# DataloggerE7.net
KiCad netlist of a schematic drawn in EAGLE
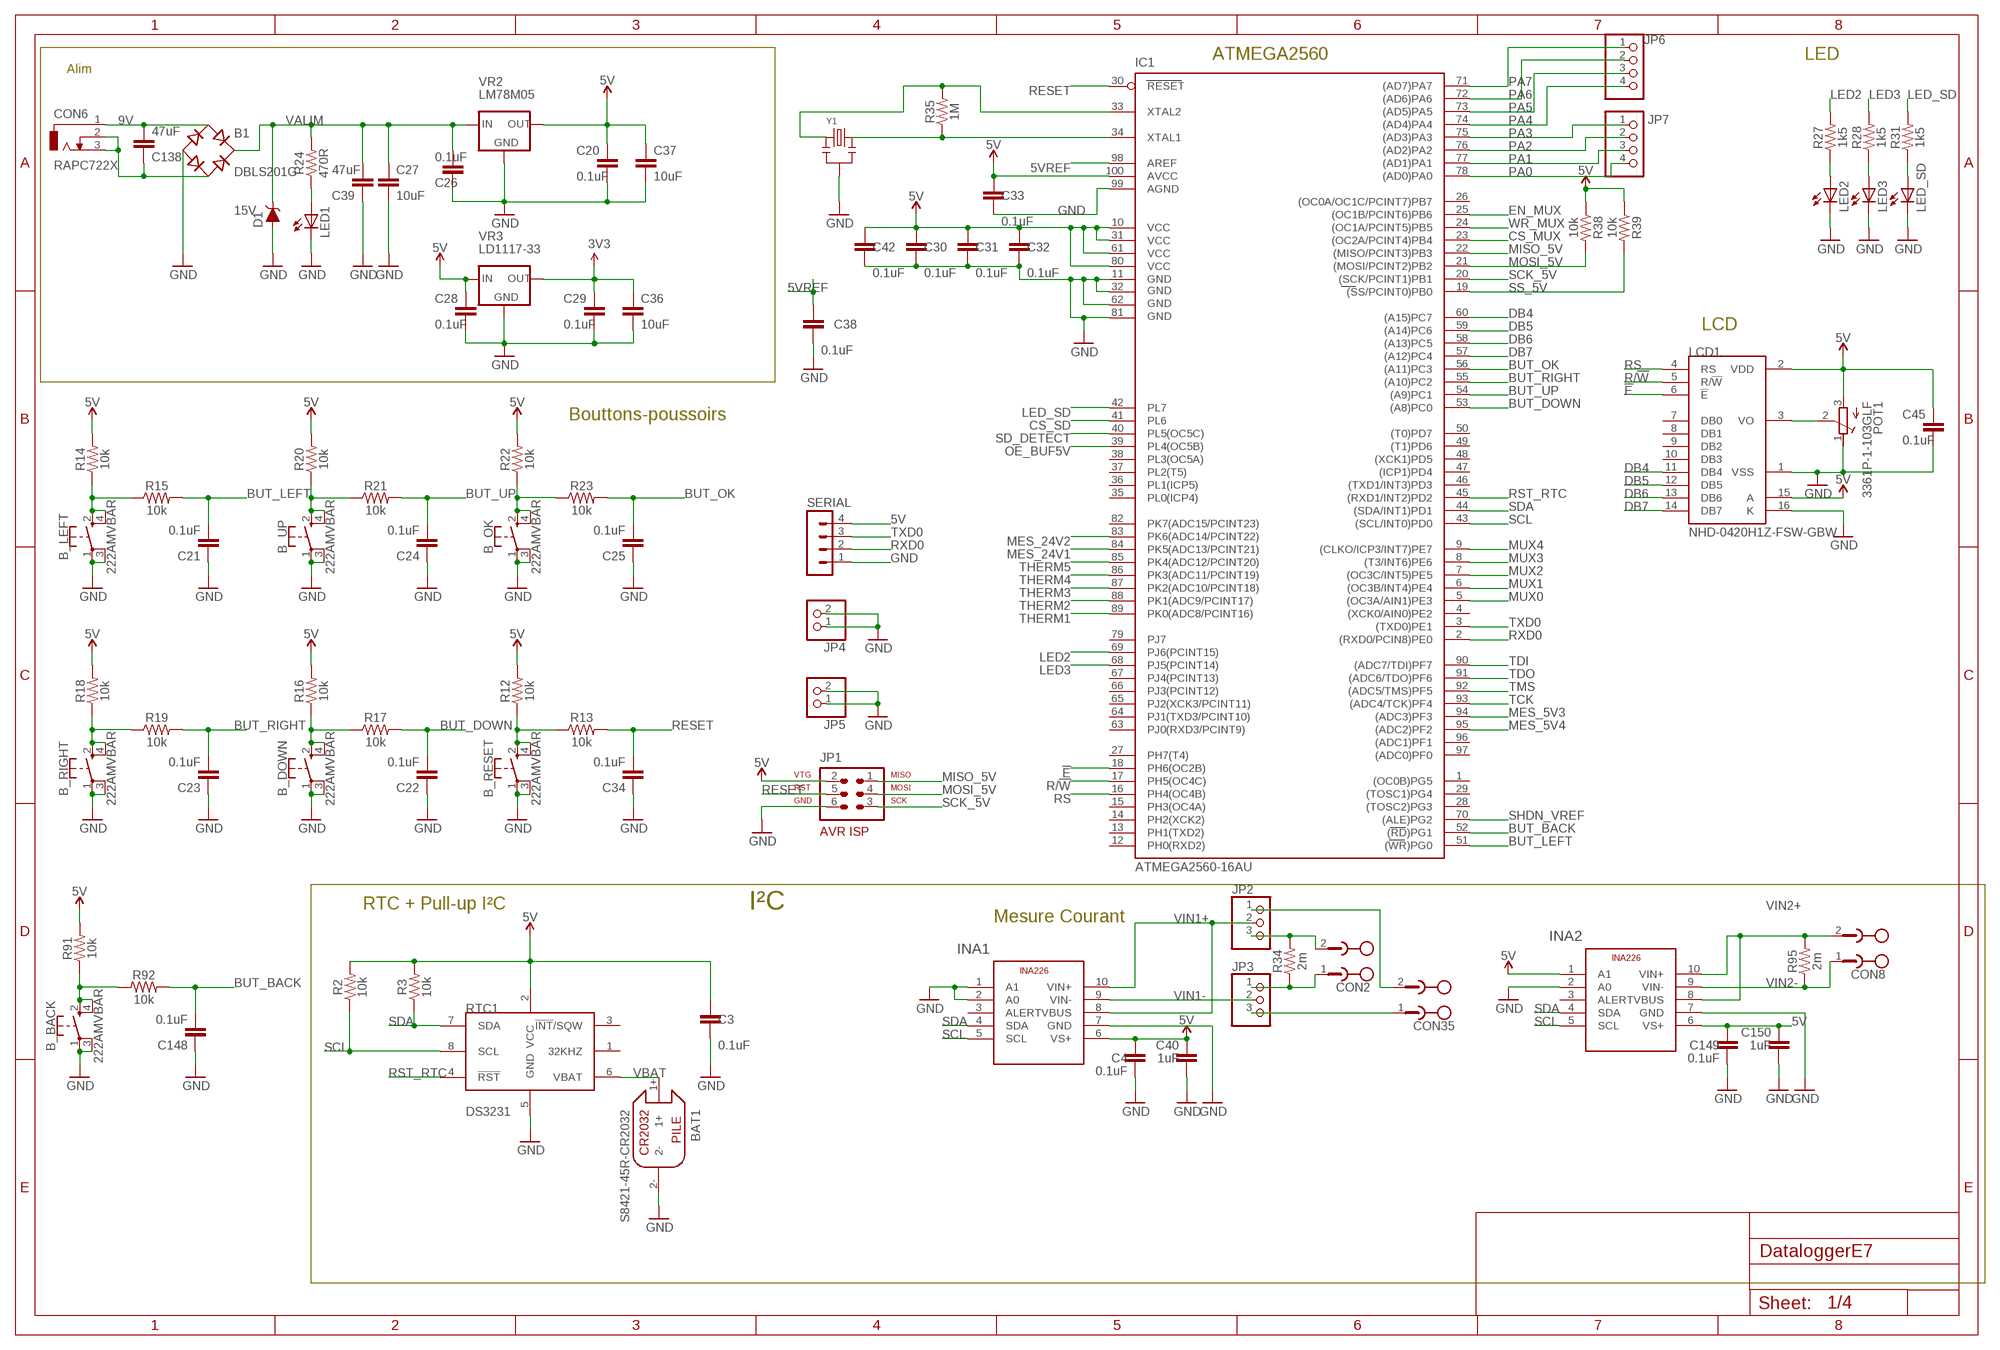
[diagram p0: schematic, sheet 1]
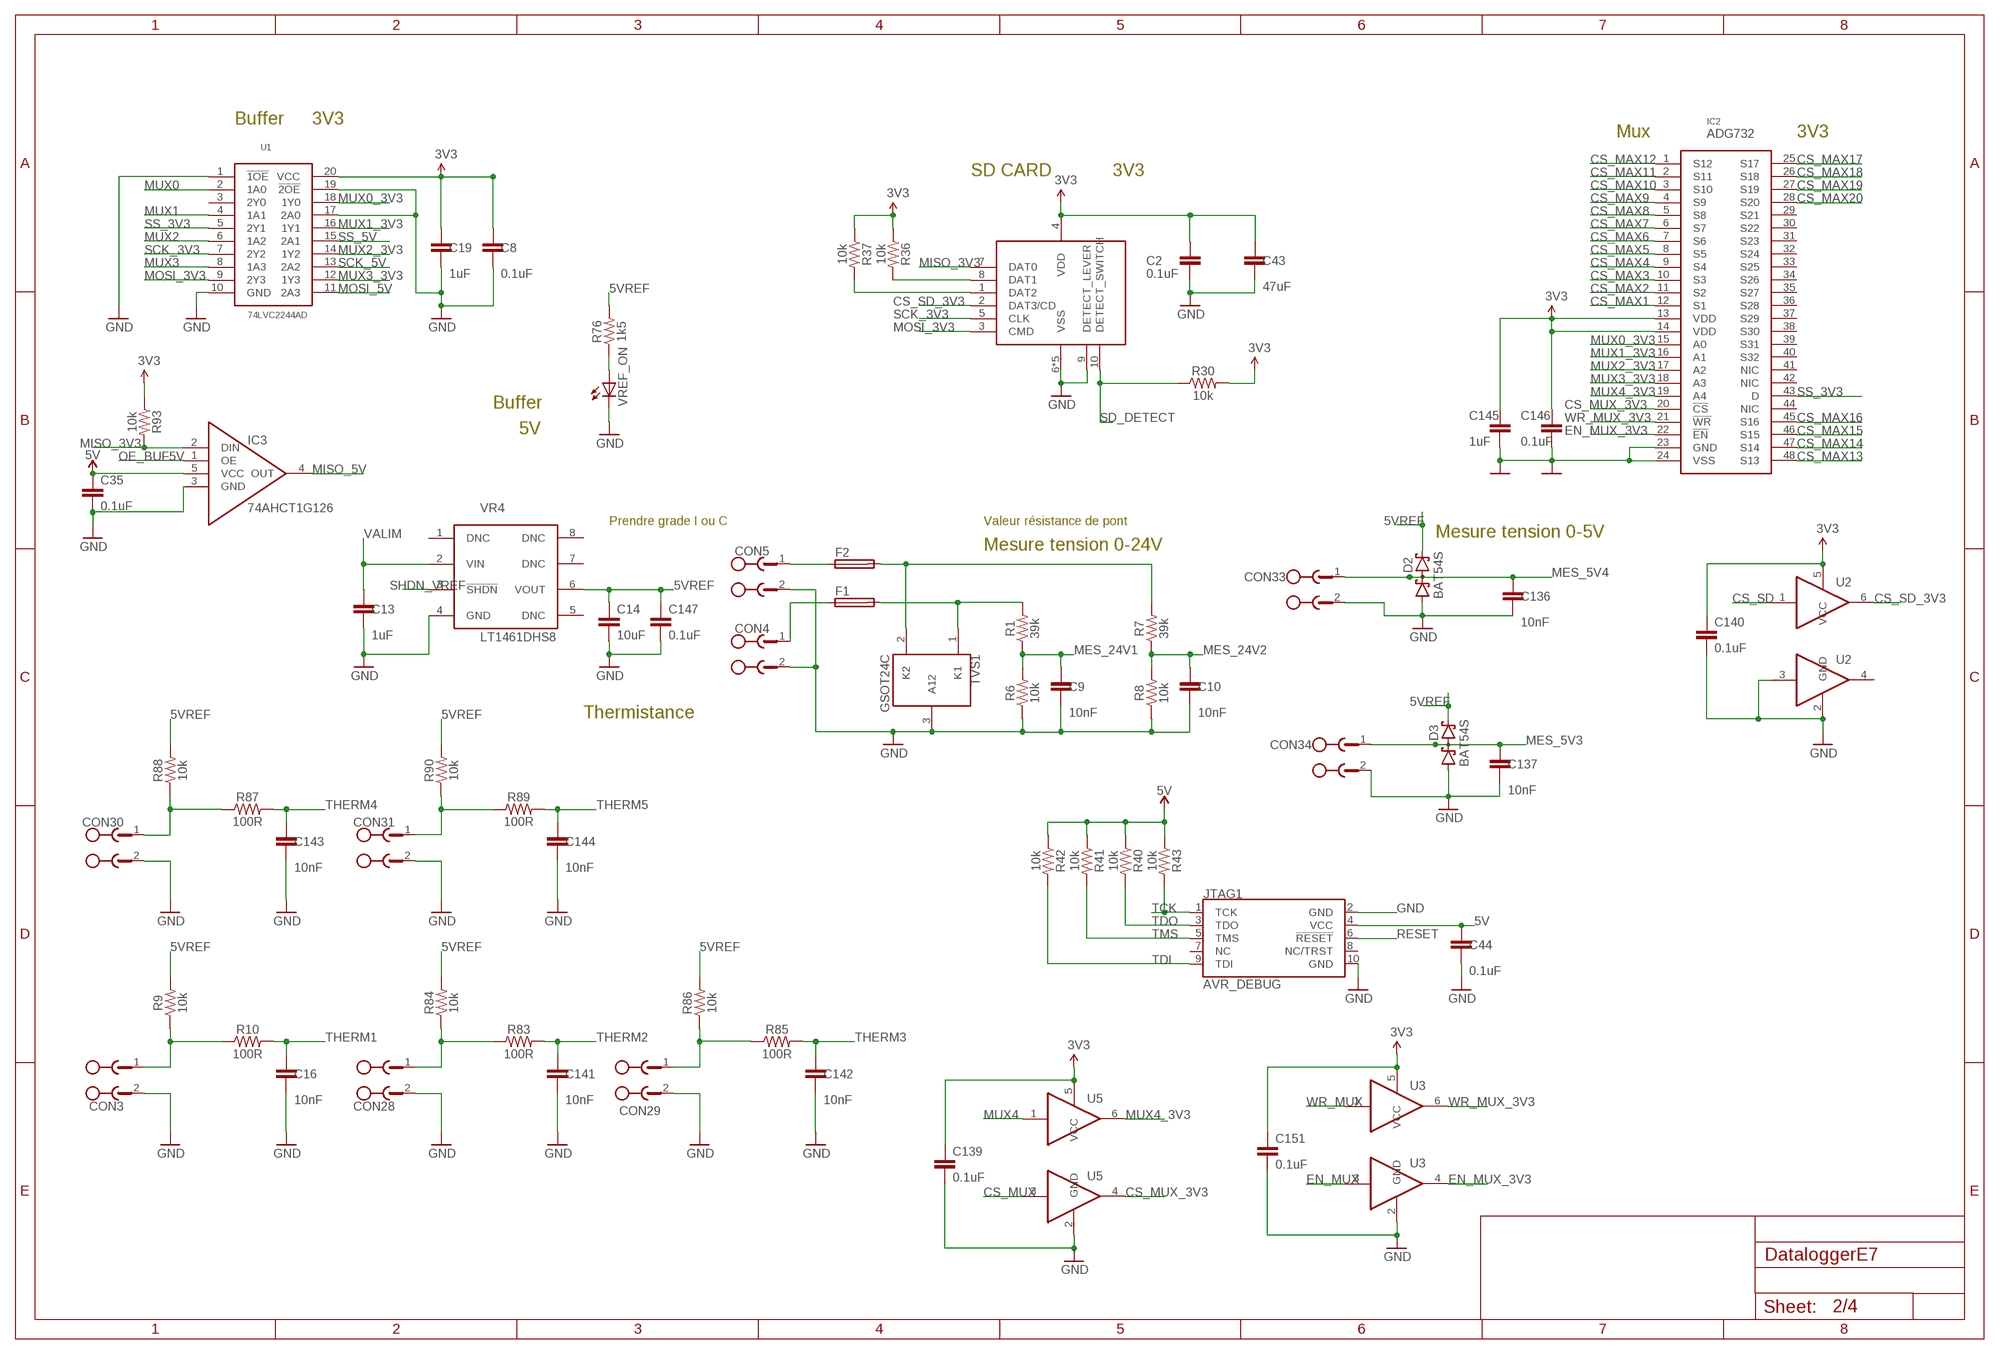
[diagram p1: schematic, sheet 2]
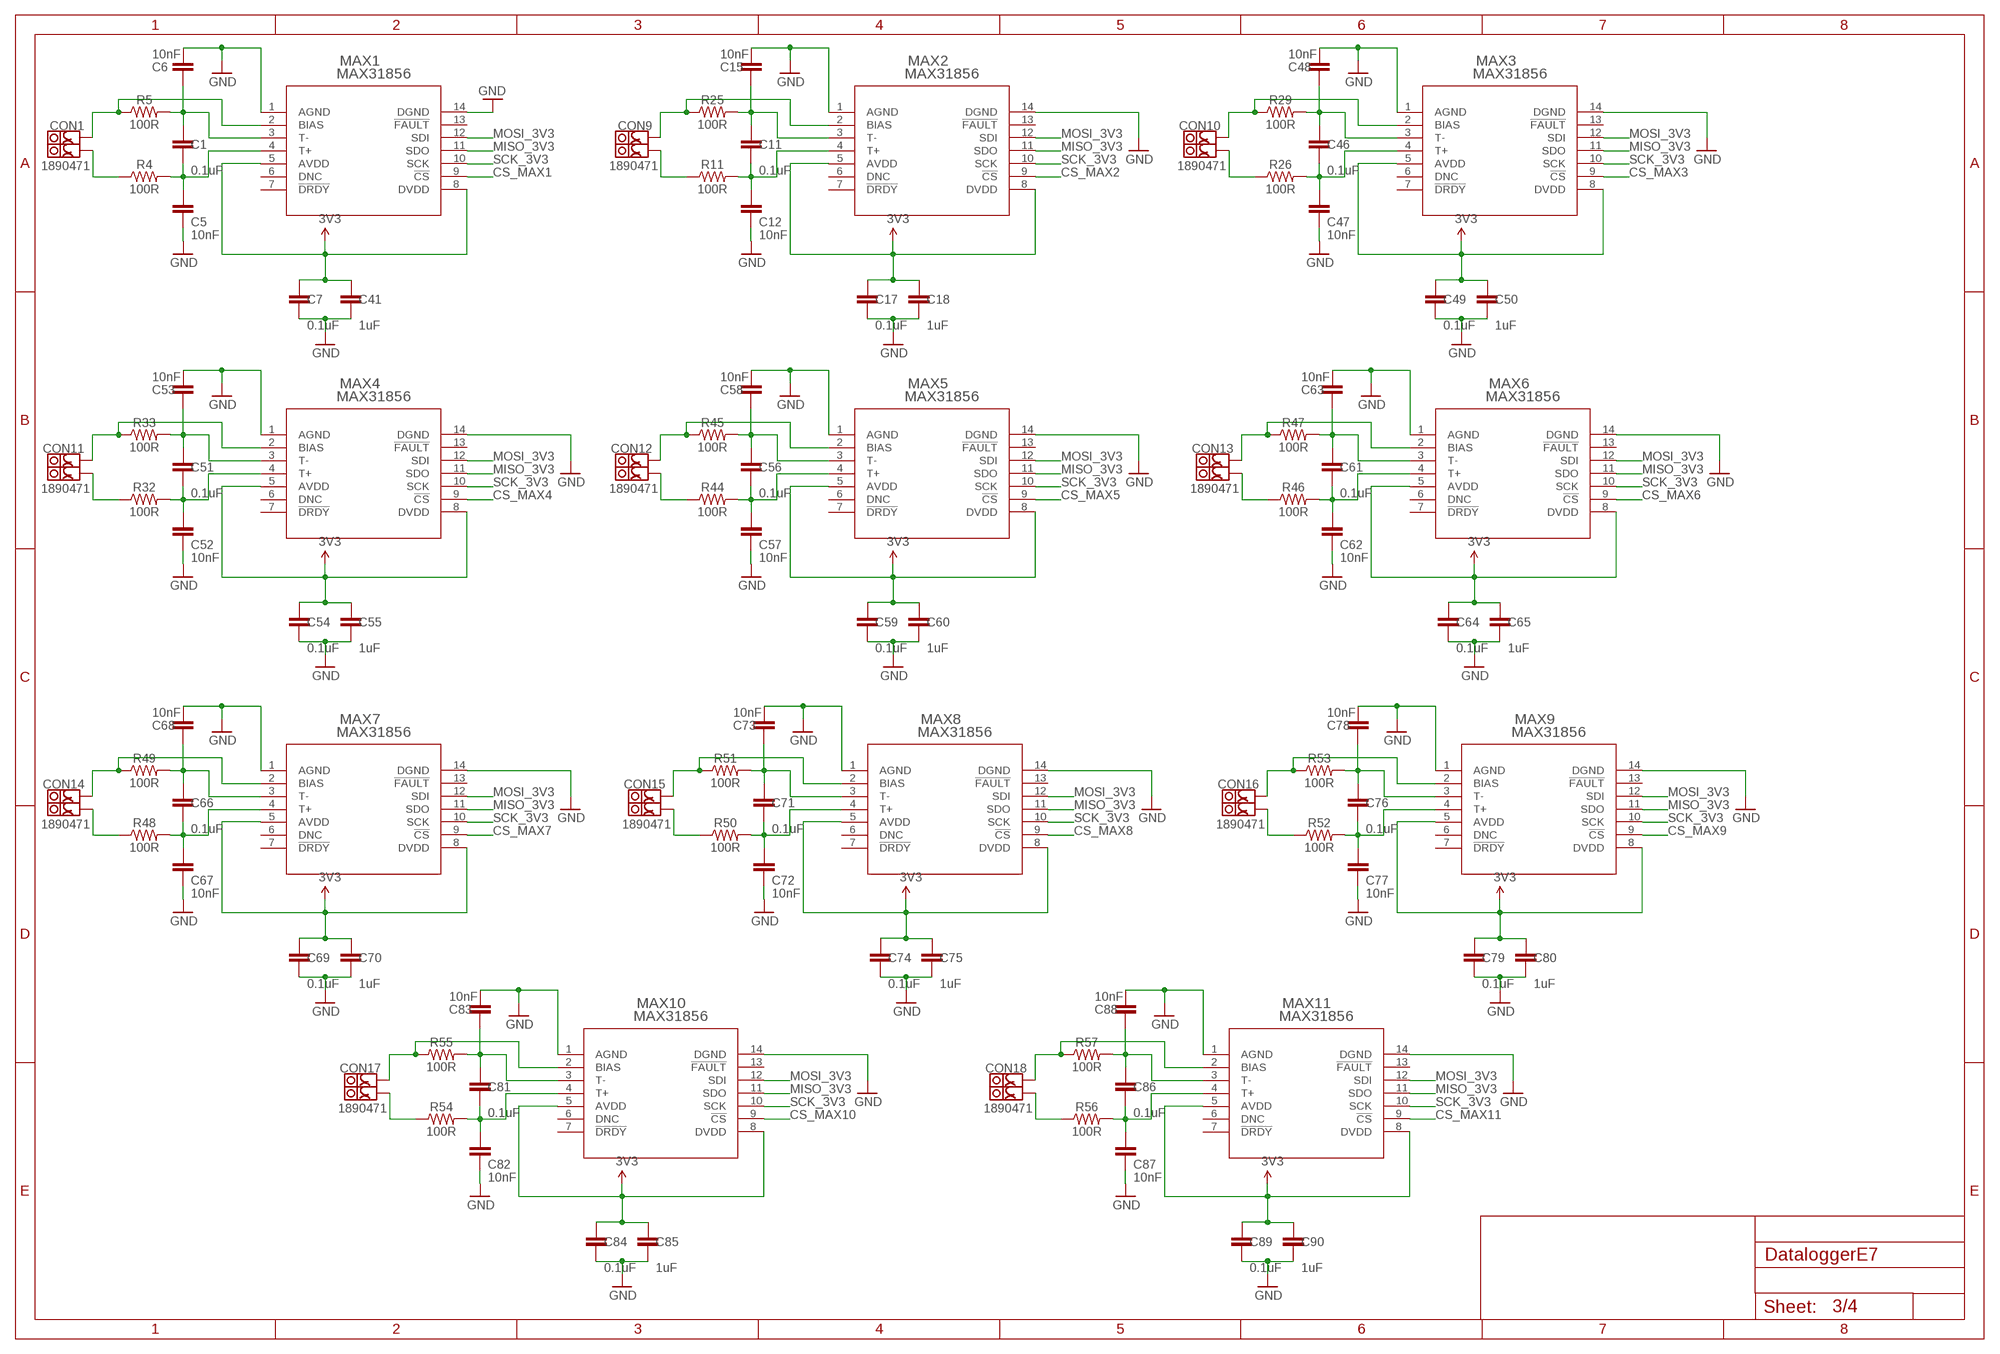
[diagram p2: schematic, sheet 3]
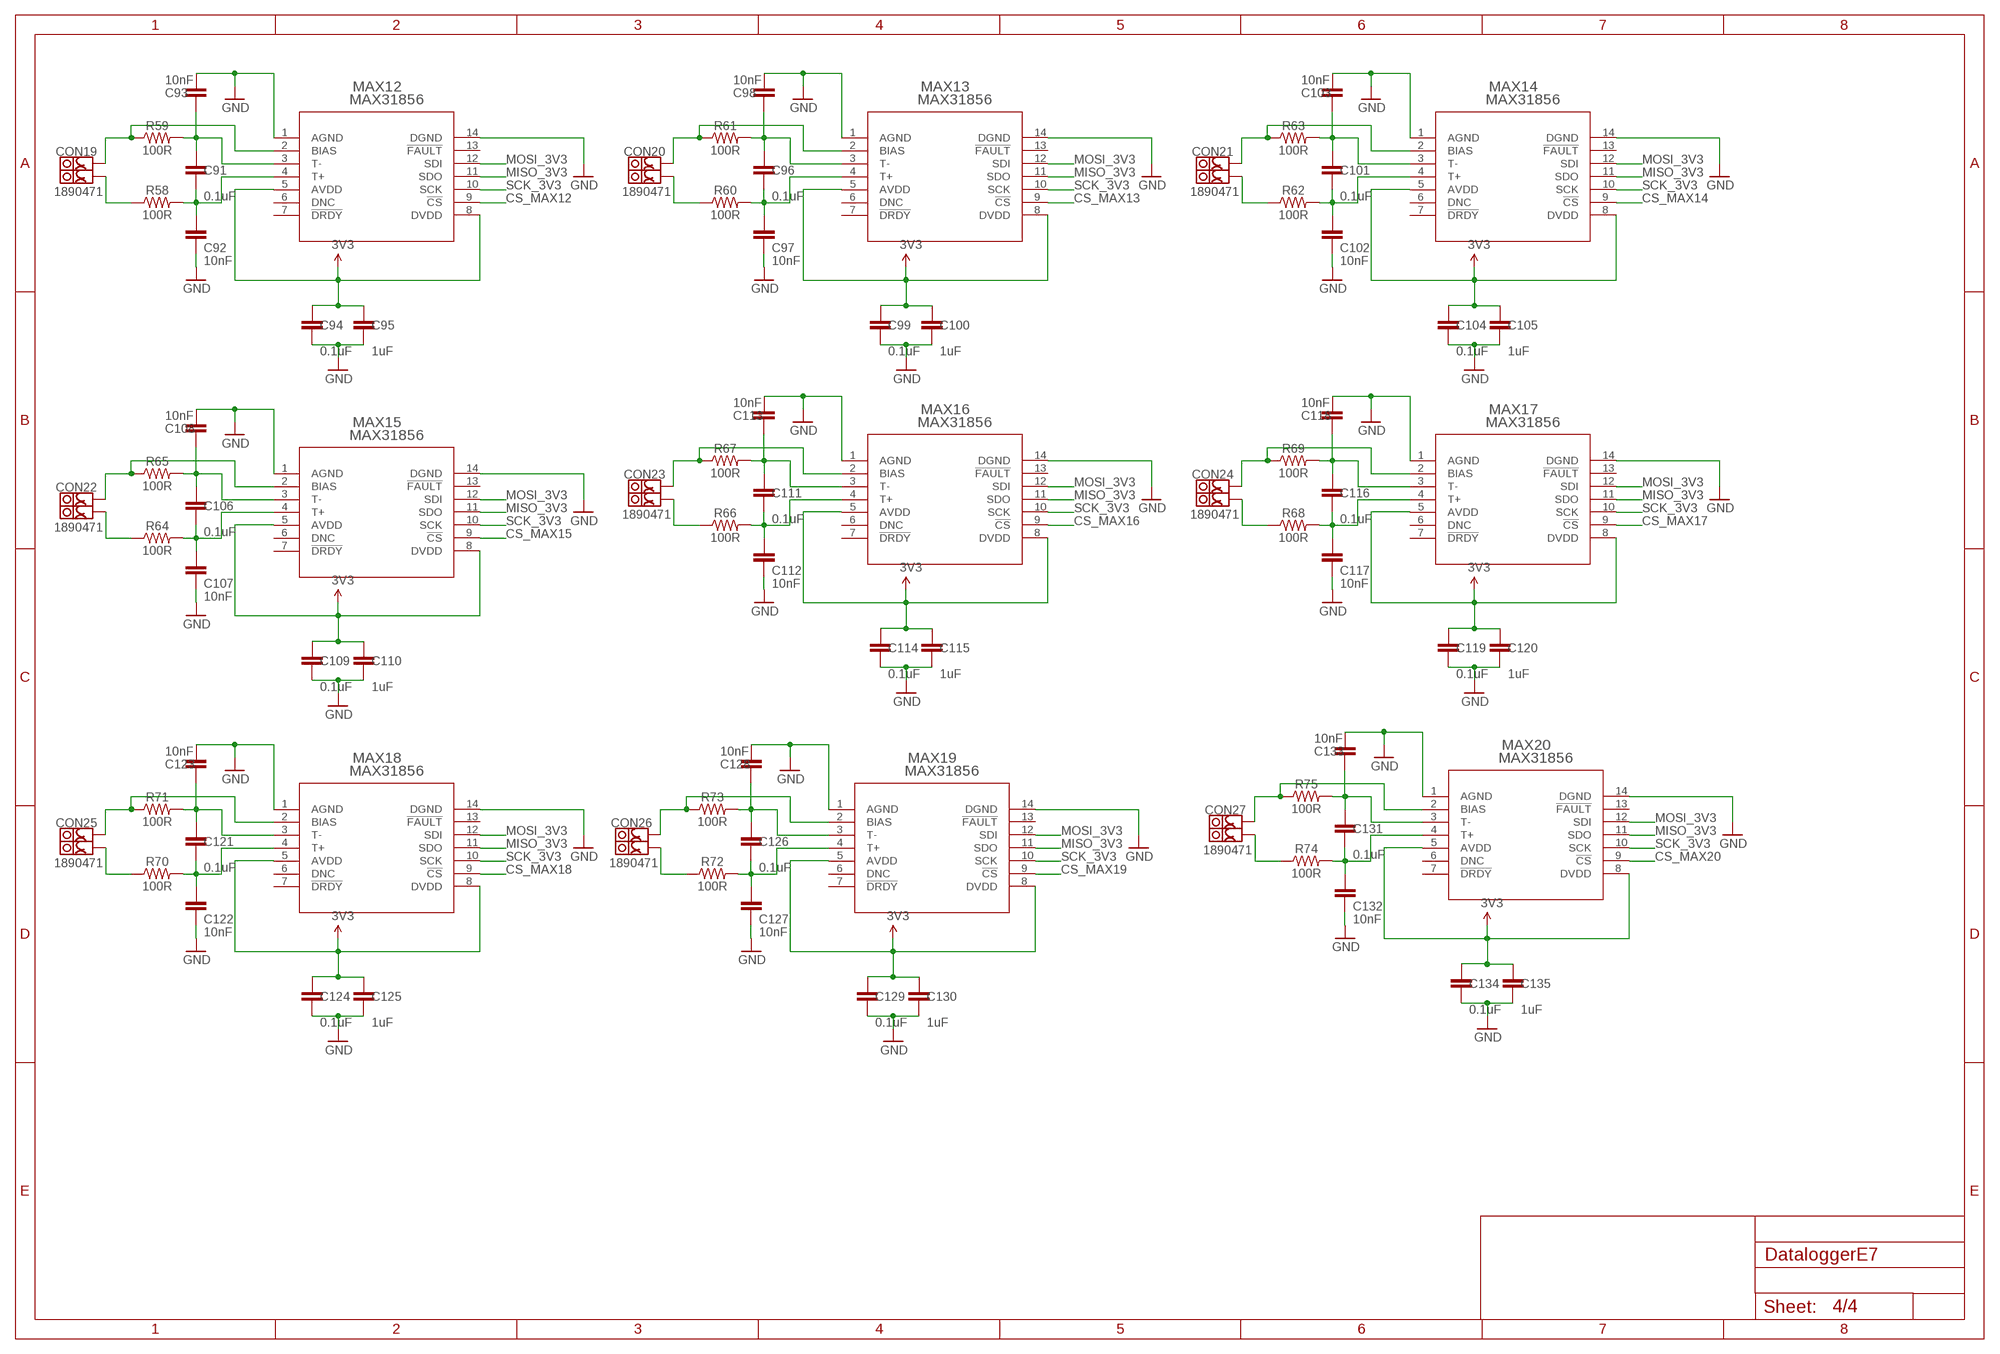
[diagram p3: schematic, sheet 4]

(export (version "E")
  (design (tool "Eeschema 10.0.6"))
  (components
    (comp (ref "C1")
      (value "0.1uF")
      (footprint "eagle-import:0603")
      (libsource (lib "eagle-import") (part "C0603_0.1UF"))
    )
    (comp (ref "C5")
      (value "10nF")
      (footprint "eagle-import:0603")
      (libsource (lib "eagle-import") (part "C0603_10NF"))
    )
    (comp (ref "C6")
      (value "10nF")
      (footprint "eagle-import:0603")
      (libsource (lib "eagle-import") (part "C0603_10NF"))
    )
    (comp (ref "C7")
      (value "0.1uF")
      (footprint "eagle-import:0603")
      (libsource (lib "eagle-import") (part "C0603_0.1UF"))
    )
    (comp (ref "C11")
      (value "0.1uF")
      (footprint "eagle-import:0603")
      (libsource (lib "eagle-import") (part "C0603_0.1UF"))
    )
    (comp (ref "C12")
      (value "10nF")
      (footprint "eagle-import:0603")
      (libsource (lib "eagle-import") (part "C0603_10NF"))
    )
    (comp (ref "C15")
      (value "10nF")
      (footprint "eagle-import:0603")
      (libsource (lib "eagle-import") (part "C0603_10NF"))
    )
    (comp (ref "C17")
      (value "0.1uF")
      (footprint "eagle-import:0603")
      (libsource (lib "eagle-import") (part "C0603_0.1UF"))
    )
    (comp (ref "C18")
      (value "1uF")
      (footprint "eagle-import:0603")
      (libsource (lib "eagle-import") (part "C0603_1UF"))
    )
    (comp (ref "C41")
      (value "1uF")
      (footprint "eagle-import:0603")
      (libsource (lib "eagle-import") (part "C0603_1UF"))
    )
    (comp (ref "C46")
      (value "0.1uF")
      (footprint "eagle-import:0603")
      (libsource (lib "eagle-import") (part "C0603_0.1UF"))
    )
    (comp (ref "C47")
      (value "10nF")
      (footprint "eagle-import:0603")
      (libsource (lib "eagle-import") (part "C0603_10NF"))
    )
    (comp (ref "C48")
      (value "10nF")
      (footprint "eagle-import:0603")
      (libsource (lib "eagle-import") (part "C0603_10NF"))
    )
    (comp (ref "C49")
      (value "0.1uF")
      (footprint "eagle-import:0603")
      (libsource (lib "eagle-import") (part "C0603_0.1UF"))
    )
    (comp (ref "C50")
      (value "1uF")
      (footprint "eagle-import:0603")
      (libsource (lib "eagle-import") (part "C0603_1UF"))
    )
    (comp (ref "C51")
      (value "0.1uF")
      (footprint "eagle-import:0603")
      (libsource (lib "eagle-import") (part "C0603_0.1UF"))
    )
    (comp (ref "C52")
      (value "10nF")
      (footprint "eagle-import:0603")
      (libsource (lib "eagle-import") (part "C0603_10NF"))
    )
    (comp (ref "C53")
      (value "10nF")
      (footprint "eagle-import:0603")
      (libsource (lib "eagle-import") (part "C0603_10NF"))
    )
    (comp (ref "C54")
      (value "0.1uF")
      (footprint "eagle-import:0603")
      (libsource (lib "eagle-import") (part "C0603_0.1UF"))
    )
    (comp (ref "C55")
      (value "1uF")
      (footprint "eagle-import:0603")
      (libsource (lib "eagle-import") (part "C0603_1UF"))
    )
    (comp (ref "C56")
      (value "0.1uF")
      (footprint "eagle-import:0603")
      (libsource (lib "eagle-import") (part "C0603_0.1UF"))
    )
    (comp (ref "C57")
      (value "10nF")
      (footprint "eagle-import:0603")
      (libsource (lib "eagle-import") (part "C0603_10NF"))
    )
    (comp (ref "C58")
      (value "10nF")
      (footprint "eagle-import:0603")
      (libsource (lib "eagle-import") (part "C0603_10NF"))
    )
    (comp (ref "C59")
      (value "0.1uF")
      (footprint "eagle-import:0603")
      (libsource (lib "eagle-import") (part "C0603_0.1UF"))
    )
    (comp (ref "C60")
      (value "1uF")
      (footprint "eagle-import:0603")
      (libsource (lib "eagle-import") (part "C0603_1UF"))
    )
    (comp (ref "C61")
      (value "0.1uF")
      (footprint "eagle-import:0603")
      (libsource (lib "eagle-import") (part "C0603_0.1UF"))
    )
    (comp (ref "C62")
      (value "10nF")
      (footprint "eagle-import:0603")
      (libsource (lib "eagle-import") (part "C0603_10NF"))
    )
    (comp (ref "C63")
      (value "10nF")
      (footprint "eagle-import:0603")
      (libsource (lib "eagle-import") (part "C0603_10NF"))
    )
    (comp (ref "C64")
      (value "0.1uF")
      (footprint "eagle-import:0603")
      (libsource (lib "eagle-import") (part "C0603_0.1UF"))
    )
    (comp (ref "C65")
      (value "1uF")
      (footprint "eagle-import:0603")
      (libsource (lib "eagle-import") (part "C0603_1UF"))
    )
    (comp (ref "C66")
      (value "0.1uF")
      (footprint "eagle-import:0603")
      (libsource (lib "eagle-import") (part "C0603_0.1UF"))
    )
    (comp (ref "C67")
      (value "10nF")
      (footprint "eagle-import:0603")
      (libsource (lib "eagle-import") (part "C0603_10NF"))
    )
    (comp (ref "C68")
      (value "10nF")
      (footprint "eagle-import:0603")
      (libsource (lib "eagle-import") (part "C0603_10NF"))
    )
    (comp (ref "C69")
      (value "0.1uF")
      (footprint "eagle-import:0603")
      (libsource (lib "eagle-import") (part "C0603_0.1UF"))
    )
    (comp (ref "C70")
      (value "1uF")
      (footprint "eagle-import:0603")
      (libsource (lib "eagle-import") (part "C0603_1UF"))
    )
    (comp (ref "C71")
      (value "0.1uF")
      (footprint "eagle-import:0603")
      (libsource (lib "eagle-import") (part "C0603_0.1UF"))
    )
    (comp (ref "C72")
      (value "10nF")
      (footprint "eagle-import:0603")
      (libsource (lib "eagle-import") (part "C0603_10NF"))
    )
    (comp (ref "C73")
      (value "10nF")
      (footprint "eagle-import:0603")
      (libsource (lib "eagle-import") (part "C0603_10NF"))
    )
    (comp (ref "C74")
      (value "0.1uF")
      (footprint "eagle-import:0603")
      (libsource (lib "eagle-import") (part "C0603_0.1UF"))
    )
    (comp (ref "C75")
      (value "1uF")
      (footprint "eagle-import:0603")
      (libsource (lib "eagle-import") (part "C0603_1UF"))
    )
    (comp (ref "C76")
      (value "0.1uF")
      (footprint "eagle-import:0603")
      (libsource (lib "eagle-import") (part "C0603_0.1UF"))
    )
    (comp (ref "C77")
      (value "10nF")
      (footprint "eagle-import:0603")
      (libsource (lib "eagle-import") (part "C0603_10NF"))
    )
    (comp (ref "C78")
      (value "10nF")
      (footprint "eagle-import:0603")
      (libsource (lib "eagle-import") (part "C0603_10NF"))
    )
    (comp (ref "C79")
      (value "0.1uF")
      (footprint "eagle-import:0603")
      (libsource (lib "eagle-import") (part "C0603_0.1UF"))
    )
    (comp (ref "C80")
      (value "1uF")
      (footprint "eagle-import:0603")
      (libsource (lib "eagle-import") (part "C0603_1UF"))
    )
    (comp (ref "C81")
      (value "0.1uF")
      (footprint "eagle-import:0603")
      (libsource (lib "eagle-import") (part "C0603_0.1UF"))
    )
    (comp (ref "C82")
      (value "10nF")
      (footprint "eagle-import:0603")
      (libsource (lib "eagle-import") (part "C0603_10NF"))
    )
    (comp (ref "C83")
      (value "10nF")
      (footprint "eagle-import:0603")
      (libsource (lib "eagle-import") (part "C0603_10NF"))
    )
    (comp (ref "C84")
      (value "0.1uF")
      (footprint "eagle-import:0603")
      (libsource (lib "eagle-import") (part "C0603_0.1UF"))
    )
    (comp (ref "C85")
      (value "1uF")
      (footprint "eagle-import:0603")
      (libsource (lib "eagle-import") (part "C0603_1UF"))
    )
    (comp (ref "C86")
      (value "0.1uF")
      (footprint "eagle-import:0603")
      (libsource (lib "eagle-import") (part "C0603_0.1UF"))
    )
    (comp (ref "C87")
      (value "10nF")
      (footprint "eagle-import:0603")
      (libsource (lib "eagle-import") (part "C0603_10NF"))
    )
    (comp (ref "C88")
      (value "10nF")
      (footprint "eagle-import:0603")
      (libsource (lib "eagle-import") (part "C0603_10NF"))
    )
    (comp (ref "C89")
      (value "0.1uF")
      (footprint "eagle-import:0603")
      (libsource (lib "eagle-import") (part "C0603_0.1UF"))
    )
    (comp (ref "C90")
      (value "1uF")
      (footprint "eagle-import:0603")
      (libsource (lib "eagle-import") (part "C0603_1UF"))
    )
    (comp (ref "CON1")
      (value "1890471")
      (footprint "eagle-import:1890471")
      (libsource (lib "eagle-import") (part "1890471"))
    )
    (comp (ref "CON9")
      (value "1890471")
      (footprint "eagle-import:1890471")
      (libsource (lib "eagle-import") (part "1890471"))
    )
    (comp (ref "CON10")
      (value "1890471")
      (footprint "eagle-import:1890471")
      (libsource (lib "eagle-import") (part "1890471"))
    )
    (comp (ref "CON11")
      (value "1890471")
      (footprint "eagle-import:1890471")
      (libsource (lib "eagle-import") (part "1890471"))
    )
    (comp (ref "CON12")
      (value "1890471")
      (footprint "eagle-import:1890471")
      (libsource (lib "eagle-import") (part "1890471"))
    )
    (comp (ref "CON13")
      (value "1890471")
      (footprint "eagle-import:1890471")
      (libsource (lib "eagle-import") (part "1890471"))
    )
    (comp (ref "CON14")
      (value "1890471")
      (footprint "eagle-import:1890471")
      (libsource (lib "eagle-import") (part "1890471"))
    )
    (comp (ref "CON15")
      (value "1890471")
      (footprint "eagle-import:1890471")
      (libsource (lib "eagle-import") (part "1890471"))
    )
    (comp (ref "CON16")
      (value "1890471")
      (footprint "eagle-import:1890471")
      (libsource (lib "eagle-import") (part "1890471"))
    )
    (comp (ref "CON17")
      (value "1890471")
      (footprint "eagle-import:1890471")
      (libsource (lib "eagle-import") (part "1890471"))
    )
    (comp (ref "CON18")
      (value "1890471")
      (footprint "eagle-import:1890471")
      (libsource (lib "eagle-import") (part "1890471"))
    )
    (comp (ref "MAX1")
      (value "MAX31856")
      (footprint "eagle-import:21-066J-14-M")
      (fields (field (name "MPN") "MAX31856MUD+ "))
      (libsource (lib "eagle-import") (part "MAX31856"))
    )
    (comp (ref "MAX2")
      (value "MAX31856")
      (footprint "eagle-import:21-066J-14-M")
      (fields (field (name "MPN") "MAX31856MUD+ "))
      (libsource (lib "eagle-import") (part "MAX31856"))
    )
    (comp (ref "MAX3")
      (value "MAX31856")
      (footprint "eagle-import:21-066J-14-M")
      (fields (field (name "MPN") "MAX31856MUD+ "))
      (libsource (lib "eagle-import") (part "MAX31856"))
    )
    (comp (ref "MAX4")
      (value "MAX31856")
      (footprint "eagle-import:21-066J-14-M")
      (fields (field (name "MPN") "MAX31856MUD+ "))
      (libsource (lib "eagle-import") (part "MAX31856"))
    )
    (comp (ref "MAX5")
      (value "MAX31856")
      (footprint "eagle-import:21-066J-14-M")
      (fields (field (name "MPN") "MAX31856MUD+ "))
      (libsource (lib "eagle-import") (part "MAX31856"))
    )
    (comp (ref "MAX6")
      (value "MAX31856")
      (footprint "eagle-import:21-066J-14-M")
      (fields (field (name "MPN") "MAX31856MUD+ "))
      (libsource (lib "eagle-import") (part "MAX31856"))
    )
    (comp (ref "MAX7")
      (value "MAX31856")
      (footprint "eagle-import:21-066J-14-M")
      (fields (field (name "MPN") "MAX31856MUD+ "))
      (libsource (lib "eagle-import") (part "MAX31856"))
    )
    (comp (ref "MAX8")
      (value "MAX31856")
      (footprint "eagle-import:21-066J-14-M")
      (fields (field (name "MPN") "MAX31856MUD+ "))
      (libsource (lib "eagle-import") (part "MAX31856"))
    )
    (comp (ref "MAX9")
      (value "MAX31856")
      (footprint "eagle-import:21-066J-14-M")
      (fields (field (name "MPN") "MAX31856MUD+ "))
      (libsource (lib "eagle-import") (part "MAX31856"))
    )
    (comp (ref "MAX10")
      (value "MAX31856")
      (footprint "eagle-import:21-066J-14-M")
      (fields (field (name "MPN") "MAX31856MUD+ "))
      (libsource (lib "eagle-import") (part "MAX31856"))
    )
    (comp (ref "MAX11")
      (value "MAX31856")
      (footprint "eagle-import:21-066J-14-M")
      (fields (field (name "MPN") "MAX31856MUD+ "))
      (libsource (lib "eagle-import") (part "MAX31856"))
    )
    (comp (ref "R4")
      (value "100R")
      (footprint "eagle-import:0603")
      (libsource (lib "eagle-import") (part "R0603_100R"))
    )
    (comp (ref "R5")
      (value "100R")
      (footprint "eagle-import:0603")
      (libsource (lib "eagle-import") (part "R0603_100R"))
    )
    (comp (ref "R11")
      (value "100R")
      (footprint "eagle-import:0603")
      (libsource (lib "eagle-import") (part "R0603_100R"))
    )
    (comp (ref "R25")
      (value "100R")
      (footprint "eagle-import:0603")
      (libsource (lib "eagle-import") (part "R0603_100R"))
    )
    (comp (ref "R26")
      (value "100R")
      (footprint "eagle-import:0603")
      (libsource (lib "eagle-import") (part "R0603_100R"))
    )
    (comp (ref "R29")
      (value "100R")
      (footprint "eagle-import:0603")
      (libsource (lib "eagle-import") (part "R0603_100R"))
    )
    (comp (ref "R32")
      (value "100R")
      (footprint "eagle-import:0603")
      (libsource (lib "eagle-import") (part "R0603_100R"))
    )
    (comp (ref "R33")
      (value "100R")
      (footprint "eagle-import:0603")
      (libsource (lib "eagle-import") (part "R0603_100R"))
    )
    (comp (ref "R44")
      (value "100R")
      (footprint "eagle-import:0603")
      (libsource (lib "eagle-import") (part "R0603_100R"))
    )
    (comp (ref "R45")
      (value "100R")
      (footprint "eagle-import:0603")
      (libsource (lib "eagle-import") (part "R0603_100R"))
    )
    (comp (ref "R46")
      (value "100R")
      (footprint "eagle-import:0603")
      (libsource (lib "eagle-import") (part "R0603_100R"))
    )
    (comp (ref "R47")
      (value "100R")
      (footprint "eagle-import:0603")
      (libsource (lib "eagle-import") (part "R0603_100R"))
    )
    (comp (ref "R48")
      (value "100R")
      (footprint "eagle-import:0603")
      (libsource (lib "eagle-import") (part "R0603_100R"))
    )
    (comp (ref "R49")
      (value "100R")
      (footprint "eagle-import:0603")
      (libsource (lib "eagle-import") (part "R0603_100R"))
    )
    (comp (ref "R50")
      (value "100R")
      (footprint "eagle-import:0603")
      (libsource (lib "eagle-import") (part "R0603_100R"))
    )
    (comp (ref "R51")
      (value "100R")
      (footprint "eagle-import:0603")
      (libsource (lib "eagle-import") (part "R0603_100R"))
    )
    (comp (ref "R52")
      (value "100R")
      (footprint "eagle-import:0603")
      (libsource (lib "eagle-import") (part "R0603_100R"))
    )
    (comp (ref "R53")
      (value "100R")
      (footprint "eagle-import:0603")
      (libsource (lib "eagle-import") (part "R0603_100R"))
    )
    (comp (ref "R54")
      (value "100R")
      (footprint "eagle-import:0603")
      (libsource (lib "eagle-import") (part "R0603_100R"))
    )
    (comp (ref "R55")
      (value "100R")
      (footprint "eagle-import:0603")
      (libsource (lib "eagle-import") (part "R0603_100R"))
    )
    (comp (ref "R56")
      (value "100R")
      (footprint "eagle-import:0603")
      (libsource (lib "eagle-import") (part "R0603_100R"))
    )
    (comp (ref "R57")
      (value "100R")
      (footprint "eagle-import:0603")
      (libsource (lib "eagle-import") (part "R0603_100R"))
    )
    (comp (ref "C91")
      (value "0.1uF")
      (footprint "eagle-import:0603")
      (libsource (lib "eagle-import") (part "C0603_0.1UF"))
    )
    (comp (ref "C92")
      (value "10nF")
      (footprint "eagle-import:0603")
      (libsource (lib "eagle-import") (part "C0603_10NF"))
    )
    (comp (ref "C93")
      (value "10nF")
      (footprint "eagle-import:0603")
      (libsource (lib "eagle-import") (part "C0603_10NF"))
    )
    (comp (ref "C94")
      (value "0.1uF")
      (footprint "eagle-import:0603")
      (libsource (lib "eagle-import") (part "C0603_0.1UF"))
    )
    (comp (ref "C95")
      (value "1uF")
      (footprint "eagle-import:0603")
      (libsource (lib "eagle-import") (part "C0603_1UF"))
    )
    (comp (ref "C96")
      (value "0.1uF")
      (footprint "eagle-import:0603")
      (libsource (lib "eagle-import") (part "C0603_0.1UF"))
    )
    (comp (ref "C97")
      (value "10nF")
      (footprint "eagle-import:0603")
      (libsource (lib "eagle-import") (part "C0603_10NF"))
    )
    (comp (ref "C98")
      (value "10nF")
      (footprint "eagle-import:0603")
      (libsource (lib "eagle-import") (part "C0603_10NF"))
    )
    (comp (ref "C99")
      (value "0.1uF")
      (footprint "eagle-import:0603")
      (libsource (lib "eagle-import") (part "C0603_0.1UF"))
    )
    (comp (ref "C100")
      (value "1uF")
      (footprint "eagle-import:0603")
      (libsource (lib "eagle-import") (part "C0603_1UF"))
    )
    (comp (ref "C101")
      (value "0.1uF")
      (footprint "eagle-import:0603")
      (libsource (lib "eagle-import") (part "C0603_0.1UF"))
    )
    (comp (ref "C102")
      (value "10nF")
      (footprint "eagle-import:0603")
      (libsource (lib "eagle-import") (part "C0603_10NF"))
    )
    (comp (ref "C103")
      (value "10nF")
      (footprint "eagle-import:0603")
      (libsource (lib "eagle-import") (part "C0603_10NF"))
    )
    (comp (ref "C104")
      (value "0.1uF")
      (footprint "eagle-import:0603")
      (libsource (lib "eagle-import") (part "C0603_0.1UF"))
    )
    (comp (ref "C105")
      (value "1uF")
      (footprint "eagle-import:0603")
      (libsource (lib "eagle-import") (part "C0603_1UF"))
    )
    (comp (ref "C106")
      (value "0.1uF")
      (footprint "eagle-import:0603")
      (libsource (lib "eagle-import") (part "C0603_0.1UF"))
    )
    (comp (ref "C107")
      (value "10nF")
      (footprint "eagle-import:0603")
      (libsource (lib "eagle-import") (part "C0603_10NF"))
    )
    (comp (ref "C108")
      (value "10nF")
      (footprint "eagle-import:0603")
      (libsource (lib "eagle-import") (part "C0603_10NF"))
    )
    (comp (ref "C109")
      (value "0.1uF")
      (footprint "eagle-import:0603")
      (libsource (lib "eagle-import") (part "C0603_0.1UF"))
    )
    (comp (ref "C110")
      (value "1uF")
      (footprint "eagle-import:0603")
      (libsource (lib "eagle-import") (part "C0603_1UF"))
    )
    (comp (ref "C111")
      (value "0.1uF")
      (footprint "eagle-import:0603")
      (libsource (lib "eagle-import") (part "C0603_0.1UF"))
    )
    (comp (ref "C112")
      (value "10nF")
      (footprint "eagle-import:0603")
      (libsource (lib "eagle-import") (part "C0603_10NF"))
    )
    (comp (ref "C113")
      (value "10nF")
      (footprint "eagle-import:0603")
      (libsource (lib "eagle-import") (part "C0603_10NF"))
    )
    (comp (ref "C114")
      (value "0.1uF")
      (footprint "eagle-import:0603")
      (libsource (lib "eagle-import") (part "C0603_0.1UF"))
    )
    (comp (ref "C115")
      (value "1uF")
      (footprint "eagle-import:0603")
      (libsource (lib "eagle-import") (part "C0603_1UF"))
    )
    (comp (ref "C116")
      (value "0.1uF")
      (footprint "eagle-import:0603")
      (libsource (lib "eagle-import") (part "C0603_0.1UF"))
    )
    (comp (ref "C117")
      (value "10nF")
      (footprint "eagle-import:0603")
      (libsource (lib "eagle-import") (part "C0603_10NF"))
    )
    (comp (ref "C118")
      (value "10nF")
      (footprint "eagle-import:0603")
      (libsource (lib "eagle-import") (part "C0603_10NF"))
    )
    (comp (ref "C119")
      (value "0.1uF")
      (footprint "eagle-import:0603")
      (libsource (lib "eagle-import") (part "C0603_0.1UF"))
    )
    (comp (ref "C120")
      (value "1uF")
      (footprint "eagle-import:0603")
      (libsource (lib "eagle-import") (part "C0603_1UF"))
    )
    (comp (ref "C121")
      (value "0.1uF")
      (footprint "eagle-import:0603")
      (libsource (lib "eagle-import") (part "C0603_0.1UF"))
    )
    (comp (ref "C122")
      (value "10nF")
      (footprint "eagle-import:0603")
      (libsource (lib "eagle-import") (part "C0603_10NF"))
    )
    (comp (ref "C123")
      (value "10nF")
      (footprint "eagle-import:0603")
      (libsource (lib "eagle-import") (part "C0603_10NF"))
    )
    (comp (ref "C124")
      (value "0.1uF")
      (footprint "eagle-import:0603")
      (libsource (lib "eagle-import") (part "C0603_0.1UF"))
    )
    (comp (ref "C125")
      (value "1uF")
      (footprint "eagle-import:0603")
      (libsource (lib "eagle-import") (part "C0603_1UF"))
    )
    (comp (ref "C126")
      (value "0.1uF")
      (footprint "eagle-import:0603")
      (libsource (lib "eagle-import") (part "C0603_0.1UF"))
    )
    (comp (ref "C127")
      (value "10nF")
      (footprint "eagle-import:0603")
      (libsource (lib "eagle-import") (part "C0603_10NF"))
    )
    (comp (ref "C128")
      (value "10nF")
      (footprint "eagle-import:0603")
      (libsource (lib "eagle-import") (part "C0603_10NF"))
    )
    (comp (ref "C129")
      (value "0.1uF")
      (footprint "eagle-import:0603")
      (libsource (lib "eagle-import") (part "C0603_0.1UF"))
    )
    (comp (ref "C130")
      (value "1uF")
      (footprint "eagle-import:0603")
      (libsource (lib "eagle-import") (part "C0603_1UF"))
    )
    (comp (ref "C131")
      (value "0.1uF")
      (footprint "eagle-import:0603")
      (libsource (lib "eagle-import") (part "C0603_0.1UF"))
    )
    (comp (ref "C132")
      (value "10nF")
      (footprint "eagle-import:0603")
      (libsource (lib "eagle-import") (part "C0603_10NF"))
    )
    (comp (ref "C133")
      (value "10nF")
      (footprint "eagle-import:0603")
      (libsource (lib "eagle-import") (part "C0603_10NF"))
    )
    (comp (ref "C134")
      (value "0.1uF")
      (footprint "eagle-import:0603")
      (libsource (lib "eagle-import") (part "C0603_0.1UF"))
    )
    (comp (ref "C135")
      (value "1uF")
      (footprint "eagle-import:0603")
      (libsource (lib "eagle-import") (part "C0603_1UF"))
    )
    (comp (ref "CON19")
      (value "1890471")
      (footprint "eagle-import:1890471")
      (libsource (lib "eagle-import") (part "1890471"))
    )
    (comp (ref "CON20")
      (value "1890471")
      (footprint "eagle-import:1890471")
      (libsource (lib "eagle-import") (part "1890471"))
    )
    (comp (ref "CON21")
      (value "1890471")
      (footprint "eagle-import:1890471")
      (libsource (lib "eagle-import") (part "1890471"))
    )
    (comp (ref "CON22")
      (value "1890471")
      (footprint "eagle-import:1890471")
      (libsource (lib "eagle-import") (part "1890471"))
    )
    (comp (ref "CON23")
      (value "1890471")
      (footprint "eagle-import:1890471")
      (libsource (lib "eagle-import") (part "1890471"))
    )
    (comp (ref "CON24")
      (value "1890471")
      (footprint "eagle-import:1890471")
      (libsource (lib "eagle-import") (part "1890471"))
    )
    (comp (ref "CON25")
      (value "1890471")
      (footprint "eagle-import:1890471")
      (libsource (lib "eagle-import") (part "1890471"))
    )
    (comp (ref "CON26")
      (value "1890471")
      (footprint "eagle-import:1890471")
      (libsource (lib "eagle-import") (part "1890471"))
    )
    (comp (ref "CON27")
      (value "1890471")
      (footprint "eagle-import:1890471")
      (libsource (lib "eagle-import") (part "1890471"))
    )
    (comp (ref "MAX12")
      (value "MAX31856")
      (footprint "eagle-import:21-066J-14-M")
      (fields (field (name "MPN") "MAX31856MUD+ "))
      (libsource (lib "eagle-import") (part "MAX31856"))
    )
    (comp (ref "MAX13")
      (value "MAX31856")
      (footprint "eagle-import:21-066J-14-M")
      (fields (field (name "MPN") "MAX31856MUD+ "))
      (libsource (lib "eagle-import") (part "MAX31856"))
    )
    (comp (ref "MAX14")
      (value "MAX31856")
      (footprint "eagle-import:21-066J-14-M")
      (fields (field (name "MPN") "MAX31856MUD+ "))
      (libsource (lib "eagle-import") (part "MAX31856"))
    )
    (comp (ref "MAX15")
      (value "MAX31856")
      (footprint "eagle-import:21-066J-14-M")
      (fields (field (name "MPN") "MAX31856MUD+ "))
      (libsource (lib "eagle-import") (part "MAX31856"))
    )
    (comp (ref "MAX16")
      (value "MAX31856")
      (footprint "eagle-import:21-066J-14-M")
      (fields (field (name "MPN") "MAX31856MUD+ "))
      (libsource (lib "eagle-import") (part "MAX31856"))
    )
    (comp (ref "MAX17")
      (value "MAX31856")
      (footprint "eagle-import:21-066J-14-M")
      (fields (field (name "MPN") "MAX31856MUD+ "))
      (libsource (lib "eagle-import") (part "MAX31856"))
    )
    (comp (ref "MAX18")
      (value "MAX31856")
      (footprint "eagle-import:21-066J-14-M")
      (fields (field (name "MPN") "MAX31856MUD+ "))
      (libsource (lib "eagle-import") (part "MAX31856"))
    )
    (comp (ref "MAX19")
      (value "MAX31856")
      (footprint "eagle-import:21-066J-14-M")
      (fields (field (name "MPN") "MAX31856MUD+ "))
      (libsource (lib "eagle-import") (part "MAX31856"))
    )
    (comp (ref "MAX20")
      (value "MAX31856")
      (footprint "eagle-import:21-066J-14-M")
      (fields (field (name "MPN") "MAX31856MUD+ "))
      (libsource (lib "eagle-import") (part "MAX31856"))
    )
    (comp (ref "R58")
      (value "100R")
      (footprint "eagle-import:0603")
      (libsource (lib "eagle-import") (part "R0603_100R"))
    )
    (comp (ref "R59")
      (value "100R")
      (footprint "eagle-import:0603")
      (libsource (lib "eagle-import") (part "R0603_100R"))
    )
    (comp (ref "R60")
      (value "100R")
      (footprint "eagle-import:0603")
      (libsource (lib "eagle-import") (part "R0603_100R"))
    )
    (comp (ref "R61")
      (value "100R")
      (footprint "eagle-import:0603")
      (libsource (lib "eagle-import") (part "R0603_100R"))
    )
    (comp (ref "R62")
      (value "100R")
      (footprint "eagle-import:0603")
      (libsource (lib "eagle-import") (part "R0603_100R"))
    )
    (comp (ref "R63")
      (value "100R")
      (footprint "eagle-import:0603")
      (libsource (lib "eagle-import") (part "R0603_100R"))
    )
    (comp (ref "R64")
      (value "100R")
      (footprint "eagle-import:0603")
      (libsource (lib "eagle-import") (part "R0603_100R"))
    )
    (comp (ref "R65")
      (value "100R")
      (footprint "eagle-import:0603")
      (libsource (lib "eagle-import") (part "R0603_100R"))
    )
    (comp (ref "R66")
      (value "100R")
      (footprint "eagle-import:0603")
      (libsource (lib "eagle-import") (part "R0603_100R"))
    )
    (comp (ref "R67")
      (value "100R")
      (footprint "eagle-import:0603")
      (libsource (lib "eagle-import") (part "R0603_100R"))
    )
    (comp (ref "R68")
      (value "100R")
      (footprint "eagle-import:0603")
      (libsource (lib "eagle-import") (part "R0603_100R"))
    )
    (comp (ref "R69")
      (value "100R")
      (footprint "eagle-import:0603")
      (libsource (lib "eagle-import") (part "R0603_100R"))
    )
    (comp (ref "R70")
      (value "100R")
      (footprint "eagle-import:0603")
      (libsource (lib "eagle-import") (part "R0603_100R"))
    )
    (comp (ref "R71")
      (value "100R")
      (footprint "eagle-import:0603")
      (libsource (lib "eagle-import") (part "R0603_100R"))
    )
    (comp (ref "R72")
      (value "100R")
      (footprint "eagle-import:0603")
      (libsource (lib "eagle-import") (part "R0603_100R"))
    )
    (comp (ref "R73")
      (value "100R")
      (footprint "eagle-import:0603")
      (libsource (lib "eagle-import") (part "R0603_100R"))
    )
    (comp (ref "R74")
      (value "100R")
      (footprint "eagle-import:0603")
      (libsource (lib "eagle-import") (part "R0603_100R"))
    )
    (comp (ref "R75")
      (value "100R")
      (footprint "eagle-import:0603")
      (libsource (lib "eagle-import") (part "R0603_100R"))
    )
    (comp (ref "B1")
      (value "DBLS201G")
      (footprint "eagle-import:DBS")
      (libsource (lib "eagle-import") (part "DB?GLS201"))
    )
    (comp (ref "BAT1")
      (value "S8421-45R-CR2032")
      (footprint "eagle-import:S8421-45R-CR2032")
      (libsource (lib "eagle-import") (part "S8421-45R-CR2032"))
    )
    (comp (ref "B_BACK")
      (value "222AMVBAR")
      (footprint "eagle-import:222AMVBARSWITCH")
      (fields (field (name "MPN") "222AMVBAR "))
      (libsource (lib "eagle-import") (part "222AMVBAR"))
    )
    (comp (ref "B_DOWN")
      (value "222AMVBAR")
      (footprint "eagle-import:222AMVBARSWITCH")
      (fields (field (name "MPN") "222AMVBAR "))
      (libsource (lib "eagle-import") (part "222AMVBAR"))
    )
    (comp (ref "B_LEFT")
      (value "222AMVBAR")
      (footprint "eagle-import:222AMVBARSWITCH")
      (fields (field (name "MPN") "222AMVBAR "))
      (libsource (lib "eagle-import") (part "222AMVBAR"))
    )
    (comp (ref "B_OK")
      (value "222AMVBAR")
      (footprint "eagle-import:222AMVBARSWITCH")
      (fields (field (name "MPN") "222AMVBAR "))
      (libsource (lib "eagle-import") (part "222AMVBAR"))
    )
    (comp (ref "B_RESET")
      (value "222AMVBAR")
      (footprint "eagle-import:222AMVBARSWITCH")
      (fields (field (name "MPN") "222AMVBAR "))
      (libsource (lib "eagle-import") (part "222AMVBAR"))
    )
    (comp (ref "B_RIGHT")
      (value "222AMVBAR")
      (footprint "eagle-import:222AMVBARSWITCH")
      (fields (field (name "MPN") "222AMVBAR "))
      (libsource (lib "eagle-import") (part "222AMVBAR"))
    )
    (comp (ref "B_UP")
      (value "222AMVBAR")
      (footprint "eagle-import:222AMVBARSWITCH")
      (fields (field (name "MPN") "222AMVBAR "))
      (libsource (lib "eagle-import") (part "222AMVBAR"))
    )
    (comp (ref "C3")
      (value "0.1uF")
      (footprint "eagle-import:0603")
      (libsource (lib "eagle-import") (part "C0603_0.1UF"))
    )
    (comp (ref "C4")
      (value "0.1uF")
      (footprint "eagle-import:0603")
      (libsource (lib "eagle-import") (part "C0603_0.1UF"))
    )
    (comp (ref "C20")
      (value "0.1uF")
      (footprint "eagle-import:0603")
      (libsource (lib "eagle-import") (part "C0603_0.1UF"))
    )
    (comp (ref "C21")
      (value "0.1uF")
      (footprint "eagle-import:0603")
      (libsource (lib "eagle-import") (part "C0603_0.1UF"))
    )
    (comp (ref "C22")
      (value "0.1uF")
      (footprint "eagle-import:0603")
      (libsource (lib "eagle-import") (part "C0603_0.1UF"))
    )
    (comp (ref "C23")
      (value "0.1uF")
      (footprint "eagle-import:0603")
      (libsource (lib "eagle-import") (part "C0603_0.1UF"))
    )
    (comp (ref "C24")
      (value "0.1uF")
      (footprint "eagle-import:0603")
      (libsource (lib "eagle-import") (part "C0603_0.1UF"))
    )
    (comp (ref "C25")
      (value "0.1uF")
      (footprint "eagle-import:0603")
      (libsource (lib "eagle-import") (part "C0603_0.1UF"))
    )
    (comp (ref "C26")
      (value "0.1uF")
      (footprint "eagle-import:0603")
      (libsource (lib "eagle-import") (part "C0603_0.1UF"))
    )
    (comp (ref "C27")
      (value "10uF")
      (footprint "eagle-import:1206")
      (libsource (lib "eagle-import") (part "C1206_10UF"))
    )
    (comp (ref "C28")
      (value "0.1uF")
      (footprint "eagle-import:0603")
      (libsource (lib "eagle-import") (part "C0603_0.1UF"))
    )
    (comp (ref "C29")
      (value "0.1uF")
      (footprint "eagle-import:0603")
      (libsource (lib "eagle-import") (part "C0603_0.1UF"))
    )
    (comp (ref "C30")
      (value "0.1uF")
      (footprint "eagle-import:0603")
      (libsource (lib "eagle-import") (part "C0603_0.1UF"))
    )
    (comp (ref "C31")
      (value "0.1uF")
      (footprint "eagle-import:0603")
      (libsource (lib "eagle-import") (part "C0603_0.1UF"))
    )
    (comp (ref "C32")
      (value "0.1uF")
      (footprint "eagle-import:0603")
      (libsource (lib "eagle-import") (part "C0603_0.1UF"))
    )
    (comp (ref "C33")
      (value "0.1uF")
      (footprint "eagle-import:0603")
      (libsource (lib "eagle-import") (part "C0603_0.1UF"))
    )
    (comp (ref "C34")
      (value "0.1uF")
      (footprint "eagle-import:0603")
      (libsource (lib "eagle-import") (part "C0603_0.1UF"))
    )
    (comp (ref "C36")
      (value "10uF")
      (footprint "eagle-import:1206")
      (libsource (lib "eagle-import") (part "C1206_10UF"))
    )
    (comp (ref "C37")
      (value "10uF")
      (footprint "eagle-import:1206")
      (libsource (lib "eagle-import") (part "C1206_10UF"))
    )
    (comp (ref "C38")
      (value "0.1uF")
      (footprint "eagle-import:0603")
      (libsource (lib "eagle-import") (part "C0603_0.1UF"))
    )
    (comp (ref "C39")
      (value "47uF")
      (footprint "eagle-import:1206")
      (libsource (lib "eagle-import") (part "C1206_47UF"))
    )
    (comp (ref "C40")
      (value "1uF")
      (footprint "eagle-import:0603")
      (libsource (lib "eagle-import") (part "C0603_1UF"))
    )
    (comp (ref "C42")
      (value "0.1uF")
      (footprint "eagle-import:0603")
      (libsource (lib "eagle-import") (part "C0603_0.1UF"))
    )
    (comp (ref "C45")
      (value "0.1uF")
      (footprint "eagle-import:0603")
      (libsource (lib "eagle-import") (part "C0603_0.1UF"))
    )
    (comp (ref "C138")
      (value "47uF")
      (footprint "eagle-import:1206")
      (libsource (lib "eagle-import") (part "C1206_47UF"))
    )
    (comp (ref "C148")
      (value "0.1uF")
      (footprint "eagle-import:0603")
      (libsource (lib "eagle-import") (part "C0603_0.1UF"))
    )
    (comp (ref "C149")
      (value "0.1uF")
      (footprint "eagle-import:0603")
      (libsource (lib "eagle-import") (part "C0603_0.1UF"))
    )
    (comp (ref "C150")
      (value "1uF")
      (footprint "eagle-import:0603")
      (libsource (lib "eagle-import") (part "C0603_1UF"))
    )
    (comp (ref "CON2")
      (value "CON_PHOENIX_508_2")
      (footprint "eagle-import:MSTBV2")
      (libsource (lib "eagle-import") (part "CON_PHOENIX_508_2"))
    )
    (comp (ref "CON6")
      (value "RAPC722X")
      (footprint "eagle-import:JACK_RAPC722X")
      (libsource (lib "eagle-import") (part "RAPC722X"))
    )
    (comp (ref "CON8")
      (value "CON_PHOENIX_508_2")
      (footprint "eagle-import:MSTBV2")
      (libsource (lib "eagle-import") (part "CON_PHOENIX_508_2"))
    )
    (comp (ref "CON35")
      (value "CON_PHOENIX_508_2")
      (footprint "eagle-import:MSTBV2")
      (libsource (lib "eagle-import") (part "CON_PHOENIX_508_2"))
    )
    (comp (ref "D1")
      (value "DIODE-ZENER-MMSZ5232BS")
      (footprint "eagle-import:SOD-323")
      (fields (field (name "MPN") "CMDZ15L TR "))
      (libsource (lib "eagle-import") (part "DIODE-ZENER-MMSZ5232BS"))
    )
    (comp (ref "IC1")
      (value "ATMEGA2560-16AU")
      (footprint "eagle-import:TQFP100")
      (libsource (lib "eagle-import") (part "ATMEGAAU2560-16"))
    )
    (comp (ref "INA1")
      (value "TI-INA226")
      (footprint "eagle-import:TI-INA226")
      (libsource (lib "eagle-import") (part "TI-INA226"))
    )
    (comp (ref "INA2")
      (value "TI-INA226")
      (footprint "eagle-import:TI-INA226")
      (libsource (lib "eagle-import") (part "TI-INA226"))
    )
    (comp (ref "JP1")
      (value "AVR-ISP-6")
      (footprint "eagle-import:AVR-ISP-6")
      (libsource (lib "eagle-import") (part "AVR-ISP-6"))
    )
    (comp (ref "JP2")
      (value "PINHD-1X3")
      (footprint "eagle-import:1X03")
      (libsource (lib "eagle-import") (part "PINHD-1X3"))
    )
    (comp (ref "JP3")
      (value "PINHD-1X3")
      (footprint "eagle-import:1X03")
      (libsource (lib "eagle-import") (part "PINHD-1X3"))
    )
    (comp (ref "JP4")
      (value "PINHD-1X2")
      (footprint "eagle-import:1X02")
      (libsource (lib "eagle-import") (part "PINHD-1X2"))
    )
    (comp (ref "JP5")
      (value "PINHD-1X2")
      (footprint "eagle-import:1X02")
      (libsource (lib "eagle-import") (part "PINHD-1X2"))
    )
    (comp (ref "JP6")
      (value "PINHD-1X4")
      (footprint "eagle-import:1X04")
      (libsource (lib "eagle-import") (part "PINHD-1X4"))
    )
    (comp (ref "JP7")
      (value "PINHD-1X4")
      (footprint "eagle-import:1X04")
      (libsource (lib "eagle-import") (part "PINHD-1X4"))
    )
    (comp (ref "LCD1")
      (value "NHD-0420H1Z-FSW-GBW")
      (footprint "eagle-import:LCD_2X8PINS")
      (libsource (lib "eagle-import") (part "NHD-0420H1Z-FSW-GBW"))
    )
    (comp (ref "LED1")
      (value "LEDSMT1206")
      (footprint "eagle-import:1206")
      (libsource (lib "eagle-import") (part "LEDSMT1206"))
    )
    (comp (ref "LED2")
      (value "LEDSMT1206")
      (footprint "eagle-import:1206")
      (libsource (lib "eagle-import") (part "LEDSMT1206"))
    )
    (comp (ref "LED3")
      (value "LEDSMT1206")
      (footprint "eagle-import:1206")
      (libsource (lib "eagle-import") (part "LEDSMT1206"))
    )
    (comp (ref "LED_SD")
      (value "LEDSMT1206")
      (footprint "eagle-import:1206")
      (libsource (lib "eagle-import") (part "LEDSMT1206"))
    )
    (comp (ref "POT1")
      (value "3361P-1-103GLF")
      (footprint "eagle-import:TRIMMER_BOURNS_SMD")
      (libsource (lib "eagle-import") (part "3361P-1-103GLF"))
    )
    (comp (ref "R2")
      (value "10k")
      (footprint "eagle-import:0603")
      (libsource (lib "eagle-import") (part "R0603_10K"))
    )
    (comp (ref "R3")
      (value "10k")
      (footprint "eagle-import:0603")
      (libsource (lib "eagle-import") (part "R0603_10K"))
    )
    (comp (ref "R12")
      (value "10k")
      (footprint "eagle-import:0603")
      (libsource (lib "eagle-import") (part "R0603_10K"))
    )
    (comp (ref "R13")
      (value "10k")
      (footprint "eagle-import:0603")
      (libsource (lib "eagle-import") (part "R0603_10K"))
    )
    (comp (ref "R14")
      (value "10k")
      (footprint "eagle-import:0603")
      (libsource (lib "eagle-import") (part "R0603_10K"))
    )
    (comp (ref "R15")
      (value "10k")
      (footprint "eagle-import:0603")
      (libsource (lib "eagle-import") (part "R0603_10K"))
    )
    (comp (ref "R16")
      (value "10k")
      (footprint "eagle-import:0603")
      (libsource (lib "eagle-import") (part "R0603_10K"))
    )
    (comp (ref "R17")
      (value "10k")
      (footprint "eagle-import:0603")
      (libsource (lib "eagle-import") (part "R0603_10K"))
    )
    (comp (ref "R18")
      (value "10k")
      (footprint "eagle-import:0603")
      (libsource (lib "eagle-import") (part "R0603_10K"))
    )
    (comp (ref "R19")
      (value "10k")
      (footprint "eagle-import:0603")
      (libsource (lib "eagle-import") (part "R0603_10K"))
    )
    (comp (ref "R20")
      (value "10k")
      (footprint "eagle-import:0603")
      (libsource (lib "eagle-import") (part "R0603_10K"))
    )
    (comp (ref "R21")
      (value "10k")
      (footprint "eagle-import:0603")
      (libsource (lib "eagle-import") (part "R0603_10K"))
    )
    (comp (ref "R22")
      (value "10k")
      (footprint "eagle-import:0603")
      (libsource (lib "eagle-import") (part "R0603_10K"))
    )
    (comp (ref "R23")
      (value "10k")
      (footprint "eagle-import:0603")
      (libsource (lib "eagle-import") (part "R0603_10K"))
    )
    (comp (ref "R24")
      (value "470R")
      (footprint "eagle-import:1206")
      (libsource (lib "eagle-import") (part "R1206_470R"))
    )
    (comp (ref "R27")
      (value "1k5")
      (footprint "eagle-import:0603")
      (libsource (lib "eagle-import") (part "R0603_1K5"))
    )
    (comp (ref "R28")
      (value "1k5")
      (footprint "eagle-import:0603")
      (libsource (lib "eagle-import") (part "R0603_1K5"))
    )
    (comp (ref "R31")
      (value "1k5")
      (footprint "eagle-import:0603")
      (libsource (lib "eagle-import") (part "R0603_1K5"))
    )
    (comp (ref "R34")
      (value "2m")
      (footprint "eagle-import:R2010")
      (libsource (lib "eagle-import") (part "R2010_PRE"))
    )
    (comp (ref "R35")
      (value "1M")
      (footprint "eagle-import:0603")
      (libsource (lib "eagle-import") (part "R0603_1M"))
    )
    (comp (ref "R38")
      (value "10k")
      (footprint "eagle-import:0603")
      (libsource (lib "eagle-import") (part "R0603_10K"))
    )
    (comp (ref "R39")
      (value "10k")
      (footprint "eagle-import:0603")
      (libsource (lib "eagle-import") (part "R0603_10K"))
    )
    (comp (ref "R91")
      (value "10k")
      (footprint "eagle-import:0603")
      (libsource (lib "eagle-import") (part "R0603_10K"))
    )
    (comp (ref "R92")
      (value "10k")
      (footprint "eagle-import:0603")
      (libsource (lib "eagle-import") (part "R0603_10K"))
    )
    (comp (ref "R95")
      (value "2m")
      (footprint "eagle-import:R2010")
      (libsource (lib "eagle-import") (part "R2010_PRE"))
    )
    (comp (ref "RTC1")
      (value "DS3231M")
      (footprint "eagle-import:SOIC8")
      (libsource (lib "eagle-import") (part "DS3231M"))
    )
    (comp (ref "SERIAL")
      (value "MA04-1")
      (footprint "eagle-import:MA04-1")
      (libsource (lib "eagle-import") (part "MA04-1"))
    )
    (comp (ref "VR2")
      (value "LM78M05")
      (footprint "eagle-import:TO-252")
      (fields (field (name "MPN") "LM78M05CDTX/NOPB "))
      (libsource (lib "eagle-import") (part "LM78M05"))
    )
    (comp (ref "VR3")
      (value "LD1117-33")
      (footprint "eagle-import:SOT223-THERMAL")
      (fields (field (name "MPN") "LD1117S33CTR "))
      (libsource (lib "eagle-import") (part "LD1117-33"))
    )
    (comp (ref "Y1")
      (value "CSTCE16M0V53-R0")
      (footprint "eagle-import:CSTCE_V")
      (libsource (lib "eagle-import") (part "CSTCE16M0V53-R0"))
    )
    (comp (ref "C2")
      (value "0.1uF")
      (footprint "eagle-import:0603")
      (libsource (lib "eagle-import") (part "C0603_0.1UF"))
    )
    (comp (ref "C8")
      (value "0.1uF")
      (footprint "eagle-import:0603")
      (libsource (lib "eagle-import") (part "C0603_0.1UF"))
    )
    (comp (ref "C9")
      (value "10nF")
      (footprint "eagle-import:0603")
      (libsource (lib "eagle-import") (part "C0603_10NF"))
    )
    (comp (ref "C10")
      (value "10nF")
      (footprint "eagle-import:0603")
      (libsource (lib "eagle-import") (part "C0603_10NF"))
    )
    (comp (ref "C13")
      (value "1uF")
      (footprint "eagle-import:0603")
      (libsource (lib "eagle-import") (part "C0603_1UF"))
    )
    (comp (ref "C14")
      (value "10uF")
      (footprint "eagle-import:1206")
      (libsource (lib "eagle-import") (part "C1206_10UF"))
    )
    (comp (ref "C16")
      (value "10nF")
      (footprint "eagle-import:0603")
      (libsource (lib "eagle-import") (part "C0603_10NF"))
    )
    (comp (ref "C19")
      (value "1uF")
      (footprint "eagle-import:0603")
      (libsource (lib "eagle-import") (part "C0603_1UF"))
    )
    (comp (ref "C35")
      (value "0.1uF")
      (footprint "eagle-import:0603")
      (libsource (lib "eagle-import") (part "C0603_0.1UF"))
    )
    (comp (ref "C43")
      (value "47uF")
      (footprint "eagle-import:1206")
      (libsource (lib "eagle-import") (part "C1206_47UF"))
    )
    (comp (ref "C44")
      (value "0.1uF")
      (footprint "eagle-import:0603")
      (libsource (lib "eagle-import") (part "C0603_0.1UF"))
    )
    (comp (ref "C136")
      (value "10nF")
      (footprint "eagle-import:0603")
      (libsource (lib "eagle-import") (part "C0603_10NF"))
    )
    (comp (ref "C137")
      (value "10nF")
      (footprint "eagle-import:0603")
      (libsource (lib "eagle-import") (part "C0603_10NF"))
    )
    (comp (ref "C139")
      (value "0.1uF")
      (footprint "eagle-import:0603")
      (libsource (lib "eagle-import") (part "C0603_0.1UF"))
    )
    (comp (ref "C140")
      (value "0.1uF")
      (footprint "eagle-import:0603")
      (libsource (lib "eagle-import") (part "C0603_0.1UF"))
    )
    (comp (ref "C141")
      (value "10nF")
      (footprint "eagle-import:0603")
      (libsource (lib "eagle-import") (part "C0603_10NF"))
    )
    (comp (ref "C142")
      (value "10nF")
      (footprint "eagle-import:0603")
      (libsource (lib "eagle-import") (part "C0603_10NF"))
    )
    (comp (ref "C143")
      (value "10nF")
      (footprint "eagle-import:0603")
      (libsource (lib "eagle-import") (part "C0603_10NF"))
    )
    (comp (ref "C144")
      (value "10nF")
      (footprint "eagle-import:0603")
      (libsource (lib "eagle-import") (part "C0603_10NF"))
    )
    (comp (ref "C145")
      (value "1uF")
      (footprint "eagle-import:0603")
      (libsource (lib "eagle-import") (part "C0603_1UF"))
    )
    (comp (ref "C146")
      (value "0.1uF")
      (footprint "eagle-import:0603")
      (libsource (lib "eagle-import") (part "C0603_0.1UF"))
    )
    (comp (ref "C147")
      (value "0.1uF")
      (footprint "eagle-import:0603")
      (libsource (lib "eagle-import") (part "C0603_0.1UF"))
    )
    (comp (ref "C151")
      (value "0.1uF")
      (footprint "eagle-import:0603")
      (libsource (lib "eagle-import") (part "C0603_0.1UF"))
    )
    (comp (ref "CON3")
      (value "CON_PHOENIX_508_2")
      (footprint "eagle-import:MSTBV2")
      (libsource (lib "eagle-import") (part "CON_PHOENIX_508_2"))
    )
    (comp (ref "CON4")
      (value "CON_PHOENIX_508_2")
      (footprint "eagle-import:MSTBV2")
      (libsource (lib "eagle-import") (part "CON_PHOENIX_508_2"))
    )
    (comp (ref "CON5")
      (value "CON_PHOENIX_508_2")
      (footprint "eagle-import:MSTBV2")
      (libsource (lib "eagle-import") (part "CON_PHOENIX_508_2"))
    )
    (comp (ref "CON7")
      (value "MOLEX_5033981892")
      (footprint "eagle-import:CONNECTOR_SDCARD_5033981892")
      (libsource (lib "eagle-import") (part "MOLEX_5033981892"))
    )
    (comp (ref "CON28")
      (value "CON_PHOENIX_508_2")
      (footprint "eagle-import:MSTBV2")
      (libsource (lib "eagle-import") (part "CON_PHOENIX_508_2"))
    )
    (comp (ref "CON29")
      (value "CON_PHOENIX_508_2")
      (footprint "eagle-import:MSTBV2")
      (libsource (lib "eagle-import") (part "CON_PHOENIX_508_2"))
    )
    (comp (ref "CON30")
      (value "CON_PHOENIX_508_2")
      (footprint "eagle-import:MSTBV2")
      (libsource (lib "eagle-import") (part "CON_PHOENIX_508_2"))
    )
    (comp (ref "CON31")
      (value "CON_PHOENIX_508_2")
      (footprint "eagle-import:MSTBV2")
      (libsource (lib "eagle-import") (part "CON_PHOENIX_508_2"))
    )
    (comp (ref "CON33")
      (value "CON_PHOENIX_508_2")
      (footprint "eagle-import:MSTBV2")
      (libsource (lib "eagle-import") (part "CON_PHOENIX_508_2"))
    )
    (comp (ref "CON34")
      (value "CON_PHOENIX_508_2")
      (footprint "eagle-import:MSTBV2")
      (libsource (lib "eagle-import") (part "CON_PHOENIX_508_2"))
    )
    (comp (ref "D2")
      (value "BAT54S")
      (footprint "eagle-import:SOT23")
      (libsource (lib "eagle-import") (part "BAT54S"))
    )
    (comp (ref "D3")
      (value "BAT54S")
      (footprint "eagle-import:SOT23")
      (libsource (lib "eagle-import") (part "BAT54S"))
    )
    (comp (ref "F1")
      (value "0ZCJ0005FF2E")
      (footprint "eagle-import:0ZCJ_SERIES")
      (libsource (lib "eagle-import") (part "0ZCJ0005FF2E"))
    )
    (comp (ref "F2")
      (value "0ZCJ0005FF2E")
      (footprint "eagle-import:0ZCJ_SERIES")
      (libsource (lib "eagle-import") (part "0ZCJ0005FF2E"))
    )
    (comp (ref "IC2")
      (value "ADG732")
      (footprint "eagle-import:QFP50P900X900X105-48")
      (libsource (lib "eagle-import") (part "ADG732TQFP48"))
    )
    (comp (ref "IC3")
      (value "74AHCT1G126")
      (footprint "eagle-import:SOT353")
      (libsource (lib "eagle-import") (part "74AHCT1G126"))
    )
    (comp (ref "JTAG1")
      (value "AVR_DEBUG")
      (footprint "eagle-import:2X5-PTH-1.27MM")
      (libsource (lib "eagle-import") (part "AVR_DEBUG"))
    )
    (comp (ref "R1")
      (value "39k")
      (footprint "eagle-import:0603")
      (libsource (lib "eagle-import") (part "R0603_39K"))
    )
    (comp (ref "R6")
      (value "10k")
      (footprint "eagle-import:0603")
      (libsource (lib "eagle-import") (part "R0603_10K"))
    )
    (comp (ref "R7")
      (value "39k")
      (footprint "eagle-import:0603")
      (libsource (lib "eagle-import") (part "R0603_39K"))
    )
    (comp (ref "R8")
      (value "10k")
      (footprint "eagle-import:0603")
      (libsource (lib "eagle-import") (part "R0603_10K"))
    )
    (comp (ref "R9")
      (value "10k")
      (footprint "eagle-import:0603")
      (libsource (lib "eagle-import") (part "R0603_10K"))
    )
    (comp (ref "R10")
      (value "100R")
      (footprint "eagle-import:0603")
      (libsource (lib "eagle-import") (part "R0603_100R"))
    )
    (comp (ref "R30")
      (value "10k")
      (footprint "eagle-import:0603")
      (libsource (lib "eagle-import") (part "R0603_10K"))
    )
    (comp (ref "R36")
      (value "10k")
      (footprint "eagle-import:0603")
      (libsource (lib "eagle-import") (part "R0603_10K"))
    )
    (comp (ref "R37")
      (value "10k")
      (footprint "eagle-import:0603")
      (libsource (lib "eagle-import") (part "R0603_10K"))
    )
    (comp (ref "R40")
      (value "10k")
      (footprint "eagle-import:0603")
      (libsource (lib "eagle-import") (part "R0603_10K"))
    )
    (comp (ref "R41")
      (value "10k")
      (footprint "eagle-import:0603")
      (libsource (lib "eagle-import") (part "R0603_10K"))
    )
    (comp (ref "R42")
      (value "10k")
      (footprint "eagle-import:0603")
      (libsource (lib "eagle-import") (part "R0603_10K"))
    )
    (comp (ref "R43")
      (value "10k")
      (footprint "eagle-import:0603")
      (libsource (lib "eagle-import") (part "R0603_10K"))
    )
    (comp (ref "R76")
      (value "1k5")
      (footprint "eagle-import:0603")
      (libsource (lib "eagle-import") (part "R0603_1K5"))
    )
    (comp (ref "R83")
      (value "100R")
      (footprint "eagle-import:0603")
      (libsource (lib "eagle-import") (part "R0603_100R"))
    )
    (comp (ref "R84")
      (value "10k")
      (footprint "eagle-import:0603")
      (libsource (lib "eagle-import") (part "R0603_10K"))
    )
    (comp (ref "R85")
      (value "100R")
      (footprint "eagle-import:0603")
      (libsource (lib "eagle-import") (part "R0603_100R"))
    )
    (comp (ref "R86")
      (value "10k")
      (footprint "eagle-import:0603")
      (libsource (lib "eagle-import") (part "R0603_10K"))
    )
    (comp (ref "R87")
      (value "100R")
      (footprint "eagle-import:0603")
      (libsource (lib "eagle-import") (part "R0603_100R"))
    )
    (comp (ref "R88")
      (value "10k")
      (footprint "eagle-import:0603")
      (libsource (lib "eagle-import") (part "R0603_10K"))
    )
    (comp (ref "R89")
      (value "100R")
      (footprint "eagle-import:0603")
      (libsource (lib "eagle-import") (part "R0603_100R"))
    )
    (comp (ref "R90")
      (value "10k")
      (footprint "eagle-import:0603")
      (libsource (lib "eagle-import") (part "R0603_10K"))
    )
    (comp (ref "R93")
      (value "10k")
      (footprint "eagle-import:0603")
      (libsource (lib "eagle-import") (part "R0603_10K"))
    )
    (comp (ref "TVS1")
      (value "GSOT24C")
      (footprint "eagle-import:SOT23_3PAD")
      (libsource (lib "eagle-import") (part "GSOT24C"))
    )
    (comp (ref "U1")
      (value "74LVC2244AD")
      (footprint "eagle-import:SOIC20")
      (fields (field (name "MPN") "SN74LVC2244ADWR "))
      (libsource (lib "eagle-import") (part "74LVC2244AD"))
    )
    (comp (ref "U2")
      (value "74LVC2G17SOT363")
      (footprint "eagle-import:SOT363")
      (libsource (lib "eagle-import") (part "74LVC2G17SOT363"))
    )
    (comp (ref "U3")
      (value "74LVC2G17SOT363")
      (footprint "eagle-import:SOT363")
      (libsource (lib "eagle-import") (part "74LVC2G17SOT363"))
    )
    (comp (ref "U5")
      (value "74LVC2G17SOT363")
      (footprint "eagle-import:SOT363")
      (libsource (lib "eagle-import") (part "74LVC2G17SOT363"))
    )
    (comp (ref "VR4")
      (value "LT1461DHS8")
      (footprint "eagle-import:SOIC8-LT1461")
      (libsource (lib "eagle-import") (part "LT1461DHS8"))
    )
    (comp (ref "VREF_ON")
      (value "LEDSMT1206")
      (footprint "eagle-import:1206")
      (libsource (lib "eagle-import") (part "LEDSMT1206"))
    )
  )
  (nets
    (net (code "1") (name "3V3") (class "Default")
      (node (ref "C100") (pin "1") (pinfunction "1_1") (pintype "passive"))
      (node (ref "C104") (pin "1") (pinfunction "1_1") (pintype "passive"))
      (node (ref "C105") (pin "1") (pinfunction "1_1") (pintype "passive"))
      (node (ref "C109") (pin "1") (pinfunction "1_1") (pintype "passive"))
      (node (ref "C110") (pin "1") (pinfunction "1_1") (pintype "passive"))
      (node (ref "C114") (pin "1") (pinfunction "1_1") (pintype "passive"))
      (node (ref "C115") (pin "1") (pinfunction "1_1") (pintype "passive"))
      (node (ref "C119") (pin "1") (pinfunction "1_1") (pintype "passive"))
      (node (ref "C120") (pin "1") (pinfunction "1_1") (pintype "passive"))
      (node (ref "C124") (pin "1") (pinfunction "1_1") (pintype "passive"))
      (node (ref "C125") (pin "1") (pinfunction "1_1") (pintype "passive"))
      (node (ref "C129") (pin "1") (pinfunction "1_1") (pintype "passive"))
      (node (ref "C130") (pin "1") (pinfunction "1_1") (pintype "passive"))
      (node (ref "C134") (pin "1") (pinfunction "1_1") (pintype "passive"))
      (node (ref "C135") (pin "1") (pinfunction "1_1") (pintype "passive"))
      (node (ref "C139") (pin "1") (pinfunction "1_1") (pintype "passive"))
      (node (ref "C140") (pin "1") (pinfunction "1_1") (pintype "passive"))
      (node (ref "C145") (pin "1") (pinfunction "1_1") (pintype "passive"))
      (node (ref "C146") (pin "1") (pinfunction "1_1") (pintype "passive"))
      (node (ref "C151") (pin "1") (pinfunction "1_1") (pintype "passive"))
      (node (ref "C17") (pin "1") (pinfunction "1_1") (pintype "passive"))
      (node (ref "C18") (pin "1") (pinfunction "1_1") (pintype "passive"))
      (node (ref "C19") (pin "1") (pinfunction "1_1") (pintype "passive"))
      (node (ref "C2") (pin "1") (pinfunction "1_1") (pintype "passive"))
      (node (ref "C29") (pin "1") (pinfunction "1_1") (pintype "passive"))
      (node (ref "C36") (pin "1") (pinfunction "1_1") (pintype "passive"))
      (node (ref "C41") (pin "1") (pinfunction "1_1") (pintype "passive"))
      (node (ref "C43") (pin "1") (pinfunction "1_1") (pintype "passive"))
      (node (ref "C49") (pin "1") (pinfunction "1_1") (pintype "passive"))
      (node (ref "C50") (pin "1") (pinfunction "1_1") (pintype "passive"))
      (node (ref "C54") (pin "1") (pinfunction "1_1") (pintype "passive"))
      (node (ref "C55") (pin "1") (pinfunction "1_1") (pintype "passive"))
      (node (ref "C59") (pin "1") (pinfunction "1_1") (pintype "passive"))
      (node (ref "C60") (pin "1") (pinfunction "1_1") (pintype "passive"))
      (node (ref "C64") (pin "1") (pinfunction "1_1") (pintype "passive"))
      (node (ref "C65") (pin "1") (pinfunction "1_1") (pintype "passive"))
      (node (ref "C69") (pin "1") (pinfunction "1_1") (pintype "passive"))
      (node (ref "C7") (pin "1") (pinfunction "1_1") (pintype "passive"))
      (node (ref "C70") (pin "1") (pinfunction "1_1") (pintype "passive"))
      (node (ref "C74") (pin "1") (pinfunction "1_1") (pintype "passive"))
      (node (ref "C75") (pin "1") (pinfunction "1_1") (pintype "passive"))
      (node (ref "C79") (pin "1") (pinfunction "1_1") (pintype "passive"))
      (node (ref "C8") (pin "1") (pinfunction "1_1") (pintype "passive"))
      (node (ref "C80") (pin "1") (pinfunction "1_1") (pintype "passive"))
      (node (ref "C84") (pin "1") (pinfunction "1_1") (pintype "passive"))
      (node (ref "C85") (pin "1") (pinfunction "1_1") (pintype "passive"))
      (node (ref "C89") (pin "1") (pinfunction "1_1") (pintype "passive"))
      (node (ref "C90") (pin "1") (pinfunction "1_1") (pintype "passive"))
      (node (ref "C94") (pin "1") (pinfunction "1_1") (pintype "passive"))
      (node (ref "C95") (pin "1") (pinfunction "1_1") (pintype "passive"))
      (node (ref "C99") (pin "1") (pinfunction "1_1") (pintype "passive"))
      (node (ref "CON7") (pin "4") (pinfunction "VDD_4") (pintype "bidirectional"))
      (node (ref "IC2") (pin "13") (pinfunction "VDD_13") (pintype "bidirectional"))
      (node (ref "IC2") (pin "14") (pinfunction "VDD_14") (pintype "bidirectional"))
      (node (ref "MAX1") (pin "5") (pinfunction "AVDD_5") (pintype "power_in"))
      (node (ref "MAX1") (pin "8") (pinfunction "DVDD_8") (pintype "power_in"))
      (node (ref "MAX10") (pin "5") (pinfunction "AVDD_5") (pintype "power_in"))
      (node (ref "MAX10") (pin "8") (pinfunction "DVDD_8") (pintype "power_in"))
      (node (ref "MAX11") (pin "5") (pinfunction "AVDD_5") (pintype "power_in"))
      (node (ref "MAX11") (pin "8") (pinfunction "DVDD_8") (pintype "power_in"))
      (node (ref "MAX12") (pin "5") (pinfunction "AVDD_5") (pintype "power_in"))
      (node (ref "MAX12") (pin "8") (pinfunction "DVDD_8") (pintype "power_in"))
      (node (ref "MAX13") (pin "5") (pinfunction "AVDD_5") (pintype "power_in"))
      (node (ref "MAX13") (pin "8") (pinfunction "DVDD_8") (pintype "power_in"))
      (node (ref "MAX14") (pin "5") (pinfunction "AVDD_5") (pintype "power_in"))
      (node (ref "MAX14") (pin "8") (pinfunction "DVDD_8") (pintype "power_in"))
      (node (ref "MAX15") (pin "5") (pinfunction "AVDD_5") (pintype "power_in"))
      (node (ref "MAX15") (pin "8") (pinfunction "DVDD_8") (pintype "power_in"))
      (node (ref "MAX16") (pin "5") (pinfunction "AVDD_5") (pintype "power_in"))
      (node (ref "MAX16") (pin "8") (pinfunction "DVDD_8") (pintype "power_in"))
      (node (ref "MAX17") (pin "5") (pinfunction "AVDD_5") (pintype "power_in"))
      (node (ref "MAX17") (pin "8") (pinfunction "DVDD_8") (pintype "power_in"))
      (node (ref "MAX18") (pin "5") (pinfunction "AVDD_5") (pintype "power_in"))
      (node (ref "MAX18") (pin "8") (pinfunction "DVDD_8") (pintype "power_in"))
      (node (ref "MAX19") (pin "5") (pinfunction "AVDD_5") (pintype "power_in"))
      (node (ref "MAX19") (pin "8") (pinfunction "DVDD_8") (pintype "power_in"))
      (node (ref "MAX2") (pin "5") (pinfunction "AVDD_5") (pintype "power_in"))
      (node (ref "MAX2") (pin "8") (pinfunction "DVDD_8") (pintype "power_in"))
      (node (ref "MAX20") (pin "5") (pinfunction "AVDD_5") (pintype "power_in"))
      (node (ref "MAX20") (pin "8") (pinfunction "DVDD_8") (pintype "power_in"))
      (node (ref "MAX3") (pin "5") (pinfunction "AVDD_5") (pintype "power_in"))
      (node (ref "MAX3") (pin "8") (pinfunction "DVDD_8") (pintype "power_in"))
      (node (ref "MAX4") (pin "5") (pinfunction "AVDD_5") (pintype "power_in"))
      (node (ref "MAX4") (pin "8") (pinfunction "DVDD_8") (pintype "power_in"))
      (node (ref "MAX5") (pin "5") (pinfunction "AVDD_5") (pintype "power_in"))
      (node (ref "MAX5") (pin "8") (pinfunction "DVDD_8") (pintype "power_in"))
      (node (ref "MAX6") (pin "5") (pinfunction "AVDD_5") (pintype "power_in"))
      (node (ref "MAX6") (pin "8") (pinfunction "DVDD_8") (pintype "power_in"))
      (node (ref "MAX7") (pin "5") (pinfunction "AVDD_5") (pintype "power_in"))
      (node (ref "MAX7") (pin "8") (pinfunction "DVDD_8") (pintype "power_in"))
      (node (ref "MAX8") (pin "5") (pinfunction "AVDD_5") (pintype "power_in"))
      (node (ref "MAX8") (pin "8") (pinfunction "DVDD_8") (pintype "power_in"))
      (node (ref "MAX9") (pin "5") (pinfunction "AVDD_5") (pintype "power_in"))
      (node (ref "MAX9") (pin "8") (pinfunction "DVDD_8") (pintype "power_in"))
      (node (ref "R30") (pin "2") (pinfunction "2_2") (pintype "passive"))
      (node (ref "R36") (pin "1") (pinfunction "1_1") (pintype "passive"))
      (node (ref "R37") (pin "1") (pinfunction "1_1") (pintype "passive"))
      (node (ref "R93") (pin "1") (pinfunction "1_1") (pintype "passive"))
      (node (ref "U1") (pin "20") (pinfunction "VCC_20") (pintype "power_in"))
      (node (ref "U2") (pin "5") (pinfunction "VCC_5") (pintype "bidirectional"))
      (node (ref "U3") (pin "5") (pinfunction "VCC_5") (pintype "bidirectional"))
      (node (ref "U5") (pin "5") (pinfunction "VCC_5") (pintype "bidirectional"))
      (node (ref "VR3") (pin "2") (pinfunction "OUT_2") (pintype "passive"))
      (node (ref "VR3") (pin "4") (pinfunction "OUT_4") (pintype "passive"))
    )
    (net (code "2") (name "5V") (class "Default")
      (node (ref "C149") (pin "2") (pinfunction "2_2") (pintype "passive"))
      (node (ref "C150") (pin "2") (pinfunction "2_2") (pintype "passive"))
      (node (ref "C20") (pin "1") (pinfunction "1_1") (pintype "passive"))
      (node (ref "C28") (pin "1") (pinfunction "1_1") (pintype "passive"))
      (node (ref "C3") (pin "1") (pinfunction "1_1") (pintype "passive"))
      (node (ref "C30") (pin "1") (pinfunction "1_1") (pintype "passive"))
      (node (ref "C31") (pin "1") (pinfunction "1_1") (pintype "passive"))
      (node (ref "C32") (pin "1") (pinfunction "1_1") (pintype "passive"))
      (node (ref "C33") (pin "1") (pinfunction "1_1") (pintype "passive"))
      (node (ref "C35") (pin "1") (pinfunction "1_1") (pintype "passive"))
      (node (ref "C37") (pin "1") (pinfunction "1_1") (pintype "passive"))
      (node (ref "C4") (pin "2") (pinfunction "2_2") (pintype "passive"))
      (node (ref "C40") (pin "2") (pinfunction "2_2") (pintype "passive"))
      (node (ref "C42") (pin "1") (pinfunction "1_1") (pintype "passive"))
      (node (ref "C44") (pin "1") (pinfunction "1_1") (pintype "passive"))
      (node (ref "C45") (pin "1") (pinfunction "1_1") (pintype "passive"))
      (node (ref "IC1") (pin "10") (pinfunction "VCC_10") (pintype "power_in"))
      (node (ref "IC1") (pin "100") (pinfunction "AVCC_100") (pintype "power_in"))
      (node (ref "IC1") (pin "31") (pinfunction "VCC1_31") (pintype "power_in"))
      (node (ref "IC1") (pin "61") (pinfunction "VCC2_61") (pintype "power_in"))
      (node (ref "IC1") (pin "80") (pinfunction "VCC3_80") (pintype "power_in"))
      (node (ref "IC3") (pin "5") (pinfunction "VCC_5") (pintype "bidirectional"))
      (node (ref "INA1") (pin "6") (pinfunction "VS+_6") (pintype "bidirectional"))
      (node (ref "INA2") (pin "1") (pinfunction "A1_1") (pintype "bidirectional"))
      (node (ref "INA2") (pin "6") (pinfunction "VS+_6") (pintype "bidirectional"))
      (node (ref "JP1") (pin "2") (pinfunction "2_2") (pintype "passive"))
      (node (ref "JTAG1") (pin "4") (pinfunction "VCC_4") (pintype "bidirectional"))
      (node (ref "LCD1") (pin "15") (pinfunction "A_15") (pintype "power_in"))
      (node (ref "LCD1") (pin "2") (pinfunction "VDD_2") (pintype "power_in"))
      (node (ref "POT1") (pin "3") (pinfunction "A_3") (pintype "passive"))
      (node (ref "R12") (pin "2") (pinfunction "2_2") (pintype "passive"))
      (node (ref "R14") (pin "2") (pinfunction "2_2") (pintype "passive"))
      (node (ref "R16") (pin "2") (pinfunction "2_2") (pintype "passive"))
      (node (ref "R18") (pin "2") (pinfunction "2_2") (pintype "passive"))
      (node (ref "R2") (pin "2") (pinfunction "2_2") (pintype "passive"))
      (node (ref "R20") (pin "2") (pinfunction "2_2") (pintype "passive"))
      (node (ref "R22") (pin "2") (pinfunction "2_2") (pintype "passive"))
      (node (ref "R3") (pin "2") (pinfunction "2_2") (pintype "passive"))
      (node (ref "R38") (pin "1") (pinfunction "1_1") (pintype "passive"))
      (node (ref "R39") (pin "1") (pinfunction "1_1") (pintype "passive"))
      (node (ref "R40") (pin "1") (pinfunction "1_1") (pintype "passive"))
      (node (ref "R41") (pin "1") (pinfunction "1_1") (pintype "passive"))
      (node (ref "R42") (pin "1") (pinfunction "1_1") (pintype "passive"))
      (node (ref "R43") (pin "1") (pinfunction "1_1") (pintype "passive"))
      (node (ref "R91") (pin "2") (pinfunction "2_2") (pintype "passive"))
      (node (ref "RTC1") (pin "2") (pinfunction "VCC_2") (pintype "bidirectional"))
      (node (ref "SERIAL") (pin "4") (pinfunction "4_4") (pintype "passive"))
      (node (ref "VR2") (pin "2") (pinfunction "OUT_2") (pintype "passive"))
      (node (ref "VR3") (pin "3") (pinfunction "IN_3") (pintype "input"))
    )
    (net (code "3") (name "5VREF") (class "Default")
      (node (ref "C14") (pin "1") (pinfunction "1_1") (pintype "passive"))
      (node (ref "C147") (pin "1") (pinfunction "1_1") (pintype "passive"))
      (node (ref "C38") (pin "1") (pinfunction "1_1") (pintype "passive"))
      (node (ref "D2") (pin "2") (pinfunction "C2_2") (pintype "passive"))
      (node (ref "D3") (pin "2") (pinfunction "C2_2") (pintype "passive"))
      (node (ref "IC1") (pin "98") (pinfunction "AREF_98") (pintype "bidirectional"))
      (node (ref "R76") (pin "2") (pinfunction "2_2") (pintype "passive"))
      (node (ref "R84") (pin "2") (pinfunction "2_2") (pintype "passive"))
      (node (ref "R86") (pin "2") (pinfunction "2_2") (pintype "passive"))
      (node (ref "R88") (pin "2") (pinfunction "2_2") (pintype "passive"))
      (node (ref "R9") (pin "2") (pinfunction "2_2") (pintype "passive"))
      (node (ref "R90") (pin "2") (pinfunction "2_2") (pintype "passive"))
      (node (ref "VR4") (pin "6") (pinfunction "VOUT_6") (pintype "power_in"))
    )
    (net (code "4") (name "9V") (class "Default")
      (node (ref "B1") (pin "AC1") (pinfunction "AC1_AC1") (pintype "passive"))
      (node (ref "C138") (pin "1") (pinfunction "1_1") (pintype "passive"))
      (node (ref "CON6") (pin "1") (pinfunction "1_1") (pintype "passive"))
    )
    (net (code "5") (name "BUT_BACK") (class "Default")
      (node (ref "C148") (pin "2") (pinfunction "2_2") (pintype "passive"))
      (node (ref "IC1") (pin "52") (pinfunction "(RD)PG1_52") (pintype "bidirectional"))
      (node (ref "R92") (pin "2") (pinfunction "2_2") (pintype "passive"))
    )
    (net (code "6") (name "BUT_DOWN") (class "Default")
      (node (ref "C22") (pin "2") (pinfunction "2_2") (pintype "passive"))
      (node (ref "IC1") (pin "53") (pinfunction "(A8)PC0_53") (pintype "bidirectional"))
      (node (ref "R17") (pin "2") (pinfunction "2_2") (pintype "passive"))
    )
    (net (code "7") (name "BUT_LEFT") (class "Default")
      (node (ref "C21") (pin "2") (pinfunction "2_2") (pintype "passive"))
      (node (ref "IC1") (pin "51") (pinfunction "(WR)PG0_51") (pintype "bidirectional"))
      (node (ref "R15") (pin "2") (pinfunction "2_2") (pintype "passive"))
    )
    (net (code "8") (name "BUT_OK") (class "Default")
      (node (ref "C25") (pin "2") (pinfunction "2_2") (pintype "passive"))
      (node (ref "IC1") (pin "56") (pinfunction "(A11)PC3_56") (pintype "bidirectional"))
      (node (ref "R23") (pin "2") (pinfunction "2_2") (pintype "passive"))
    )
    (net (code "9") (name "BUT_RIGHT") (class "Default")
      (node (ref "C23") (pin "2") (pinfunction "2_2") (pintype "passive"))
      (node (ref "IC1") (pin "55") (pinfunction "(A10)PC2_55") (pintype "bidirectional"))
      (node (ref "R19") (pin "2") (pinfunction "2_2") (pintype "passive"))
    )
    (net (code "10") (name "BUT_UP") (class "Default")
      (node (ref "C24") (pin "2") (pinfunction "2_2") (pintype "passive"))
      (node (ref "IC1") (pin "54") (pinfunction "(A9)PC1_54") (pintype "bidirectional"))
      (node (ref "R21") (pin "2") (pinfunction "2_2") (pintype "passive"))
    )
    (net (code "11") (name "CS_MAX1") (class "Default")
      (node (ref "IC2") (pin "12") (pinfunction "S1_12") (pintype "bidirectional"))
      (node (ref "MAX1") (pin "9") (pinfunction "~{CS}_9") (pintype "passive"))
    )
    (net (code "12") (name "CS_MAX2") (class "Default")
      (node (ref "IC2") (pin "11") (pinfunction "S2_11") (pintype "bidirectional"))
      (node (ref "MAX2") (pin "9") (pinfunction "~{CS}_9") (pintype "passive"))
    )
    (net (code "13") (name "CS_MAX3") (class "Default")
      (node (ref "IC2") (pin "10") (pinfunction "S3_10") (pintype "bidirectional"))
      (node (ref "MAX3") (pin "9") (pinfunction "~{CS}_9") (pintype "passive"))
    )
    (net (code "14") (name "CS_MAX4") (class "Default")
      (node (ref "IC2") (pin "9") (pinfunction "S4_9") (pintype "bidirectional"))
      (node (ref "MAX4") (pin "9") (pinfunction "~{CS}_9") (pintype "passive"))
    )
    (net (code "15") (name "CS_MAX5") (class "Default")
      (node (ref "IC2") (pin "8") (pinfunction "S5_8") (pintype "bidirectional"))
      (node (ref "MAX5") (pin "9") (pinfunction "~{CS}_9") (pintype "passive"))
    )
    (net (code "16") (name "CS_MAX6") (class "Default")
      (node (ref "IC2") (pin "7") (pinfunction "S6_7") (pintype "bidirectional"))
      (node (ref "MAX6") (pin "9") (pinfunction "~{CS}_9") (pintype "passive"))
    )
    (net (code "17") (name "CS_MAX7") (class "Default")
      (node (ref "IC2") (pin "6") (pinfunction "S7_6") (pintype "bidirectional"))
      (node (ref "MAX7") (pin "9") (pinfunction "~{CS}_9") (pintype "passive"))
    )
    (net (code "18") (name "CS_MAX8") (class "Default")
      (node (ref "IC2") (pin "5") (pinfunction "S8_5") (pintype "bidirectional"))
      (node (ref "MAX8") (pin "9") (pinfunction "~{CS}_9") (pintype "passive"))
    )
    (net (code "19") (name "CS_MAX9") (class "Default")
      (node (ref "IC2") (pin "4") (pinfunction "S9_4") (pintype "bidirectional"))
      (node (ref "MAX9") (pin "9") (pinfunction "~{CS}_9") (pintype "passive"))
    )
    (net (code "20") (name "CS_MAX10") (class "Default")
      (node (ref "IC2") (pin "3") (pinfunction "S10_3") (pintype "bidirectional"))
      (node (ref "MAX10") (pin "9") (pinfunction "~{CS}_9") (pintype "passive"))
    )
    (net (code "21") (name "CS_MAX11") (class "Default")
      (node (ref "IC2") (pin "2") (pinfunction "S11_2") (pintype "bidirectional"))
      (node (ref "MAX11") (pin "9") (pinfunction "~{CS}_9") (pintype "passive"))
    )
    (net (code "22") (name "CS_MAX12") (class "Default")
      (node (ref "IC2") (pin "1") (pinfunction "S12_1") (pintype "bidirectional"))
      (node (ref "MAX12") (pin "9") (pinfunction "~{CS}_9") (pintype "passive"))
    )
    (net (code "23") (name "CS_MAX13") (class "Default")
      (node (ref "IC2") (pin "48") (pinfunction "S13_48") (pintype "bidirectional"))
      (node (ref "MAX13") (pin "9") (pinfunction "~{CS}_9") (pintype "passive"))
    )
    (net (code "24") (name "CS_MAX14") (class "Default")
      (node (ref "IC2") (pin "47") (pinfunction "S14_47") (pintype "bidirectional"))
      (node (ref "MAX14") (pin "9") (pinfunction "~{CS}_9") (pintype "passive"))
    )
    (net (code "25") (name "CS_MAX15") (class "Default")
      (node (ref "IC2") (pin "46") (pinfunction "S15_46") (pintype "bidirectional"))
      (node (ref "MAX15") (pin "9") (pinfunction "~{CS}_9") (pintype "passive"))
    )
    (net (code "26") (name "CS_MAX16") (class "Default")
      (node (ref "IC2") (pin "45") (pinfunction "S16_45") (pintype "bidirectional"))
      (node (ref "MAX16") (pin "9") (pinfunction "~{CS}_9") (pintype "passive"))
    )
    (net (code "27") (name "CS_MAX17") (class "Default")
      (node (ref "IC2") (pin "25") (pinfunction "S17_25") (pintype "bidirectional"))
      (node (ref "MAX17") (pin "9") (pinfunction "~{CS}_9") (pintype "passive"))
    )
    (net (code "28") (name "CS_MAX18") (class "Default")
      (node (ref "IC2") (pin "26") (pinfunction "S18_26") (pintype "bidirectional"))
      (node (ref "MAX18") (pin "9") (pinfunction "~{CS}_9") (pintype "passive"))
    )
    (net (code "29") (name "CS_MAX19") (class "Default")
      (node (ref "IC2") (pin "27") (pinfunction "S19_27") (pintype "bidirectional"))
      (node (ref "MAX19") (pin "9") (pinfunction "~{CS}_9") (pintype "passive"))
    )
    (net (code "30") (name "CS_MAX20") (class "Default")
      (node (ref "IC2") (pin "28") (pinfunction "S20_28") (pintype "bidirectional"))
      (node (ref "MAX20") (pin "9") (pinfunction "~{CS}_9") (pintype "passive"))
    )
    (net (code "31") (name "CS_MUX") (class "Default")
      (node (ref "IC1") (pin "23") (pinfunction "(OC2A/PCINT4)PB4_23") (pintype "bidirectional"))
      (node (ref "U5") (pin "3") (pinfunction "I1_3") (pintype "input"))
    )
    (net (code "32") (name "CS_MUX_3V3") (class "Default")
      (node (ref "IC2") (pin "20") (pinfunction "~{CS}_20") (pintype "bidirectional"))
      (node (ref "U5") (pin "4") (pinfunction "O1_4") (pintype "output"))
    )
    (net (code "33") (name "CS_SD") (class "Default")
      (node (ref "IC1") (pin "41") (pinfunction "PL6_41") (pintype "bidirectional"))
      (node (ref "U2") (pin "1") (pinfunction "I_1") (pintype "input"))
    )
    (net (code "34") (name "CS_SD_3V3") (class "Default")
      (node (ref "CON7") (pin "2") (pinfunction "DAT3/CD_2") (pintype "bidirectional"))
      (node (ref "U2") (pin "6") (pinfunction "O_6") (pintype "output"))
    )
    (net (code "35") (name "DB4") (class "Default")
      (node (ref "IC1") (pin "60") (pinfunction "(A15)PC7_60") (pintype "bidirectional"))
      (node (ref "LCD1") (pin "11") (pinfunction "DB4_11") (pintype "bidirectional"))
    )
    (net (code "36") (name "DB5") (class "Default")
      (node (ref "IC1") (pin "59") (pinfunction "(A14)PC6_59") (pintype "bidirectional"))
      (node (ref "LCD1") (pin "12") (pinfunction "DB5_12") (pintype "bidirectional"))
    )
    (net (code "37") (name "DB6") (class "Default")
      (node (ref "IC1") (pin "58") (pinfunction "(A13)PC5_58") (pintype "bidirectional"))
      (node (ref "LCD1") (pin "13") (pinfunction "DB6_13") (pintype "bidirectional"))
    )
    (net (code "38") (name "DB7") (class "Default")
      (node (ref "IC1") (pin "57") (pinfunction "(A12)PC4_57") (pintype "bidirectional"))
      (node (ref "LCD1") (pin "14") (pinfunction "DB7_14") (pintype "bidirectional"))
    )
    (net (code "39") (name "EN_MUX") (class "Default")
      (node (ref "IC1") (pin "25") (pinfunction "(OC1B/PCINT6)PB6_25") (pintype "bidirectional"))
      (node (ref "U3") (pin "3") (pinfunction "I1_3") (pintype "input"))
    )
    (net (code "40") (name "EN_MUX_3V3") (class "Default")
      (node (ref "IC2") (pin "22") (pinfunction "~{EN}_22") (pintype "bidirectional"))
      (node (ref "U3") (pin "4") (pinfunction "O1_4") (pintype "output"))
    )
    (net (code "41") (name "GND") (class "Default")
      (node (ref "B1") (pin "-") (pinfunction "-_-") (pintype "passive"))
      (node (ref "BAT1") (pin "2-") (pinfunction "2-_2-") (pintype "bidirectional"))
      (node (ref "B_BACK") (pin "1") (pinfunction "1_1") (pintype "passive"))
      (node (ref "B_BACK") (pin "3") (pinfunction "2_3") (pintype "passive"))
      (node (ref "B_DOWN") (pin "1") (pinfunction "1_1") (pintype "passive"))
      (node (ref "B_DOWN") (pin "3") (pinfunction "2_3") (pintype "passive"))
      (node (ref "B_LEFT") (pin "1") (pinfunction "1_1") (pintype "passive"))
      (node (ref "B_LEFT") (pin "3") (pinfunction "2_3") (pintype "passive"))
      (node (ref "B_OK") (pin "1") (pinfunction "1_1") (pintype "passive"))
      (node (ref "B_OK") (pin "3") (pinfunction "2_3") (pintype "passive"))
      (node (ref "B_RESET") (pin "1") (pinfunction "1_1") (pintype "passive"))
      (node (ref "B_RESET") (pin "3") (pinfunction "2_3") (pintype "passive"))
      (node (ref "B_RIGHT") (pin "1") (pinfunction "1_1") (pintype "passive"))
      (node (ref "B_RIGHT") (pin "3") (pinfunction "2_3") (pintype "passive"))
      (node (ref "B_UP") (pin "1") (pinfunction "1_1") (pintype "passive"))
      (node (ref "B_UP") (pin "3") (pinfunction "2_3") (pintype "passive"))
      (node (ref "C10") (pin "2") (pinfunction "2_2") (pintype "passive"))
      (node (ref "C100") (pin "2") (pinfunction "2_2") (pintype "passive"))
      (node (ref "C102") (pin "2") (pinfunction "2_2") (pintype "passive"))
      (node (ref "C103") (pin "1") (pinfunction "1_1") (pintype "passive"))
      (node (ref "C104") (pin "2") (pinfunction "2_2") (pintype "passive"))
      (node (ref "C105") (pin "2") (pinfunction "2_2") (pintype "passive"))
      (node (ref "C107") (pin "2") (pinfunction "2_2") (pintype "passive"))
      (node (ref "C108") (pin "1") (pinfunction "1_1") (pintype "passive"))
      (node (ref "C109") (pin "2") (pinfunction "2_2") (pintype "passive"))
      (node (ref "C110") (pin "2") (pinfunction "2_2") (pintype "passive"))
      (node (ref "C112") (pin "2") (pinfunction "2_2") (pintype "passive"))
      (node (ref "C113") (pin "1") (pinfunction "1_1") (pintype "passive"))
      (node (ref "C114") (pin "2") (pinfunction "2_2") (pintype "passive"))
      (node (ref "C115") (pin "2") (pinfunction "2_2") (pintype "passive"))
      (node (ref "C117") (pin "2") (pinfunction "2_2") (pintype "passive"))
      (node (ref "C118") (pin "1") (pinfunction "1_1") (pintype "passive"))
      (node (ref "C119") (pin "2") (pinfunction "2_2") (pintype "passive"))
      (node (ref "C12") (pin "2") (pinfunction "2_2") (pintype "passive"))
      (node (ref "C120") (pin "2") (pinfunction "2_2") (pintype "passive"))
      (node (ref "C122") (pin "2") (pinfunction "2_2") (pintype "passive"))
      (node (ref "C123") (pin "1") (pinfunction "1_1") (pintype "passive"))
      (node (ref "C124") (pin "2") (pinfunction "2_2") (pintype "passive"))
      (node (ref "C125") (pin "2") (pinfunction "2_2") (pintype "passive"))
      (node (ref "C127") (pin "2") (pinfunction "2_2") (pintype "passive"))
      (node (ref "C128") (pin "1") (pinfunction "1_1") (pintype "passive"))
      (node (ref "C129") (pin "2") (pinfunction "2_2") (pintype "passive"))
      (node (ref "C13") (pin "2") (pinfunction "2_2") (pintype "passive"))
      (node (ref "C130") (pin "2") (pinfunction "2_2") (pintype "passive"))
      (node (ref "C132") (pin "2") (pinfunction "2_2") (pintype "passive"))
      (node (ref "C133") (pin "1") (pinfunction "1_1") (pintype "passive"))
      (node (ref "C134") (pin "2") (pinfunction "2_2") (pintype "passive"))
      (node (ref "C135") (pin "2") (pinfunction "2_2") (pintype "passive"))
      (node (ref "C136") (pin "2") (pinfunction "2_2") (pintype "passive"))
      (node (ref "C137") (pin "2") (pinfunction "2_2") (pintype "passive"))
      (node (ref "C139") (pin "2") (pinfunction "2_2") (pintype "passive"))
      (node (ref "C14") (pin "2") (pinfunction "2_2") (pintype "passive"))
      (node (ref "C140") (pin "2") (pinfunction "2_2") (pintype "passive"))
      (node (ref "C141") (pin "2") (pinfunction "2_2") (pintype "passive"))
      (node (ref "C142") (pin "2") (pinfunction "2_2") (pintype "passive"))
      (node (ref "C143") (pin "2") (pinfunction "2_2") (pintype "passive"))
      (node (ref "C144") (pin "2") (pinfunction "2_2") (pintype "passive"))
      (node (ref "C145") (pin "2") (pinfunction "2_2") (pintype "passive"))
      (node (ref "C146") (pin "2") (pinfunction "2_2") (pintype "passive"))
      (node (ref "C147") (pin "2") (pinfunction "2_2") (pintype "passive"))
      (node (ref "C148") (pin "1") (pinfunction "1_1") (pintype "passive"))
      (node (ref "C149") (pin "1") (pinfunction "1_1") (pintype "passive"))
      (node (ref "C15") (pin "1") (pinfunction "1_1") (pintype "passive"))
      (node (ref "C150") (pin "1") (pinfunction "1_1") (pintype "passive"))
      (node (ref "C151") (pin "2") (pinfunction "2_2") (pintype "passive"))
      (node (ref "C16") (pin "2") (pinfunction "2_2") (pintype "passive"))
      (node (ref "C17") (pin "2") (pinfunction "2_2") (pintype "passive"))
      (node (ref "C18") (pin "2") (pinfunction "2_2") (pintype "passive"))
      (node (ref "C19") (pin "2") (pinfunction "2_2") (pintype "passive"))
      (node (ref "C2") (pin "2") (pinfunction "2_2") (pintype "passive"))
      (node (ref "C20") (pin "2") (pinfunction "2_2") (pintype "passive"))
      (node (ref "C21") (pin "1") (pinfunction "1_1") (pintype "passive"))
      (node (ref "C22") (pin "1") (pinfunction "1_1") (pintype "passive"))
      (node (ref "C23") (pin "1") (pinfunction "1_1") (pintype "passive"))
      (node (ref "C24") (pin "1") (pinfunction "1_1") (pintype "passive"))
      (node (ref "C25") (pin "1") (pinfunction "1_1") (pintype "passive"))
      (node (ref "C26") (pin "2") (pinfunction "2_2") (pintype "passive"))
      (node (ref "C27") (pin "2") (pinfunction "2_2") (pintype "passive"))
      (node (ref "C28") (pin "2") (pinfunction "2_2") (pintype "passive"))
      (node (ref "C29") (pin "2") (pinfunction "2_2") (pintype "passive"))
      (node (ref "C3") (pin "2") (pinfunction "2_2") (pintype "passive"))
      (node (ref "C30") (pin "2") (pinfunction "2_2") (pintype "passive"))
      (node (ref "C31") (pin "2") (pinfunction "2_2") (pintype "passive"))
      (node (ref "C32") (pin "2") (pinfunction "2_2") (pintype "passive"))
      (node (ref "C33") (pin "2") (pinfunction "2_2") (pintype "passive"))
      (node (ref "C34") (pin "1") (pinfunction "1_1") (pintype "passive"))
      (node (ref "C35") (pin "2") (pinfunction "2_2") (pintype "passive"))
      (node (ref "C36") (pin "2") (pinfunction "2_2") (pintype "passive"))
      (node (ref "C37") (pin "2") (pinfunction "2_2") (pintype "passive"))
      (node (ref "C38") (pin "2") (pinfunction "2_2") (pintype "passive"))
      (node (ref "C39") (pin "2") (pinfunction "2_2") (pintype "passive"))
      (node (ref "C4") (pin "1") (pinfunction "1_1") (pintype "passive"))
      (node (ref "C40") (pin "1") (pinfunction "1_1") (pintype "passive"))
      (node (ref "C41") (pin "2") (pinfunction "2_2") (pintype "passive"))
      (node (ref "C42") (pin "2") (pinfunction "2_2") (pintype "passive"))
      (node (ref "C43") (pin "2") (pinfunction "2_2") (pintype "passive"))
      (node (ref "C44") (pin "2") (pinfunction "2_2") (pintype "passive"))
      (node (ref "C45") (pin "2") (pinfunction "2_2") (pintype "passive"))
      (node (ref "C47") (pin "2") (pinfunction "2_2") (pintype "passive"))
      (node (ref "C48") (pin "1") (pinfunction "1_1") (pintype "passive"))
      (node (ref "C49") (pin "2") (pinfunction "2_2") (pintype "passive"))
      (node (ref "C5") (pin "2") (pinfunction "2_2") (pintype "passive"))
      (node (ref "C50") (pin "2") (pinfunction "2_2") (pintype "passive"))
      (node (ref "C52") (pin "2") (pinfunction "2_2") (pintype "passive"))
      (node (ref "C53") (pin "1") (pinfunction "1_1") (pintype "passive"))
      (node (ref "C54") (pin "2") (pinfunction "2_2") (pintype "passive"))
      (node (ref "C55") (pin "2") (pinfunction "2_2") (pintype "passive"))
      (node (ref "C57") (pin "2") (pinfunction "2_2") (pintype "passive"))
      (node (ref "C58") (pin "1") (pinfunction "1_1") (pintype "passive"))
      (node (ref "C59") (pin "2") (pinfunction "2_2") (pintype "passive"))
      (node (ref "C6") (pin "1") (pinfunction "1_1") (pintype "passive"))
      (node (ref "C60") (pin "2") (pinfunction "2_2") (pintype "passive"))
      (node (ref "C62") (pin "2") (pinfunction "2_2") (pintype "passive"))
      (node (ref "C63") (pin "1") (pinfunction "1_1") (pintype "passive"))
      (node (ref "C64") (pin "2") (pinfunction "2_2") (pintype "passive"))
      (node (ref "C65") (pin "2") (pinfunction "2_2") (pintype "passive"))
      (node (ref "C67") (pin "2") (pinfunction "2_2") (pintype "passive"))
      (node (ref "C68") (pin "1") (pinfunction "1_1") (pintype "passive"))
      (node (ref "C69") (pin "2") (pinfunction "2_2") (pintype "passive"))
      (node (ref "C7") (pin "2") (pinfunction "2_2") (pintype "passive"))
      (node (ref "C70") (pin "2") (pinfunction "2_2") (pintype "passive"))
      (node (ref "C72") (pin "2") (pinfunction "2_2") (pintype "passive"))
      (node (ref "C73") (pin "1") (pinfunction "1_1") (pintype "passive"))
      (node (ref "C74") (pin "2") (pinfunction "2_2") (pintype "passive"))
      (node (ref "C75") (pin "2") (pinfunction "2_2") (pintype "passive"))
      (node (ref "C77") (pin "2") (pinfunction "2_2") (pintype "passive"))
      (node (ref "C78") (pin "1") (pinfunction "1_1") (pintype "passive"))
      (node (ref "C79") (pin "2") (pinfunction "2_2") (pintype "passive"))
      (node (ref "C8") (pin "2") (pinfunction "2_2") (pintype "passive"))
      (node (ref "C80") (pin "2") (pinfunction "2_2") (pintype "passive"))
      (node (ref "C82") (pin "2") (pinfunction "2_2") (pintype "passive"))
      (node (ref "C83") (pin "1") (pinfunction "1_1") (pintype "passive"))
      (node (ref "C84") (pin "2") (pinfunction "2_2") (pintype "passive"))
      (node (ref "C85") (pin "2") (pinfunction "2_2") (pintype "passive"))
      (node (ref "C87") (pin "2") (pinfunction "2_2") (pintype "passive"))
      (node (ref "C88") (pin "1") (pinfunction "1_1") (pintype "passive"))
      (node (ref "C89") (pin "2") (pinfunction "2_2") (pintype "passive"))
      (node (ref "C9") (pin "2") (pinfunction "2_2") (pintype "passive"))
      (node (ref "C90") (pin "2") (pinfunction "2_2") (pintype "passive"))
      (node (ref "C92") (pin "2") (pinfunction "2_2") (pintype "passive"))
      (node (ref "C93") (pin "1") (pinfunction "1_1") (pintype "passive"))
      (node (ref "C94") (pin "2") (pinfunction "2_2") (pintype "passive"))
      (node (ref "C95") (pin "2") (pinfunction "2_2") (pintype "passive"))
      (node (ref "C97") (pin "2") (pinfunction "2_2") (pintype "passive"))
      (node (ref "C98") (pin "1") (pinfunction "1_1") (pintype "passive"))
      (node (ref "C99") (pin "2") (pinfunction "2_2") (pintype "passive"))
      (node (ref "CON28") (pin "2") (pinfunction "2_2") (pintype "passive"))
      (node (ref "CON29") (pin "2") (pinfunction "2_2") (pintype "passive"))
      (node (ref "CON3") (pin "2") (pinfunction "2_2") (pintype "passive"))
      (node (ref "CON30") (pin "2") (pinfunction "2_2") (pintype "passive"))
      (node (ref "CON31") (pin "2") (pinfunction "2_2") (pintype "passive"))
      (node (ref "CON33") (pin "2") (pinfunction "2_2") (pintype "passive"))
      (node (ref "CON34") (pin "2") (pinfunction "2_2") (pintype "passive"))
      (node (ref "CON4") (pin "2") (pinfunction "2_2") (pintype "passive"))
      (node (ref "CON5") (pin "2") (pinfunction "2_2") (pintype "passive"))
      (node (ref "CON7") (pin "11") (pinfunction "VSS_11") (pintype "bidirectional"))
      (node (ref "CON7") (pin "12") (pinfunction "VSS_12") (pintype "bidirectional"))
      (node (ref "CON7") (pin "13") (pinfunction "VSS_13") (pintype "bidirectional"))
      (node (ref "CON7") (pin "14") (pinfunction "VSS_14") (pintype "bidirectional"))
      (node (ref "CON7") (pin "6") (pinfunction "VSS_6") (pintype "bidirectional"))
      (node (ref "CON7") (pin "9") (pinfunction "DETECT_LEVER_9") (pintype "bidirectional"))
      (node (ref "D1") (pin "A") (pinfunction "A_A") (pintype "passive"))
      (node (ref "D2") (pin "1") (pinfunction "A1_1") (pintype "passive"))
      (node (ref "D3") (pin "1") (pinfunction "A1_1") (pintype "passive"))
      (node (ref "IC1") (pin "11") (pinfunction "GND_11") (pintype "power_in"))
      (node (ref "IC1") (pin "32") (pinfunction "GND1_32") (pintype "power_in"))
      (node (ref "IC1") (pin "62") (pinfunction "GND2_62") (pintype "power_in"))
      (node (ref "IC1") (pin "81") (pinfunction "GND3_81") (pintype "power_in"))
      (node (ref "IC1") (pin "99") (pinfunction "AGND_99") (pintype "power_in"))
      (node (ref "IC2") (pin "23") (pinfunction "GND_23") (pintype "bidirectional"))
      (node (ref "IC2") (pin "24") (pinfunction "VSS_24") (pintype "bidirectional"))
      (node (ref "IC3") (pin "3") (pinfunction "GND_3") (pintype "bidirectional"))
      (node (ref "INA1") (pin "1") (pinfunction "A1_1") (pintype "bidirectional"))
      (node (ref "INA1") (pin "2") (pinfunction "A0_2") (pintype "bidirectional"))
      (node (ref "INA1") (pin "7") (pinfunction "GND_7") (pintype "bidirectional"))
      (node (ref "INA2") (pin "2") (pinfunction "A0_2") (pintype "bidirectional"))
      (node (ref "INA2") (pin "7") (pinfunction "GND_7") (pintype "bidirectional"))
      (node (ref "JP1") (pin "6") (pinfunction "6_6") (pintype "passive"))
      (node (ref "JP4") (pin "1") (pinfunction "1_1") (pintype "passive"))
      (node (ref "JP4") (pin "2") (pinfunction "2_2") (pintype "passive"))
      (node (ref "JP5") (pin "1") (pinfunction "1_1") (pintype "passive"))
      (node (ref "JP5") (pin "2") (pinfunction "2_2") (pintype "passive"))
      (node (ref "JTAG1") (pin "10") (pinfunction "GND_10") (pintype "bidirectional"))
      (node (ref "JTAG1") (pin "2") (pinfunction "GND_2") (pintype "bidirectional"))
      (node (ref "LCD1") (pin "1") (pinfunction "VSS_1") (pintype "power_in"))
      (node (ref "LCD1") (pin "16") (pinfunction "K_16") (pintype "power_in"))
      (node (ref "LED1") (pin "C") (pinfunction "C_C") (pintype "passive"))
      (node (ref "LED2") (pin "C") (pinfunction "C_C") (pintype "passive"))
      (node (ref "LED3") (pin "C") (pinfunction "C_C") (pintype "passive"))
      (node (ref "LED_SD") (pin "C") (pinfunction "C_C") (pintype "passive"))
      (node (ref "MAX1") (pin "1") (pinfunction "AGND_1") (pintype "passive"))
      (node (ref "MAX1") (pin "14") (pinfunction "DGND_14") (pintype "passive"))
      (node (ref "MAX10") (pin "1") (pinfunction "AGND_1") (pintype "passive"))
      (node (ref "MAX10") (pin "14") (pinfunction "DGND_14") (pintype "passive"))
      (node (ref "MAX11") (pin "1") (pinfunction "AGND_1") (pintype "passive"))
      (node (ref "MAX11") (pin "14") (pinfunction "DGND_14") (pintype "passive"))
      (node (ref "MAX12") (pin "1") (pinfunction "AGND_1") (pintype "passive"))
      (node (ref "MAX12") (pin "14") (pinfunction "DGND_14") (pintype "passive"))
      (node (ref "MAX13") (pin "1") (pinfunction "AGND_1") (pintype "passive"))
      (node (ref "MAX13") (pin "14") (pinfunction "DGND_14") (pintype "passive"))
      (node (ref "MAX14") (pin "1") (pinfunction "AGND_1") (pintype "passive"))
      (node (ref "MAX14") (pin "14") (pinfunction "DGND_14") (pintype "passive"))
      (node (ref "MAX15") (pin "1") (pinfunction "AGND_1") (pintype "passive"))
      (node (ref "MAX15") (pin "14") (pinfunction "DGND_14") (pintype "passive"))
      (node (ref "MAX16") (pin "1") (pinfunction "AGND_1") (pintype "passive"))
      (node (ref "MAX16") (pin "14") (pinfunction "DGND_14") (pintype "passive"))
      (node (ref "MAX17") (pin "1") (pinfunction "AGND_1") (pintype "passive"))
      (node (ref "MAX17") (pin "14") (pinfunction "DGND_14") (pintype "passive"))
      (node (ref "MAX18") (pin "1") (pinfunction "AGND_1") (pintype "passive"))
      (node (ref "MAX18") (pin "14") (pinfunction "DGND_14") (pintype "passive"))
      (node (ref "MAX19") (pin "1") (pinfunction "AGND_1") (pintype "passive"))
      (node (ref "MAX19") (pin "14") (pinfunction "DGND_14") (pintype "passive"))
      (node (ref "MAX2") (pin "1") (pinfunction "AGND_1") (pintype "passive"))
      (node (ref "MAX2") (pin "14") (pinfunction "DGND_14") (pintype "passive"))
      (node (ref "MAX20") (pin "1") (pinfunction "AGND_1") (pintype "passive"))
      (node (ref "MAX20") (pin "14") (pinfunction "DGND_14") (pintype "passive"))
      (node (ref "MAX3") (pin "1") (pinfunction "AGND_1") (pintype "passive"))
      (node (ref "MAX3") (pin "14") (pinfunction "DGND_14") (pintype "passive"))
      (node (ref "MAX4") (pin "1") (pinfunction "AGND_1") (pintype "passive"))
      (node (ref "MAX4") (pin "14") (pinfunction "DGND_14") (pintype "passive"))
      (node (ref "MAX5") (pin "1") (pinfunction "AGND_1") (pintype "passive"))
      (node (ref "MAX5") (pin "14") (pinfunction "DGND_14") (pintype "passive"))
      (node (ref "MAX6") (pin "1") (pinfunction "AGND_1") (pintype "passive"))
      (node (ref "MAX6") (pin "14") (pinfunction "DGND_14") (pintype "passive"))
      (node (ref "MAX7") (pin "1") (pinfunction "AGND_1") (pintype "passive"))
      (node (ref "MAX7") (pin "14") (pinfunction "DGND_14") (pintype "passive"))
      (node (ref "MAX8") (pin "1") (pinfunction "AGND_1") (pintype "passive"))
      (node (ref "MAX8") (pin "14") (pinfunction "DGND_14") (pintype "passive"))
      (node (ref "MAX9") (pin "1") (pinfunction "AGND_1") (pintype "passive"))
      (node (ref "MAX9") (pin "14") (pinfunction "DGND_14") (pintype "passive"))
      (node (ref "POT1") (pin "1") (pinfunction "E_1") (pintype "passive"))
      (node (ref "R6") (pin "1") (pinfunction "1_1") (pintype "passive"))
      (node (ref "R8") (pin "1") (pinfunction "1_1") (pintype "passive"))
      (node (ref "RTC1") (pin "5") (pinfunction "GND_5") (pintype "bidirectional"))
      (node (ref "SERIAL") (pin "1") (pinfunction "1_1") (pintype "passive"))
      (node (ref "TVS1") (pin "3") (pinfunction "A12_3") (pintype "bidirectional"))
      (node (ref "U1") (pin "1") (pinfunction "~{1OE}_1") (pintype "bidirectional"))
      (node (ref "U1") (pin "10") (pinfunction "GND_10") (pintype "power_in"))
      (node (ref "U1") (pin "17") (pinfunction "2A0_17") (pintype "input"))
      (node (ref "U1") (pin "19") (pinfunction "~{2OE}_19") (pintype "bidirectional"))
      (node (ref "U2") (pin "2") (pinfunction "GND_2") (pintype "bidirectional"))
      (node (ref "U2") (pin "3") (pinfunction "I1_3") (pintype "input"))
      (node (ref "U3") (pin "2") (pinfunction "GND_2") (pintype "bidirectional"))
      (node (ref "U5") (pin "2") (pinfunction "GND_2") (pintype "bidirectional"))
      (node (ref "VR2") (pin "3") (pinfunction "GND_3") (pintype "input"))
      (node (ref "VR3") (pin "1") (pinfunction "GND_1") (pintype "input"))
      (node (ref "VR4") (pin "4") (pinfunction "GND_4") (pintype "power_in"))
      (node (ref "VREF_ON") (pin "C") (pinfunction "C_C") (pintype "passive"))
      (node (ref "Y1") (pin "2") (pinfunction "GND_2") (pintype "passive"))
    )
    (net (code "42") (name "LED2") (class "Default")
      (node (ref "IC1") (pin "69") (pinfunction "PJ6(PCINT15)_69") (pintype "bidirectional"))
      (node (ref "R27") (pin "2") (pinfunction "2_2") (pintype "passive"))
    )
    (net (code "43") (name "LED3") (class "Default")
      (node (ref "IC1") (pin "68") (pinfunction "PJ5(PCINT14)_68") (pintype "bidirectional"))
      (node (ref "R28") (pin "2") (pinfunction "2_2") (pintype "passive"))
    )
    (net (code "44") (name "LED_SD") (class "Default")
      (node (ref "IC1") (pin "42") (pinfunction "PL7_42") (pintype "bidirectional"))
      (node (ref "R31") (pin "2") (pinfunction "2_2") (pintype "passive"))
    )
    (net (code "45") (name "MES_5V3") (class "Default")
      (node (ref "C137") (pin "1") (pinfunction "1_1") (pintype "passive"))
      (node (ref "CON34") (pin "1") (pinfunction "1_1") (pintype "passive"))
      (node (ref "D3") (pin "3") (pinfunction "C1A2_3") (pintype "passive"))
      (node (ref "IC1") (pin "94") (pinfunction "(ADC3)PF3_94") (pintype "bidirectional"))
    )
    (net (code "46") (name "MES_5V4") (class "Default")
      (node (ref "C136") (pin "1") (pinfunction "1_1") (pintype "passive"))
      (node (ref "CON33") (pin "1") (pinfunction "1_1") (pintype "passive"))
      (node (ref "D2") (pin "3") (pinfunction "C1A2_3") (pintype "passive"))
      (node (ref "IC1") (pin "95") (pinfunction "(ADC2)PF2_95") (pintype "bidirectional"))
    )
    (net (code "47") (name "MES_24V1") (class "Default")
      (node (ref "C9") (pin "1") (pinfunction "1_1") (pintype "passive"))
      (node (ref "IC1") (pin "84") (pinfunction "PK5(ADC13/PCINT21)_84") (pintype "bidirectional"))
      (node (ref "R1") (pin "1") (pinfunction "1_1") (pintype "passive"))
      (node (ref "R6") (pin "2") (pinfunction "2_2") (pintype "passive"))
    )
    (net (code "48") (name "MES_24V2") (class "Default")
      (node (ref "C10") (pin "1") (pinfunction "1_1") (pintype "passive"))
      (node (ref "IC1") (pin "83") (pinfunction "PK6(ADC14/PCINT22)_83") (pintype "bidirectional"))
      (node (ref "R7") (pin "1") (pinfunction "1_1") (pintype "passive"))
      (node (ref "R8") (pin "2") (pinfunction "2_2") (pintype "passive"))
    )
    (net (code "49") (name "MISO_3V3") (class "Default")
      (node (ref "CON7") (pin "7") (pinfunction "DAT0_7") (pintype "bidirectional"))
      (node (ref "IC3") (pin "2") (pinfunction "DIN_2") (pintype "input"))
      (node (ref "MAX1") (pin "11") (pinfunction "SDO_11") (pintype "passive"))
      (node (ref "MAX10") (pin "11") (pinfunction "SDO_11") (pintype "passive"))
      (node (ref "MAX11") (pin "11") (pinfunction "SDO_11") (pintype "passive"))
      (node (ref "MAX12") (pin "11") (pinfunction "SDO_11") (pintype "passive"))
      (node (ref "MAX13") (pin "11") (pinfunction "SDO_11") (pintype "passive"))
      (node (ref "MAX14") (pin "11") (pinfunction "SDO_11") (pintype "passive"))
      (node (ref "MAX15") (pin "11") (pinfunction "SDO_11") (pintype "passive"))
      (node (ref "MAX16") (pin "11") (pinfunction "SDO_11") (pintype "passive"))
      (node (ref "MAX17") (pin "11") (pinfunction "SDO_11") (pintype "passive"))
      (node (ref "MAX18") (pin "11") (pinfunction "SDO_11") (pintype "passive"))
      (node (ref "MAX19") (pin "11") (pinfunction "SDO_11") (pintype "passive"))
      (node (ref "MAX2") (pin "11") (pinfunction "SDO_11") (pintype "passive"))
      (node (ref "MAX20") (pin "11") (pinfunction "SDO_11") (pintype "passive"))
      (node (ref "MAX3") (pin "11") (pinfunction "SDO_11") (pintype "passive"))
      (node (ref "MAX4") (pin "11") (pinfunction "SDO_11") (pintype "passive"))
      (node (ref "MAX5") (pin "11") (pinfunction "SDO_11") (pintype "passive"))
      (node (ref "MAX6") (pin "11") (pinfunction "SDO_11") (pintype "passive"))
      (node (ref "MAX7") (pin "11") (pinfunction "SDO_11") (pintype "passive"))
      (node (ref "MAX8") (pin "11") (pinfunction "SDO_11") (pintype "passive"))
      (node (ref "MAX9") (pin "11") (pinfunction "SDO_11") (pintype "passive"))
      (node (ref "R93") (pin "2") (pinfunction "2_2") (pintype "passive"))
    )
    (net (code "50") (name "MISO_5V") (class "Default")
      (node (ref "IC1") (pin "22") (pinfunction "(MISO/PCINT3)PB3_22") (pintype "bidirectional"))
      (node (ref "IC3") (pin "4") (pinfunction "OUT_4") (pintype "output"))
      (node (ref "JP1") (pin "1") (pinfunction "1_1") (pintype "passive"))
    )
    (net (code "51") (name "MOSI_3V3") (class "Default")
      (node (ref "CON7") (pin "3") (pinfunction "CMD_3") (pintype "bidirectional"))
      (node (ref "MAX1") (pin "12") (pinfunction "SDI_12") (pintype "passive"))
      (node (ref "MAX10") (pin "12") (pinfunction "SDI_12") (pintype "passive"))
      (node (ref "MAX11") (pin "12") (pinfunction "SDI_12") (pintype "passive"))
      (node (ref "MAX12") (pin "12") (pinfunction "SDI_12") (pintype "passive"))
      (node (ref "MAX13") (pin "12") (pinfunction "SDI_12") (pintype "passive"))
      (node (ref "MAX14") (pin "12") (pinfunction "SDI_12") (pintype "passive"))
      (node (ref "MAX15") (pin "12") (pinfunction "SDI_12") (pintype "passive"))
      (node (ref "MAX16") (pin "12") (pinfunction "SDI_12") (pintype "passive"))
      (node (ref "MAX17") (pin "12") (pinfunction "SDI_12") (pintype "passive"))
      (node (ref "MAX18") (pin "12") (pinfunction "SDI_12") (pintype "passive"))
      (node (ref "MAX19") (pin "12") (pinfunction "SDI_12") (pintype "passive"))
      (node (ref "MAX2") (pin "12") (pinfunction "SDI_12") (pintype "passive"))
      (node (ref "MAX20") (pin "12") (pinfunction "SDI_12") (pintype "passive"))
      (node (ref "MAX3") (pin "12") (pinfunction "SDI_12") (pintype "passive"))
      (node (ref "MAX4") (pin "12") (pinfunction "SDI_12") (pintype "passive"))
      (node (ref "MAX5") (pin "12") (pinfunction "SDI_12") (pintype "passive"))
      (node (ref "MAX6") (pin "12") (pinfunction "SDI_12") (pintype "passive"))
      (node (ref "MAX7") (pin "12") (pinfunction "SDI_12") (pintype "passive"))
      (node (ref "MAX8") (pin "12") (pinfunction "SDI_12") (pintype "passive"))
      (node (ref "MAX9") (pin "12") (pinfunction "SDI_12") (pintype "passive"))
      (node (ref "U1") (pin "9") (pinfunction "2Y3_9") (pintype "bidirectional"))
    )
    (net (code "52") (name "MOSI_5V") (class "Default")
      (node (ref "IC1") (pin "21") (pinfunction "(MOSI/PCINT2)PB2_21") (pintype "bidirectional"))
      (node (ref "JP1") (pin "4") (pinfunction "4_4") (pintype "passive"))
      (node (ref "R38") (pin "2") (pinfunction "2_2") (pintype "passive"))
      (node (ref "U1") (pin "11") (pinfunction "2A3_11") (pintype "bidirectional"))
    )
    (net (code "53") (name "MUX0") (class "Default")
      (node (ref "IC1") (pin "5") (pinfunction "(OC3A/AIN1)PE3_5") (pintype "bidirectional"))
      (node (ref "U1") (pin "2") (pinfunction "1A0_2") (pintype "bidirectional"))
    )
    (net (code "54") (name "MUX0_3V3") (class "Default")
      (node (ref "IC2") (pin "15") (pinfunction "A0_15") (pintype "bidirectional"))
      (node (ref "U1") (pin "18") (pinfunction "1Y0_18") (pintype "bidirectional"))
    )
    (net (code "55") (name "MUX1") (class "Default")
      (node (ref "IC1") (pin "6") (pinfunction "(OC3B/INT4)PE4_6") (pintype "bidirectional"))
      (node (ref "U1") (pin "4") (pinfunction "1A1_4") (pintype "bidirectional"))
    )
    (net (code "56") (name "MUX1_3V3") (class "Default")
      (node (ref "IC2") (pin "16") (pinfunction "A1_16") (pintype "bidirectional"))
      (node (ref "U1") (pin "16") (pinfunction "1Y1_16") (pintype "bidirectional"))
    )
    (net (code "57") (name "MUX2") (class "Default")
      (node (ref "IC1") (pin "7") (pinfunction "(OC3C/INT5)PE5_7") (pintype "bidirectional"))
      (node (ref "U1") (pin "6") (pinfunction "1A2_6") (pintype "bidirectional"))
    )
    (net (code "58") (name "MUX2_3V3") (class "Default")
      (node (ref "IC2") (pin "17") (pinfunction "A2_17") (pintype "bidirectional"))
      (node (ref "U1") (pin "14") (pinfunction "1Y2_14") (pintype "bidirectional"))
    )
    (net (code "59") (name "MUX3") (class "Default")
      (node (ref "IC1") (pin "8") (pinfunction "(T3/INT6)PE6_8") (pintype "bidirectional"))
      (node (ref "U1") (pin "8") (pinfunction "1A3_8") (pintype "bidirectional"))
    )
    (net (code "60") (name "MUX3_3V3") (class "Default")
      (node (ref "IC2") (pin "18") (pinfunction "A3_18") (pintype "bidirectional"))
      (node (ref "U1") (pin "12") (pinfunction "1Y3_12") (pintype "bidirectional"))
    )
    (net (code "61") (name "MUX4") (class "Default")
      (node (ref "IC1") (pin "9") (pinfunction "(CLKO/ICP3/INT7)PE7_9") (pintype "bidirectional"))
      (node (ref "U5") (pin "1") (pinfunction "I_1") (pintype "input"))
    )
    (net (code "62") (name "MUX4_3V3") (class "Default")
      (node (ref "IC2") (pin "19") (pinfunction "A4_19") (pintype "bidirectional"))
      (node (ref "U5") (pin "6") (pinfunction "O_6") (pintype "output"))
    )
    (net (code "63") (name "Net-(B1-PadAC2)") (class "Default")
      (node (ref "B1") (pin "AC2") (pinfunction "AC2_AC2") (pintype "passive"))
      (node (ref "C138") (pin "2") (pinfunction "2_2") (pintype "passive"))
      (node (ref "CON6") (pin "2") (pinfunction "2_2") (pintype "passive"))
      (node (ref "CON6") (pin "3") (pinfunction "3_3") (pintype "passive"))
    )
    (net (code "64") (name "Net-(B_BACK-3)") (class "Default")
      (node (ref "B_BACK") (pin "2") (pinfunction "3_2") (pintype "passive"))
      (node (ref "B_BACK") (pin "4") (pinfunction "4_4") (pintype "passive"))
      (node (ref "R91") (pin "1") (pinfunction "1_1") (pintype "passive"))
      (node (ref "R92") (pin "1") (pinfunction "1_1") (pintype "passive"))
    )
    (net (code "65") (name "Net-(B_DOWN-3)") (class "Default")
      (node (ref "B_DOWN") (pin "2") (pinfunction "3_2") (pintype "passive"))
      (node (ref "B_DOWN") (pin "4") (pinfunction "4_4") (pintype "passive"))
      (node (ref "R16") (pin "1") (pinfunction "1_1") (pintype "passive"))
      (node (ref "R17") (pin "1") (pinfunction "1_1") (pintype "passive"))
    )
    (net (code "66") (name "Net-(B_LEFT-3)") (class "Default")
      (node (ref "B_LEFT") (pin "2") (pinfunction "3_2") (pintype "passive"))
      (node (ref "B_LEFT") (pin "4") (pinfunction "4_4") (pintype "passive"))
      (node (ref "R14") (pin "1") (pinfunction "1_1") (pintype "passive"))
      (node (ref "R15") (pin "1") (pinfunction "1_1") (pintype "passive"))
    )
    (net (code "67") (name "Net-(B_OK-3)") (class "Default")
      (node (ref "B_OK") (pin "2") (pinfunction "3_2") (pintype "passive"))
      (node (ref "B_OK") (pin "4") (pinfunction "4_4") (pintype "passive"))
      (node (ref "R22") (pin "1") (pinfunction "1_1") (pintype "passive"))
      (node (ref "R23") (pin "1") (pinfunction "1_1") (pintype "passive"))
    )
    (net (code "68") (name "Net-(B_RESET-3)") (class "Default")
      (node (ref "B_RESET") (pin "2") (pinfunction "3_2") (pintype "passive"))
      (node (ref "B_RESET") (pin "4") (pinfunction "4_4") (pintype "passive"))
      (node (ref "R12") (pin "1") (pinfunction "1_1") (pintype "passive"))
      (node (ref "R13") (pin "1") (pinfunction "1_1") (pintype "passive"))
    )
    (net (code "69") (name "Net-(B_RIGHT-3)") (class "Default")
      (node (ref "B_RIGHT") (pin "2") (pinfunction "3_2") (pintype "passive"))
      (node (ref "B_RIGHT") (pin "4") (pinfunction "4_4") (pintype "passive"))
      (node (ref "R18") (pin "1") (pinfunction "1_1") (pintype "passive"))
      (node (ref "R19") (pin "1") (pinfunction "1_1") (pintype "passive"))
    )
    (net (code "70") (name "Net-(B_UP-3)") (class "Default")
      (node (ref "B_UP") (pin "2") (pinfunction "3_2") (pintype "passive"))
      (node (ref "B_UP") (pin "4") (pinfunction "4_4") (pintype "passive"))
      (node (ref "R20") (pin "1") (pinfunction "1_1") (pintype "passive"))
      (node (ref "R21") (pin "1") (pinfunction "1_1") (pintype "passive"))
    )
    (net (code "71") (name "Net-(CON1-1A1-PadA1)") (class "Default")
      (node (ref "CON1") (pin "A1") (pinfunction "1A1_A1") (pintype "passive"))
      (node (ref "CON1") (pin "B1") (pinfunction "1A1_B1") (pintype "passive"))
      (node (ref "R4") (pin "1") (pinfunction "1_1") (pintype "passive"))
    )
    (net (code "72") (name "Net-(CON2-Pad1)") (class "Default")
      (node (ref "CON2") (pin "1") (pinfunction "1_1") (pintype "passive"))
      (node (ref "JP3") (pin "1") (pinfunction "1_1") (pintype "passive"))
      (node (ref "R34") (pin "1") (pinfunction "1_1") (pintype "passive"))
    )
    (net (code "73") (name "Net-(CON2-Pad2)") (class "Default")
      (node (ref "CON2") (pin "2") (pinfunction "2_2") (pintype "passive"))
      (node (ref "JP2") (pin "3") (pinfunction "3_3") (pintype "passive"))
      (node (ref "R34") (pin "2") (pinfunction "2_2") (pintype "passive"))
    )
    (net (code "74") (name "Net-(CON3-Pad1)") (class "Default")
      (node (ref "CON3") (pin "1") (pinfunction "1_1") (pintype "passive"))
      (node (ref "R10") (pin "1") (pinfunction "1_1") (pintype "passive"))
      (node (ref "R9") (pin "1") (pinfunction "1_1") (pintype "passive"))
    )
    (net (code "75") (name "Net-(CON4-Pad1)") (class "Default")
      (node (ref "CON4") (pin "1") (pinfunction "1_1") (pintype "passive"))
      (node (ref "F1") (pin "1") (pinfunction "1_1") (pintype "passive"))
    )
    (net (code "76") (name "Net-(CON5-Pad1)") (class "Default")
      (node (ref "CON5") (pin "1") (pinfunction "1_1") (pintype "passive"))
      (node (ref "F2") (pin "1") (pinfunction "1_1") (pintype "passive"))
    )
    (net (code "77") (name "Net-(CON7-DAT1)") (class "Default")
      (node (ref "CON7") (pin "8") (pinfunction "DAT1_8") (pintype "bidirectional"))
      (node (ref "R36") (pin "2") (pinfunction "2_2") (pintype "passive"))
    )
    (net (code "78") (name "Net-(CON7-DAT2)") (class "Default")
      (node (ref "CON7") (pin "1") (pinfunction "DAT2_1") (pintype "bidirectional"))
      (node (ref "R37") (pin "2") (pinfunction "2_2") (pintype "passive"))
    )
    (net (code "79") (name "Net-(CON9-1A1-PadA1)") (class "Default")
      (node (ref "CON9") (pin "A1") (pinfunction "1A1_A1") (pintype "passive"))
      (node (ref "CON9") (pin "B1") (pinfunction "1A1_B1") (pintype "passive"))
      (node (ref "R11") (pin "1") (pinfunction "1_1") (pintype "passive"))
    )
    (net (code "80") (name "Net-(CON10-1A1-PadA1)") (class "Default")
      (node (ref "CON10") (pin "A1") (pinfunction "1A1_A1") (pintype "passive"))
      (node (ref "CON10") (pin "B1") (pinfunction "1A1_B1") (pintype "passive"))
      (node (ref "R26") (pin "1") (pinfunction "1_1") (pintype "passive"))
    )
    (net (code "81") (name "Net-(CON11-1A1-PadA1)") (class "Default")
      (node (ref "CON11") (pin "A1") (pinfunction "1A1_A1") (pintype "passive"))
      (node (ref "CON11") (pin "B1") (pinfunction "1A1_B1") (pintype "passive"))
      (node (ref "R32") (pin "1") (pinfunction "1_1") (pintype "passive"))
    )
    (net (code "82") (name "Net-(CON12-1A1-PadA1)") (class "Default")
      (node (ref "CON12") (pin "A1") (pinfunction "1A1_A1") (pintype "passive"))
      (node (ref "CON12") (pin "B1") (pinfunction "1A1_B1") (pintype "passive"))
      (node (ref "R44") (pin "1") (pinfunction "1_1") (pintype "passive"))
    )
    (net (code "83") (name "Net-(CON13-1A1-PadA1)") (class "Default")
      (node (ref "CON13") (pin "A1") (pinfunction "1A1_A1") (pintype "passive"))
      (node (ref "CON13") (pin "B1") (pinfunction "1A1_B1") (pintype "passive"))
      (node (ref "R46") (pin "1") (pinfunction "1_1") (pintype "passive"))
    )
    (net (code "84") (name "Net-(CON14-1A1-PadA1)") (class "Default")
      (node (ref "CON14") (pin "A1") (pinfunction "1A1_A1") (pintype "passive"))
      (node (ref "CON14") (pin "B1") (pinfunction "1A1_B1") (pintype "passive"))
      (node (ref "R48") (pin "1") (pinfunction "1_1") (pintype "passive"))
    )
    (net (code "85") (name "Net-(CON15-1A1-PadA1)") (class "Default")
      (node (ref "CON15") (pin "A1") (pinfunction "1A1_A1") (pintype "passive"))
      (node (ref "CON15") (pin "B1") (pinfunction "1A1_B1") (pintype "passive"))
      (node (ref "R50") (pin "1") (pinfunction "1_1") (pintype "passive"))
    )
    (net (code "86") (name "Net-(CON16-1A1-PadA1)") (class "Default")
      (node (ref "CON16") (pin "A1") (pinfunction "1A1_A1") (pintype "passive"))
      (node (ref "CON16") (pin "B1") (pinfunction "1A1_B1") (pintype "passive"))
      (node (ref "R52") (pin "1") (pinfunction "1_1") (pintype "passive"))
    )
    (net (code "87") (name "Net-(CON17-1A1-PadA1)") (class "Default")
      (node (ref "CON17") (pin "A1") (pinfunction "1A1_A1") (pintype "passive"))
      (node (ref "CON17") (pin "B1") (pinfunction "1A1_B1") (pintype "passive"))
      (node (ref "R54") (pin "1") (pinfunction "1_1") (pintype "passive"))
    )
    (net (code "88") (name "Net-(CON18-1A1-PadA1)") (class "Default")
      (node (ref "CON18") (pin "A1") (pinfunction "1A1_A1") (pintype "passive"))
      (node (ref "CON18") (pin "B1") (pinfunction "1A1_B1") (pintype "passive"))
      (node (ref "R56") (pin "1") (pinfunction "1_1") (pintype "passive"))
    )
    (net (code "89") (name "Net-(CON19-1A1-PadA1)") (class "Default")
      (node (ref "CON19") (pin "A1") (pinfunction "1A1_A1") (pintype "passive"))
      (node (ref "CON19") (pin "B1") (pinfunction "1A1_B1") (pintype "passive"))
      (node (ref "R58") (pin "1") (pinfunction "1_1") (pintype "passive"))
    )
    (net (code "90") (name "Net-(CON20-1A1-PadA1)") (class "Default")
      (node (ref "CON20") (pin "A1") (pinfunction "1A1_A1") (pintype "passive"))
      (node (ref "CON20") (pin "B1") (pinfunction "1A1_B1") (pintype "passive"))
      (node (ref "R60") (pin "1") (pinfunction "1_1") (pintype "passive"))
    )
    (net (code "91") (name "Net-(CON21-1A1-PadA1)") (class "Default")
      (node (ref "CON21") (pin "A1") (pinfunction "1A1_A1") (pintype "passive"))
      (node (ref "CON21") (pin "B1") (pinfunction "1A1_B1") (pintype "passive"))
      (node (ref "R62") (pin "1") (pinfunction "1_1") (pintype "passive"))
    )
    (net (code "92") (name "Net-(CON22-1A1-PadA1)") (class "Default")
      (node (ref "CON22") (pin "A1") (pinfunction "1A1_A1") (pintype "passive"))
      (node (ref "CON22") (pin "B1") (pinfunction "1A1_B1") (pintype "passive"))
      (node (ref "R64") (pin "1") (pinfunction "1_1") (pintype "passive"))
    )
    (net (code "93") (name "Net-(CON23-1A1-PadA1)") (class "Default")
      (node (ref "CON23") (pin "A1") (pinfunction "1A1_A1") (pintype "passive"))
      (node (ref "CON23") (pin "B1") (pinfunction "1A1_B1") (pintype "passive"))
      (node (ref "R66") (pin "1") (pinfunction "1_1") (pintype "passive"))
    )
    (net (code "94") (name "Net-(CON24-1A1-PadA1)") (class "Default")
      (node (ref "CON24") (pin "A1") (pinfunction "1A1_A1") (pintype "passive"))
      (node (ref "CON24") (pin "B1") (pinfunction "1A1_B1") (pintype "passive"))
      (node (ref "R68") (pin "1") (pinfunction "1_1") (pintype "passive"))
    )
    (net (code "95") (name "Net-(CON25-1A1-PadA1)") (class "Default")
      (node (ref "CON25") (pin "A1") (pinfunction "1A1_A1") (pintype "passive"))
      (node (ref "CON25") (pin "B1") (pinfunction "1A1_B1") (pintype "passive"))
      (node (ref "R70") (pin "1") (pinfunction "1_1") (pintype "passive"))
    )
    (net (code "96") (name "Net-(CON26-1A1-PadA1)") (class "Default")
      (node (ref "CON26") (pin "A1") (pinfunction "1A1_A1") (pintype "passive"))
      (node (ref "CON26") (pin "B1") (pinfunction "1A1_B1") (pintype "passive"))
      (node (ref "R72") (pin "1") (pinfunction "1_1") (pintype "passive"))
    )
    (net (code "97") (name "Net-(CON27-1A1-PadA1)") (class "Default")
      (node (ref "CON27") (pin "A1") (pinfunction "1A1_A1") (pintype "passive"))
      (node (ref "CON27") (pin "B1") (pinfunction "1A1_B1") (pintype "passive"))
      (node (ref "R74") (pin "1") (pinfunction "1_1") (pintype "passive"))
    )
    (net (code "98") (name "Net-(CON28-Pad1)") (class "Default")
      (node (ref "CON28") (pin "1") (pinfunction "1_1") (pintype "passive"))
      (node (ref "R83") (pin "1") (pinfunction "1_1") (pintype "passive"))
      (node (ref "R84") (pin "1") (pinfunction "1_1") (pintype "passive"))
    )
    (net (code "99") (name "Net-(CON29-Pad1)") (class "Default")
      (node (ref "CON29") (pin "1") (pinfunction "1_1") (pintype "passive"))
      (node (ref "R85") (pin "1") (pinfunction "1_1") (pintype "passive"))
      (node (ref "R86") (pin "1") (pinfunction "1_1") (pintype "passive"))
    )
    (net (code "100") (name "Net-(CON30-Pad1)") (class "Default")
      (node (ref "CON30") (pin "1") (pinfunction "1_1") (pintype "passive"))
      (node (ref "R87") (pin "1") (pinfunction "1_1") (pintype "passive"))
      (node (ref "R88") (pin "1") (pinfunction "1_1") (pintype "passive"))
    )
    (net (code "101") (name "Net-(CON31-Pad1)") (class "Default")
      (node (ref "CON31") (pin "1") (pinfunction "1_1") (pintype "passive"))
      (node (ref "R89") (pin "1") (pinfunction "1_1") (pintype "passive"))
      (node (ref "R90") (pin "1") (pinfunction "1_1") (pintype "passive"))
    )
    (net (code "102") (name "Net-(CON35-Pad1)") (class "Default")
      (node (ref "CON35") (pin "1") (pinfunction "1_1") (pintype "passive"))
      (node (ref "JP3") (pin "3") (pinfunction "3_3") (pintype "passive"))
    )
    (net (code "103") (name "Net-(CON35-Pad2)") (class "Default")
      (node (ref "CON35") (pin "2") (pinfunction "2_2") (pintype "passive"))
      (node (ref "JP2") (pin "1") (pinfunction "1_1") (pintype "passive"))
    )
    (net (code "104") (name "Net-(IC1-XTAL1)") (class "Default")
      (node (ref "IC1") (pin "34") (pinfunction "XTAL1_34") (pintype "input"))
      (node (ref "R35") (pin "1") (pinfunction "1_1") (pintype "passive"))
      (node (ref "Y1") (pin "3") (pinfunction "3_3") (pintype "passive"))
    )
    (net (code "105") (name "Net-(IC1-XTAL2)") (class "Default")
      (node (ref "IC1") (pin "33") (pinfunction "XTAL2_33") (pintype "output"))
      (node (ref "R35") (pin "2") (pinfunction "2_2") (pintype "passive"))
      (node (ref "Y1") (pin "1") (pinfunction "1_1") (pintype "passive"))
    )
    (net (code "106") (name "Net-(LCD1-VO)") (class "Default")
      (node (ref "LCD1") (pin "3") (pinfunction "VO_3") (pintype "input"))
      (node (ref "POT1") (pin "2") (pinfunction "S_2") (pintype "passive"))
    )
    (net (code "107") (name "Net-(LED1-PadA)") (class "Default")
      (node (ref "LED1") (pin "A") (pinfunction "A_A") (pintype "passive"))
      (node (ref "R24") (pin "1") (pinfunction "1_1") (pintype "passive"))
    )
    (net (code "108") (name "Net-(LED2-PadA)") (class "Default")
      (node (ref "LED2") (pin "A") (pinfunction "A_A") (pintype "passive"))
      (node (ref "R27") (pin "1") (pinfunction "1_1") (pintype "passive"))
    )
    (net (code "109") (name "Net-(LED3-PadA)") (class "Default")
      (node (ref "LED3") (pin "A") (pinfunction "A_A") (pintype "passive"))
      (node (ref "R28") (pin "1") (pinfunction "1_1") (pintype "passive"))
    )
    (net (code "110") (name "Net-(LED_SD-PadA)") (class "Default")
      (node (ref "LED_SD") (pin "A") (pinfunction "A_A") (pintype "passive"))
      (node (ref "R31") (pin "1") (pinfunction "1_1") (pintype "passive"))
    )
    (net (code "111") (name "Net-(MAX1-BIAS)") (class "Default")
      (node (ref "CON1") (pin "A") (pinfunction "1A_A") (pintype "passive"))
      (node (ref "CON1") (pin "B") (pinfunction "1A_B") (pintype "passive"))
      (node (ref "MAX1") (pin "2") (pinfunction "BIAS_2") (pintype "passive"))
      (node (ref "R5") (pin "1") (pinfunction "1_1") (pintype "passive"))
    )
    (net (code "112") (name "Net-(MAX1-T+)") (class "Default")
      (node (ref "C1") (pin "2") (pinfunction "2_2") (pintype "passive"))
      (node (ref "C5") (pin "1") (pinfunction "1_1") (pintype "passive"))
      (node (ref "MAX1") (pin "4") (pinfunction "T+_4") (pintype "passive"))
      (node (ref "R4") (pin "2") (pinfunction "2_2") (pintype "passive"))
    )
    (net (code "113") (name "Net-(MAX1-T-)") (class "Default")
      (node (ref "C1") (pin "1") (pinfunction "1_1") (pintype "passive"))
      (node (ref "C6") (pin "2") (pinfunction "2_2") (pintype "passive"))
      (node (ref "MAX1") (pin "3") (pinfunction "T-_3") (pintype "passive"))
      (node (ref "R5") (pin "2") (pinfunction "2_2") (pintype "passive"))
    )
    (net (code "114") (name "Net-(MAX2-BIAS)") (class "Default")
      (node (ref "CON9") (pin "A") (pinfunction "1A_A") (pintype "passive"))
      (node (ref "CON9") (pin "B") (pinfunction "1A_B") (pintype "passive"))
      (node (ref "MAX2") (pin "2") (pinfunction "BIAS_2") (pintype "passive"))
      (node (ref "R25") (pin "1") (pinfunction "1_1") (pintype "passive"))
    )
    (net (code "115") (name "Net-(MAX2-T+)") (class "Default")
      (node (ref "C11") (pin "2") (pinfunction "2_2") (pintype "passive"))
      (node (ref "C12") (pin "1") (pinfunction "1_1") (pintype "passive"))
      (node (ref "MAX2") (pin "4") (pinfunction "T+_4") (pintype "passive"))
      (node (ref "R11") (pin "2") (pinfunction "2_2") (pintype "passive"))
    )
    (net (code "116") (name "Net-(MAX2-T-)") (class "Default")
      (node (ref "C11") (pin "1") (pinfunction "1_1") (pintype "passive"))
      (node (ref "C15") (pin "2") (pinfunction "2_2") (pintype "passive"))
      (node (ref "MAX2") (pin "3") (pinfunction "T-_3") (pintype "passive"))
      (node (ref "R25") (pin "2") (pinfunction "2_2") (pintype "passive"))
    )
    (net (code "117") (name "Net-(MAX3-BIAS)") (class "Default")
      (node (ref "CON10") (pin "A") (pinfunction "1A_A") (pintype "passive"))
      (node (ref "CON10") (pin "B") (pinfunction "1A_B") (pintype "passive"))
      (node (ref "MAX3") (pin "2") (pinfunction "BIAS_2") (pintype "passive"))
      (node (ref "R29") (pin "1") (pinfunction "1_1") (pintype "passive"))
    )
    (net (code "118") (name "Net-(MAX3-T+)") (class "Default")
      (node (ref "C46") (pin "2") (pinfunction "2_2") (pintype "passive"))
      (node (ref "C47") (pin "1") (pinfunction "1_1") (pintype "passive"))
      (node (ref "MAX3") (pin "4") (pinfunction "T+_4") (pintype "passive"))
      (node (ref "R26") (pin "2") (pinfunction "2_2") (pintype "passive"))
    )
    (net (code "119") (name "Net-(MAX3-T-)") (class "Default")
      (node (ref "C46") (pin "1") (pinfunction "1_1") (pintype "passive"))
      (node (ref "C48") (pin "2") (pinfunction "2_2") (pintype "passive"))
      (node (ref "MAX3") (pin "3") (pinfunction "T-_3") (pintype "passive"))
      (node (ref "R29") (pin "2") (pinfunction "2_2") (pintype "passive"))
    )
    (net (code "120") (name "Net-(MAX4-BIAS)") (class "Default")
      (node (ref "CON11") (pin "A") (pinfunction "1A_A") (pintype "passive"))
      (node (ref "CON11") (pin "B") (pinfunction "1A_B") (pintype "passive"))
      (node (ref "MAX4") (pin "2") (pinfunction "BIAS_2") (pintype "passive"))
      (node (ref "R33") (pin "1") (pinfunction "1_1") (pintype "passive"))
    )
    (net (code "121") (name "Net-(MAX4-T+)") (class "Default")
      (node (ref "C51") (pin "2") (pinfunction "2_2") (pintype "passive"))
      (node (ref "C52") (pin "1") (pinfunction "1_1") (pintype "passive"))
      (node (ref "MAX4") (pin "4") (pinfunction "T+_4") (pintype "passive"))
      (node (ref "R32") (pin "2") (pinfunction "2_2") (pintype "passive"))
    )
    (net (code "122") (name "Net-(MAX4-T-)") (class "Default")
      (node (ref "C51") (pin "1") (pinfunction "1_1") (pintype "passive"))
      (node (ref "C53") (pin "2") (pinfunction "2_2") (pintype "passive"))
      (node (ref "MAX4") (pin "3") (pinfunction "T-_3") (pintype "passive"))
      (node (ref "R33") (pin "2") (pinfunction "2_2") (pintype "passive"))
    )
    (net (code "123") (name "Net-(MAX5-BIAS)") (class "Default")
      (node (ref "CON12") (pin "A") (pinfunction "1A_A") (pintype "passive"))
      (node (ref "CON12") (pin "B") (pinfunction "1A_B") (pintype "passive"))
      (node (ref "MAX5") (pin "2") (pinfunction "BIAS_2") (pintype "passive"))
      (node (ref "R45") (pin "1") (pinfunction "1_1") (pintype "passive"))
    )
    (net (code "124") (name "Net-(MAX5-T+)") (class "Default")
      (node (ref "C56") (pin "2") (pinfunction "2_2") (pintype "passive"))
      (node (ref "C57") (pin "1") (pinfunction "1_1") (pintype "passive"))
      (node (ref "MAX5") (pin "4") (pinfunction "T+_4") (pintype "passive"))
      (node (ref "R44") (pin "2") (pinfunction "2_2") (pintype "passive"))
    )
    (net (code "125") (name "Net-(MAX5-T-)") (class "Default")
      (node (ref "C56") (pin "1") (pinfunction "1_1") (pintype "passive"))
      (node (ref "C58") (pin "2") (pinfunction "2_2") (pintype "passive"))
      (node (ref "MAX5") (pin "3") (pinfunction "T-_3") (pintype "passive"))
      (node (ref "R45") (pin "2") (pinfunction "2_2") (pintype "passive"))
    )
    (net (code "126") (name "Net-(MAX6-BIAS)") (class "Default")
      (node (ref "CON13") (pin "A") (pinfunction "1A_A") (pintype "passive"))
      (node (ref "CON13") (pin "B") (pinfunction "1A_B") (pintype "passive"))
      (node (ref "MAX6") (pin "2") (pinfunction "BIAS_2") (pintype "passive"))
      (node (ref "R47") (pin "1") (pinfunction "1_1") (pintype "passive"))
    )
    (net (code "127") (name "Net-(MAX6-T+)") (class "Default")
      (node (ref "C61") (pin "2") (pinfunction "2_2") (pintype "passive"))
      (node (ref "C62") (pin "1") (pinfunction "1_1") (pintype "passive"))
      (node (ref "MAX6") (pin "4") (pinfunction "T+_4") (pintype "passive"))
      (node (ref "R46") (pin "2") (pinfunction "2_2") (pintype "passive"))
    )
    (net (code "128") (name "Net-(MAX6-T-)") (class "Default")
      (node (ref "C61") (pin "1") (pinfunction "1_1") (pintype "passive"))
      (node (ref "C63") (pin "2") (pinfunction "2_2") (pintype "passive"))
      (node (ref "MAX6") (pin "3") (pinfunction "T-_3") (pintype "passive"))
      (node (ref "R47") (pin "2") (pinfunction "2_2") (pintype "passive"))
    )
    (net (code "129") (name "Net-(MAX7-BIAS)") (class "Default")
      (node (ref "CON14") (pin "A") (pinfunction "1A_A") (pintype "passive"))
      (node (ref "CON14") (pin "B") (pinfunction "1A_B") (pintype "passive"))
      (node (ref "MAX7") (pin "2") (pinfunction "BIAS_2") (pintype "passive"))
      (node (ref "R49") (pin "1") (pinfunction "1_1") (pintype "passive"))
    )
    (net (code "130") (name "Net-(MAX7-T+)") (class "Default")
      (node (ref "C66") (pin "2") (pinfunction "2_2") (pintype "passive"))
      (node (ref "C67") (pin "1") (pinfunction "1_1") (pintype "passive"))
      (node (ref "MAX7") (pin "4") (pinfunction "T+_4") (pintype "passive"))
      (node (ref "R48") (pin "2") (pinfunction "2_2") (pintype "passive"))
    )
    (net (code "131") (name "Net-(MAX7-T-)") (class "Default")
      (node (ref "C66") (pin "1") (pinfunction "1_1") (pintype "passive"))
      (node (ref "C68") (pin "2") (pinfunction "2_2") (pintype "passive"))
      (node (ref "MAX7") (pin "3") (pinfunction "T-_3") (pintype "passive"))
      (node (ref "R49") (pin "2") (pinfunction "2_2") (pintype "passive"))
    )
    (net (code "132") (name "Net-(MAX8-BIAS)") (class "Default")
      (node (ref "CON15") (pin "A") (pinfunction "1A_A") (pintype "passive"))
      (node (ref "CON15") (pin "B") (pinfunction "1A_B") (pintype "passive"))
      (node (ref "MAX8") (pin "2") (pinfunction "BIAS_2") (pintype "passive"))
      (node (ref "R51") (pin "1") (pinfunction "1_1") (pintype "passive"))
    )
    (net (code "133") (name "Net-(MAX8-T+)") (class "Default")
      (node (ref "C71") (pin "2") (pinfunction "2_2") (pintype "passive"))
      (node (ref "C72") (pin "1") (pinfunction "1_1") (pintype "passive"))
      (node (ref "MAX8") (pin "4") (pinfunction "T+_4") (pintype "passive"))
      (node (ref "R50") (pin "2") (pinfunction "2_2") (pintype "passive"))
    )
    (net (code "134") (name "Net-(MAX8-T-)") (class "Default")
      (node (ref "C71") (pin "1") (pinfunction "1_1") (pintype "passive"))
      (node (ref "C73") (pin "2") (pinfunction "2_2") (pintype "passive"))
      (node (ref "MAX8") (pin "3") (pinfunction "T-_3") (pintype "passive"))
      (node (ref "R51") (pin "2") (pinfunction "2_2") (pintype "passive"))
    )
    (net (code "135") (name "Net-(MAX9-BIAS)") (class "Default")
      (node (ref "CON16") (pin "A") (pinfunction "1A_A") (pintype "passive"))
      (node (ref "CON16") (pin "B") (pinfunction "1A_B") (pintype "passive"))
      (node (ref "MAX9") (pin "2") (pinfunction "BIAS_2") (pintype "passive"))
      (node (ref "R53") (pin "1") (pinfunction "1_1") (pintype "passive"))
    )
    (net (code "136") (name "Net-(MAX9-T+)") (class "Default")
      (node (ref "C76") (pin "2") (pinfunction "2_2") (pintype "passive"))
      (node (ref "C77") (pin "1") (pinfunction "1_1") (pintype "passive"))
      (node (ref "MAX9") (pin "4") (pinfunction "T+_4") (pintype "passive"))
      (node (ref "R52") (pin "2") (pinfunction "2_2") (pintype "passive"))
    )
    (net (code "137") (name "Net-(MAX9-T-)") (class "Default")
      (node (ref "C76") (pin "1") (pinfunction "1_1") (pintype "passive"))
      (node (ref "C78") (pin "2") (pinfunction "2_2") (pintype "passive"))
      (node (ref "MAX9") (pin "3") (pinfunction "T-_3") (pintype "passive"))
      (node (ref "R53") (pin "2") (pinfunction "2_2") (pintype "passive"))
    )
    (net (code "138") (name "Net-(MAX10-BIAS)") (class "Default")
      (node (ref "CON17") (pin "A") (pinfunction "1A_A") (pintype "passive"))
      (node (ref "CON17") (pin "B") (pinfunction "1A_B") (pintype "passive"))
      (node (ref "MAX10") (pin "2") (pinfunction "BIAS_2") (pintype "passive"))
      (node (ref "R55") (pin "1") (pinfunction "1_1") (pintype "passive"))
    )
    (net (code "139") (name "Net-(MAX10-T+)") (class "Default")
      (node (ref "C81") (pin "2") (pinfunction "2_2") (pintype "passive"))
      (node (ref "C82") (pin "1") (pinfunction "1_1") (pintype "passive"))
      (node (ref "MAX10") (pin "4") (pinfunction "T+_4") (pintype "passive"))
      (node (ref "R54") (pin "2") (pinfunction "2_2") (pintype "passive"))
    )
    (net (code "140") (name "Net-(MAX10-T-)") (class "Default")
      (node (ref "C81") (pin "1") (pinfunction "1_1") (pintype "passive"))
      (node (ref "C83") (pin "2") (pinfunction "2_2") (pintype "passive"))
      (node (ref "MAX10") (pin "3") (pinfunction "T-_3") (pintype "passive"))
      (node (ref "R55") (pin "2") (pinfunction "2_2") (pintype "passive"))
    )
    (net (code "141") (name "Net-(MAX11-BIAS)") (class "Default")
      (node (ref "CON18") (pin "A") (pinfunction "1A_A") (pintype "passive"))
      (node (ref "CON18") (pin "B") (pinfunction "1A_B") (pintype "passive"))
      (node (ref "MAX11") (pin "2") (pinfunction "BIAS_2") (pintype "passive"))
      (node (ref "R57") (pin "1") (pinfunction "1_1") (pintype "passive"))
    )
    (net (code "142") (name "Net-(MAX11-T+)") (class "Default")
      (node (ref "C86") (pin "2") (pinfunction "2_2") (pintype "passive"))
      (node (ref "C87") (pin "1") (pinfunction "1_1") (pintype "passive"))
      (node (ref "MAX11") (pin "4") (pinfunction "T+_4") (pintype "passive"))
      (node (ref "R56") (pin "2") (pinfunction "2_2") (pintype "passive"))
    )
    (net (code "143") (name "Net-(MAX11-T-)") (class "Default")
      (node (ref "C86") (pin "1") (pinfunction "1_1") (pintype "passive"))
      (node (ref "C88") (pin "2") (pinfunction "2_2") (pintype "passive"))
      (node (ref "MAX11") (pin "3") (pinfunction "T-_3") (pintype "passive"))
      (node (ref "R57") (pin "2") (pinfunction "2_2") (pintype "passive"))
    )
    (net (code "144") (name "Net-(MAX12-BIAS)") (class "Default")
      (node (ref "CON19") (pin "A") (pinfunction "1A_A") (pintype "passive"))
      (node (ref "CON19") (pin "B") (pinfunction "1A_B") (pintype "passive"))
      (node (ref "MAX12") (pin "2") (pinfunction "BIAS_2") (pintype "passive"))
      (node (ref "R59") (pin "1") (pinfunction "1_1") (pintype "passive"))
    )
    (net (code "145") (name "Net-(MAX12-T+)") (class "Default")
      (node (ref "C91") (pin "2") (pinfunction "2_2") (pintype "passive"))
      (node (ref "C92") (pin "1") (pinfunction "1_1") (pintype "passive"))
      (node (ref "MAX12") (pin "4") (pinfunction "T+_4") (pintype "passive"))
      (node (ref "R58") (pin "2") (pinfunction "2_2") (pintype "passive"))
    )
    (net (code "146") (name "Net-(MAX12-T-)") (class "Default")
      (node (ref "C91") (pin "1") (pinfunction "1_1") (pintype "passive"))
      (node (ref "C93") (pin "2") (pinfunction "2_2") (pintype "passive"))
      (node (ref "MAX12") (pin "3") (pinfunction "T-_3") (pintype "passive"))
      (node (ref "R59") (pin "2") (pinfunction "2_2") (pintype "passive"))
    )
    (net (code "147") (name "Net-(MAX13-BIAS)") (class "Default")
      (node (ref "CON20") (pin "A") (pinfunction "1A_A") (pintype "passive"))
      (node (ref "CON20") (pin "B") (pinfunction "1A_B") (pintype "passive"))
      (node (ref "MAX13") (pin "2") (pinfunction "BIAS_2") (pintype "passive"))
      (node (ref "R61") (pin "1") (pinfunction "1_1") (pintype "passive"))
    )
    (net (code "148") (name "Net-(MAX13-T+)") (class "Default")
      (node (ref "C96") (pin "2") (pinfunction "2_2") (pintype "passive"))
      (node (ref "C97") (pin "1") (pinfunction "1_1") (pintype "passive"))
      (node (ref "MAX13") (pin "4") (pinfunction "T+_4") (pintype "passive"))
      (node (ref "R60") (pin "2") (pinfunction "2_2") (pintype "passive"))
    )
    (net (code "149") (name "Net-(MAX13-T-)") (class "Default")
      (node (ref "C96") (pin "1") (pinfunction "1_1") (pintype "passive"))
      (node (ref "C98") (pin "2") (pinfunction "2_2") (pintype "passive"))
      (node (ref "MAX13") (pin "3") (pinfunction "T-_3") (pintype "passive"))
      (node (ref "R61") (pin "2") (pinfunction "2_2") (pintype "passive"))
    )
    (net (code "150") (name "Net-(MAX14-BIAS)") (class "Default")
      (node (ref "CON21") (pin "A") (pinfunction "1A_A") (pintype "passive"))
      (node (ref "CON21") (pin "B") (pinfunction "1A_B") (pintype "passive"))
      (node (ref "MAX14") (pin "2") (pinfunction "BIAS_2") (pintype "passive"))
      (node (ref "R63") (pin "1") (pinfunction "1_1") (pintype "passive"))
    )
    (net (code "151") (name "Net-(MAX14-T+)") (class "Default")
      (node (ref "C101") (pin "2") (pinfunction "2_2") (pintype "passive"))
      (node (ref "C102") (pin "1") (pinfunction "1_1") (pintype "passive"))
      (node (ref "MAX14") (pin "4") (pinfunction "T+_4") (pintype "passive"))
      (node (ref "R62") (pin "2") (pinfunction "2_2") (pintype "passive"))
    )
    (net (code "152") (name "Net-(MAX14-T-)") (class "Default")
      (node (ref "C101") (pin "1") (pinfunction "1_1") (pintype "passive"))
      (node (ref "C103") (pin "2") (pinfunction "2_2") (pintype "passive"))
      (node (ref "MAX14") (pin "3") (pinfunction "T-_3") (pintype "passive"))
      (node (ref "R63") (pin "2") (pinfunction "2_2") (pintype "passive"))
    )
    (net (code "153") (name "Net-(MAX15-BIAS)") (class "Default")
      (node (ref "CON22") (pin "A") (pinfunction "1A_A") (pintype "passive"))
      (node (ref "CON22") (pin "B") (pinfunction "1A_B") (pintype "passive"))
      (node (ref "MAX15") (pin "2") (pinfunction "BIAS_2") (pintype "passive"))
      (node (ref "R65") (pin "1") (pinfunction "1_1") (pintype "passive"))
    )
    (net (code "154") (name "Net-(MAX15-T+)") (class "Default")
      (node (ref "C106") (pin "2") (pinfunction "2_2") (pintype "passive"))
      (node (ref "C107") (pin "1") (pinfunction "1_1") (pintype "passive"))
      (node (ref "MAX15") (pin "4") (pinfunction "T+_4") (pintype "passive"))
      (node (ref "R64") (pin "2") (pinfunction "2_2") (pintype "passive"))
    )
    (net (code "155") (name "Net-(MAX15-T-)") (class "Default")
      (node (ref "C106") (pin "1") (pinfunction "1_1") (pintype "passive"))
      (node (ref "C108") (pin "2") (pinfunction "2_2") (pintype "passive"))
      (node (ref "MAX15") (pin "3") (pinfunction "T-_3") (pintype "passive"))
      (node (ref "R65") (pin "2") (pinfunction "2_2") (pintype "passive"))
    )
    (net (code "156") (name "Net-(MAX16-BIAS)") (class "Default")
      (node (ref "CON23") (pin "A") (pinfunction "1A_A") (pintype "passive"))
      (node (ref "CON23") (pin "B") (pinfunction "1A_B") (pintype "passive"))
      (node (ref "MAX16") (pin "2") (pinfunction "BIAS_2") (pintype "passive"))
      (node (ref "R67") (pin "1") (pinfunction "1_1") (pintype "passive"))
    )
    (net (code "157") (name "Net-(MAX16-T+)") (class "Default")
      (node (ref "C111") (pin "2") (pinfunction "2_2") (pintype "passive"))
      (node (ref "C112") (pin "1") (pinfunction "1_1") (pintype "passive"))
      (node (ref "MAX16") (pin "4") (pinfunction "T+_4") (pintype "passive"))
      (node (ref "R66") (pin "2") (pinfunction "2_2") (pintype "passive"))
    )
    (net (code "158") (name "Net-(MAX16-T-)") (class "Default")
      (node (ref "C111") (pin "1") (pinfunction "1_1") (pintype "passive"))
      (node (ref "C113") (pin "2") (pinfunction "2_2") (pintype "passive"))
      (node (ref "MAX16") (pin "3") (pinfunction "T-_3") (pintype "passive"))
      (node (ref "R67") (pin "2") (pinfunction "2_2") (pintype "passive"))
    )
    (net (code "159") (name "Net-(MAX17-BIAS)") (class "Default")
      (node (ref "CON24") (pin "A") (pinfunction "1A_A") (pintype "passive"))
      (node (ref "CON24") (pin "B") (pinfunction "1A_B") (pintype "passive"))
      (node (ref "MAX17") (pin "2") (pinfunction "BIAS_2") (pintype "passive"))
      (node (ref "R69") (pin "1") (pinfunction "1_1") (pintype "passive"))
    )
    (net (code "160") (name "Net-(MAX17-T+)") (class "Default")
      (node (ref "C116") (pin "2") (pinfunction "2_2") (pintype "passive"))
      (node (ref "C117") (pin "1") (pinfunction "1_1") (pintype "passive"))
      (node (ref "MAX17") (pin "4") (pinfunction "T+_4") (pintype "passive"))
      (node (ref "R68") (pin "2") (pinfunction "2_2") (pintype "passive"))
    )
    (net (code "161") (name "Net-(MAX17-T-)") (class "Default")
      (node (ref "C116") (pin "1") (pinfunction "1_1") (pintype "passive"))
      (node (ref "C118") (pin "2") (pinfunction "2_2") (pintype "passive"))
      (node (ref "MAX17") (pin "3") (pinfunction "T-_3") (pintype "passive"))
      (node (ref "R69") (pin "2") (pinfunction "2_2") (pintype "passive"))
    )
    (net (code "162") (name "Net-(MAX18-BIAS)") (class "Default")
      (node (ref "CON25") (pin "A") (pinfunction "1A_A") (pintype "passive"))
      (node (ref "CON25") (pin "B") (pinfunction "1A_B") (pintype "passive"))
      (node (ref "MAX18") (pin "2") (pinfunction "BIAS_2") (pintype "passive"))
      (node (ref "R71") (pin "1") (pinfunction "1_1") (pintype "passive"))
    )
    (net (code "163") (name "Net-(MAX18-T+)") (class "Default")
      (node (ref "C121") (pin "2") (pinfunction "2_2") (pintype "passive"))
      (node (ref "C122") (pin "1") (pinfunction "1_1") (pintype "passive"))
      (node (ref "MAX18") (pin "4") (pinfunction "T+_4") (pintype "passive"))
      (node (ref "R70") (pin "2") (pinfunction "2_2") (pintype "passive"))
    )
    (net (code "164") (name "Net-(MAX18-T-)") (class "Default")
      (node (ref "C121") (pin "1") (pinfunction "1_1") (pintype "passive"))
      (node (ref "C123") (pin "2") (pinfunction "2_2") (pintype "passive"))
      (node (ref "MAX18") (pin "3") (pinfunction "T-_3") (pintype "passive"))
      (node (ref "R71") (pin "2") (pinfunction "2_2") (pintype "passive"))
    )
    (net (code "165") (name "Net-(MAX19-BIAS)") (class "Default")
      (node (ref "CON26") (pin "A") (pinfunction "1A_A") (pintype "passive"))
      (node (ref "CON26") (pin "B") (pinfunction "1A_B") (pintype "passive"))
      (node (ref "MAX19") (pin "2") (pinfunction "BIAS_2") (pintype "passive"))
      (node (ref "R73") (pin "1") (pinfunction "1_1") (pintype "passive"))
    )
    (net (code "166") (name "Net-(MAX19-T+)") (class "Default")
      (node (ref "C126") (pin "2") (pinfunction "2_2") (pintype "passive"))
      (node (ref "C127") (pin "1") (pinfunction "1_1") (pintype "passive"))
      (node (ref "MAX19") (pin "4") (pinfunction "T+_4") (pintype "passive"))
      (node (ref "R72") (pin "2") (pinfunction "2_2") (pintype "passive"))
    )
    (net (code "167") (name "Net-(MAX19-T-)") (class "Default")
      (node (ref "C126") (pin "1") (pinfunction "1_1") (pintype "passive"))
      (node (ref "C128") (pin "2") (pinfunction "2_2") (pintype "passive"))
      (node (ref "MAX19") (pin "3") (pinfunction "T-_3") (pintype "passive"))
      (node (ref "R73") (pin "2") (pinfunction "2_2") (pintype "passive"))
    )
    (net (code "168") (name "Net-(MAX20-BIAS)") (class "Default")
      (node (ref "CON27") (pin "A") (pinfunction "1A_A") (pintype "passive"))
      (node (ref "CON27") (pin "B") (pinfunction "1A_B") (pintype "passive"))
      (node (ref "MAX20") (pin "2") (pinfunction "BIAS_2") (pintype "passive"))
      (node (ref "R75") (pin "1") (pinfunction "1_1") (pintype "passive"))
    )
    (net (code "169") (name "Net-(MAX20-T+)") (class "Default")
      (node (ref "C131") (pin "2") (pinfunction "2_2") (pintype "passive"))
      (node (ref "C132") (pin "1") (pinfunction "1_1") (pintype "passive"))
      (node (ref "MAX20") (pin "4") (pinfunction "T+_4") (pintype "passive"))
      (node (ref "R74") (pin "2") (pinfunction "2_2") (pintype "passive"))
    )
    (net (code "170") (name "Net-(MAX20-T-)") (class "Default")
      (node (ref "C131") (pin "1") (pinfunction "1_1") (pintype "passive"))
      (node (ref "C133") (pin "2") (pinfunction "2_2") (pintype "passive"))
      (node (ref "MAX20") (pin "3") (pinfunction "T-_3") (pintype "passive"))
      (node (ref "R75") (pin "2") (pinfunction "2_2") (pintype "passive"))
    )
    (net (code "171") (name "Net-(R76-Pad1)") (class "Default")
      (node (ref "R76") (pin "1") (pinfunction "1_1") (pintype "passive"))
      (node (ref "VREF_ON") (pin "A") (pinfunction "A_A") (pintype "passive"))
    )
    (net (code "172") (name "Net-(TVS1-K1)") (class "Default")
      (node (ref "F1") (pin "2") (pinfunction "2_2") (pintype "passive"))
      (node (ref "R1") (pin "2") (pinfunction "2_2") (pintype "passive"))
      (node (ref "TVS1") (pin "1") (pinfunction "K1_1") (pintype "bidirectional"))
    )
    (net (code "173") (name "Net-(TVS1-K2)") (class "Default")
      (node (ref "F2") (pin "2") (pinfunction "2_2") (pintype "passive"))
      (node (ref "R7") (pin "2") (pinfunction "2_2") (pintype "passive"))
      (node (ref "TVS1") (pin "2") (pinfunction "K2_2") (pintype "bidirectional"))
    )
    (net (code "174") (name "OE_BUF5V") (class "Default")
      (node (ref "IC1") (pin "39") (pinfunction "PL4(OC5B)_39") (pintype "bidirectional"))
      (node (ref "IC3") (pin "1") (pinfunction "OE_1") (pintype "bidirectional"))
    )
    (net (code "175") (name "PA0") (class "Default")
      (node (ref "IC1") (pin "78") (pinfunction "(AD0)PA0_78") (pintype "bidirectional"))
      (node (ref "JP7") (pin "4") (pinfunction "4_4") (pintype "passive"))
    )
    (net (code "176") (name "PA1") (class "Default")
      (node (ref "IC1") (pin "77") (pinfunction "(AD1)PA1_77") (pintype "bidirectional"))
      (node (ref "JP7") (pin "3") (pinfunction "3_3") (pintype "passive"))
    )
    (net (code "177") (name "PA2") (class "Default")
      (node (ref "IC1") (pin "76") (pinfunction "(AD2)PA2_76") (pintype "bidirectional"))
      (node (ref "JP7") (pin "2") (pinfunction "2_2") (pintype "passive"))
    )
    (net (code "178") (name "PA3") (class "Default")
      (node (ref "IC1") (pin "75") (pinfunction "(AD3)PA3_75") (pintype "bidirectional"))
      (node (ref "JP7") (pin "1") (pinfunction "1_1") (pintype "passive"))
    )
    (net (code "179") (name "PA4") (class "Default")
      (node (ref "IC1") (pin "74") (pinfunction "(AD4)PA4_74") (pintype "bidirectional"))
      (node (ref "JP6") (pin "4") (pinfunction "4_4") (pintype "passive"))
    )
    (net (code "180") (name "PA5") (class "Default")
      (node (ref "IC1") (pin "73") (pinfunction "(AD5)PA5_73") (pintype "bidirectional"))
      (node (ref "JP6") (pin "3") (pinfunction "3_3") (pintype "passive"))
    )
    (net (code "181") (name "PA6") (class "Default")
      (node (ref "IC1") (pin "72") (pinfunction "(AD6)PA6_72") (pintype "bidirectional"))
      (node (ref "JP6") (pin "2") (pinfunction "2_2") (pintype "passive"))
    )
    (net (code "182") (name "PA7") (class "Default")
      (node (ref "IC1") (pin "71") (pinfunction "(AD7)PA7_71") (pintype "bidirectional"))
      (node (ref "JP6") (pin "1") (pinfunction "1_1") (pintype "passive"))
    )
    (net (code "183") (name "RESET") (class "Default")
      (node (ref "C34") (pin "2") (pinfunction "2_2") (pintype "passive"))
      (node (ref "IC1") (pin "30") (pinfunction "RESET_30") (pintype "input"))
      (node (ref "JP1") (pin "5") (pinfunction "5_5") (pintype "passive"))
      (node (ref "JTAG1") (pin "6") (pinfunction "~{RESET}_6") (pintype "bidirectional"))
      (node (ref "R13") (pin "2") (pinfunction "2_2") (pintype "passive"))
    )
    (net (code "184") (name "RS") (class "Default")
      (node (ref "IC1") (pin "16") (pinfunction "PH4(OC4B)_16") (pintype "bidirectional"))
      (node (ref "LCD1") (pin "4") (pinfunction "RS_4") (pintype "bidirectional"))
    )
    (net (code "185") (name "RST_RTC") (class "Default")
      (node (ref "IC1") (pin "45") (pinfunction "(RXD1/INT2)PD2_45") (pintype "bidirectional"))
      (node (ref "RTC1") (pin "4") (pinfunction "~{RST}_4") (pintype "bidirectional"))
    )
    (net (code "186") (name "RXD0") (class "Default")
      (node (ref "IC1") (pin "2") (pinfunction "(RXD0/PCIN8)PE0_2") (pintype "bidirectional"))
      (node (ref "SERIAL") (pin "2") (pinfunction "2_2") (pintype "passive"))
    )
    (net (code "187") (name "R{slash}~{W}") (class "Default")
      (node (ref "IC1") (pin "17") (pinfunction "PH5(OC4C)_17") (pintype "bidirectional"))
      (node (ref "LCD1") (pin "5") (pinfunction "R/~{W}_5") (pintype "bidirectional"))
    )
    (net (code "188") (name "SCK_3V3") (class "Default")
      (node (ref "CON7") (pin "5") (pinfunction "CLK_5") (pintype "bidirectional"))
      (node (ref "MAX1") (pin "10") (pinfunction "SCK_10") (pintype "passive"))
      (node (ref "MAX10") (pin "10") (pinfunction "SCK_10") (pintype "passive"))
      (node (ref "MAX11") (pin "10") (pinfunction "SCK_10") (pintype "passive"))
      (node (ref "MAX12") (pin "10") (pinfunction "SCK_10") (pintype "passive"))
      (node (ref "MAX13") (pin "10") (pinfunction "SCK_10") (pintype "passive"))
      (node (ref "MAX14") (pin "10") (pinfunction "SCK_10") (pintype "passive"))
      (node (ref "MAX15") (pin "10") (pinfunction "SCK_10") (pintype "passive"))
      (node (ref "MAX16") (pin "10") (pinfunction "SCK_10") (pintype "passive"))
      (node (ref "MAX17") (pin "10") (pinfunction "SCK_10") (pintype "passive"))
      (node (ref "MAX18") (pin "10") (pinfunction "SCK_10") (pintype "passive"))
      (node (ref "MAX19") (pin "10") (pinfunction "SCK_10") (pintype "passive"))
      (node (ref "MAX2") (pin "10") (pinfunction "SCK_10") (pintype "passive"))
      (node (ref "MAX20") (pin "10") (pinfunction "SCK_10") (pintype "passive"))
      (node (ref "MAX3") (pin "10") (pinfunction "SCK_10") (pintype "passive"))
      (node (ref "MAX4") (pin "10") (pinfunction "SCK_10") (pintype "passive"))
      (node (ref "MAX5") (pin "10") (pinfunction "SCK_10") (pintype "passive"))
      (node (ref "MAX6") (pin "10") (pinfunction "SCK_10") (pintype "passive"))
      (node (ref "MAX7") (pin "10") (pinfunction "SCK_10") (pintype "passive"))
      (node (ref "MAX8") (pin "10") (pinfunction "SCK_10") (pintype "passive"))
      (node (ref "MAX9") (pin "10") (pinfunction "SCK_10") (pintype "passive"))
      (node (ref "U1") (pin "7") (pinfunction "2Y2_7") (pintype "bidirectional"))
    )
    (net (code "189") (name "SCK_5V") (class "Default")
      (node (ref "IC1") (pin "20") (pinfunction "(SCK/PCINT1)PB1_20") (pintype "bidirectional"))
      (node (ref "JP1") (pin "3") (pinfunction "3_3") (pintype "passive"))
      (node (ref "U1") (pin "13") (pinfunction "2A2_13") (pintype "bidirectional"))
    )
    (net (code "190") (name "SCL") (class "Default")
      (node (ref "IC1") (pin "43") (pinfunction "(SCL/INT0)PD0_43") (pintype "bidirectional"))
      (node (ref "INA1") (pin "5") (pinfunction "SCL_5") (pintype "bidirectional"))
      (node (ref "INA2") (pin "5") (pinfunction "SCL_5") (pintype "bidirectional"))
      (node (ref "R2") (pin "1") (pinfunction "1_1") (pintype "passive"))
      (node (ref "RTC1") (pin "8") (pinfunction "SCL_8") (pintype "bidirectional"))
    )
    (net (code "191") (name "SDA") (class "Default")
      (node (ref "IC1") (pin "44") (pinfunction "(SDA/INT1)PD1_44") (pintype "bidirectional"))
      (node (ref "INA1") (pin "4") (pinfunction "SDA_4") (pintype "bidirectional"))
      (node (ref "INA2") (pin "4") (pinfunction "SDA_4") (pintype "bidirectional"))
      (node (ref "R3") (pin "1") (pinfunction "1_1") (pintype "passive"))
      (node (ref "RTC1") (pin "7") (pinfunction "SDA_7") (pintype "bidirectional"))
    )
    (net (code "192") (name "SD_DETECT") (class "Default")
      (node (ref "CON7") (pin "10") (pinfunction "DETECT_SWITCH_10") (pintype "bidirectional"))
      (node (ref "IC1") (pin "40") (pinfunction "PL5(OC5C)_40") (pintype "bidirectional"))
      (node (ref "R30") (pin "1") (pinfunction "1_1") (pintype "passive"))
    )
    (net (code "193") (name "SHDN_VREF") (class "Default")
      (node (ref "IC1") (pin "70") (pinfunction "(ALE)PG2_70") (pintype "bidirectional"))
      (node (ref "VR4") (pin "3") (pinfunction "~{SHDN}_3") (pintype "bidirectional"))
    )
    (net (code "194") (name "SS_3V3") (class "Default")
      (node (ref "IC2") (pin "43") (pinfunction "D_43") (pintype "bidirectional"))
      (node (ref "U1") (pin "5") (pinfunction "2Y1_5") (pintype "bidirectional"))
    )
    (net (code "195") (name "SS_5V") (class "Default")
      (node (ref "IC1") (pin "19") (pinfunction "(SS/PCINT0)PB0_19") (pintype "bidirectional"))
      (node (ref "R39") (pin "2") (pinfunction "2_2") (pintype "passive"))
      (node (ref "U1") (pin "15") (pinfunction "2A1_15") (pintype "bidirectional"))
    )
    (net (code "196") (name "TCK") (class "Default")
      (node (ref "IC1") (pin "93") (pinfunction "(ADC4/TCK)PF4_93") (pintype "bidirectional"))
      (node (ref "JTAG1") (pin "1") (pinfunction "TCK_1") (pintype "bidirectional"))
      (node (ref "R43") (pin "2") (pinfunction "2_2") (pintype "passive"))
    )
    (net (code "197") (name "TDI") (class "Default")
      (node (ref "IC1") (pin "90") (pinfunction "(ADC7/TDI)PF7_90") (pintype "bidirectional"))
      (node (ref "JTAG1") (pin "9") (pinfunction "TDI_9") (pintype "bidirectional"))
      (node (ref "R42") (pin "2") (pinfunction "2_2") (pintype "passive"))
    )
    (net (code "198") (name "TDO") (class "Default")
      (node (ref "IC1") (pin "91") (pinfunction "(ADC6/TDO)PF6_91") (pintype "bidirectional"))
      (node (ref "JTAG1") (pin "3") (pinfunction "TDO_3") (pintype "bidirectional"))
      (node (ref "R40") (pin "2") (pinfunction "2_2") (pintype "passive"))
    )
    (net (code "199") (name "THERM1") (class "Default")
      (node (ref "C16") (pin "1") (pinfunction "1_1") (pintype "passive"))
      (node (ref "IC1") (pin "89") (pinfunction "PK0(ADC8/PCINT16)_89") (pintype "bidirectional"))
      (node (ref "R10") (pin "2") (pinfunction "2_2") (pintype "passive"))
    )
    (net (code "200") (name "THERM2") (class "Default")
      (node (ref "C141") (pin "1") (pinfunction "1_1") (pintype "passive"))
      (node (ref "IC1") (pin "88") (pinfunction "PK1(ADC9/PCINT17)_88") (pintype "bidirectional"))
      (node (ref "R83") (pin "2") (pinfunction "2_2") (pintype "passive"))
    )
    (net (code "201") (name "THERM3") (class "Default")
      (node (ref "C142") (pin "1") (pinfunction "1_1") (pintype "passive"))
      (node (ref "IC1") (pin "87") (pinfunction "PK2(ADC10/PCINT18)_87") (pintype "bidirectional"))
      (node (ref "R85") (pin "2") (pinfunction "2_2") (pintype "passive"))
    )
    (net (code "202") (name "THERM4") (class "Default")
      (node (ref "C143") (pin "1") (pinfunction "1_1") (pintype "passive"))
      (node (ref "IC1") (pin "86") (pinfunction "PK3(ADC11/PCINT19)_86") (pintype "bidirectional"))
      (node (ref "R87") (pin "2") (pinfunction "2_2") (pintype "passive"))
    )
    (net (code "203") (name "THERM5") (class "Default")
      (node (ref "C144") (pin "1") (pinfunction "1_1") (pintype "passive"))
      (node (ref "IC1") (pin "85") (pinfunction "PK4(ADC12/PCINT20)_85") (pintype "bidirectional"))
      (node (ref "R89") (pin "2") (pinfunction "2_2") (pintype "passive"))
    )
    (net (code "204") (name "TMS") (class "Default")
      (node (ref "IC1") (pin "92") (pinfunction "(ADC5/TMS)PF5_92") (pintype "bidirectional"))
      (node (ref "JTAG1") (pin "5") (pinfunction "TMS_5") (pintype "bidirectional"))
      (node (ref "R41") (pin "2") (pinfunction "2_2") (pintype "passive"))
    )
    (net (code "205") (name "TXD0") (class "Default")
      (node (ref "IC1") (pin "3") (pinfunction "(TXD0)PE1_3") (pintype "bidirectional"))
      (node (ref "SERIAL") (pin "3") (pinfunction "3_3") (pintype "passive"))
    )
    (net (code "206") (name "VALIM") (class "Default")
      (node (ref "B1") (pin "+") (pinfunction "+_+") (pintype "passive"))
      (node (ref "C13") (pin "1") (pinfunction "1_1") (pintype "passive"))
      (node (ref "C26") (pin "1") (pinfunction "1_1") (pintype "passive"))
      (node (ref "C27") (pin "1") (pinfunction "1_1") (pintype "passive"))
      (node (ref "C39") (pin "1") (pinfunction "1_1") (pintype "passive"))
      (node (ref "D1") (pin "C") (pinfunction "C_C") (pintype "passive"))
      (node (ref "R24") (pin "2") (pinfunction "2_2") (pintype "passive"))
      (node (ref "VR2") (pin "1") (pinfunction "IN_1") (pintype "input"))
      (node (ref "VR4") (pin "2") (pinfunction "VIN_2") (pintype "power_in"))
    )
    (net (code "207") (name "VBAT") (class "Default")
      (node (ref "BAT1") (pin "1+") (pinfunction "1+_1+") (pintype "bidirectional"))
      (node (ref "RTC1") (pin "6") (pinfunction "VBAT_6") (pintype "bidirectional"))
    )
    (net (code "208") (name "VIN1+") (class "Default")
      (node (ref "INA1") (pin "10") (pinfunction "VIN+_10") (pintype "bidirectional"))
      (node (ref "INA1") (pin "8") (pinfunction "VBUS_8") (pintype "bidirectional"))
      (node (ref "JP2") (pin "2") (pinfunction "2_2") (pintype "passive"))
    )
    (net (code "209") (name "VIN1-") (class "Default")
      (node (ref "INA1") (pin "9") (pinfunction "VIN-_9") (pintype "bidirectional"))
      (node (ref "JP3") (pin "2") (pinfunction "2_2") (pintype "passive"))
    )
    (net (code "210") (name "VIN2+") (class "Default")
      (node (ref "CON8") (pin "2") (pinfunction "2_2") (pintype "passive"))
      (node (ref "INA2") (pin "10") (pinfunction "VIN+_10") (pintype "bidirectional"))
      (node (ref "INA2") (pin "8") (pinfunction "VBUS_8") (pintype "bidirectional"))
      (node (ref "R95") (pin "2") (pinfunction "2_2") (pintype "passive"))
    )
    (net (code "211") (name "VIN2-") (class "Default")
      (node (ref "CON8") (pin "1") (pinfunction "1_1") (pintype "passive"))
      (node (ref "INA2") (pin "9") (pinfunction "VIN-_9") (pintype "bidirectional"))
      (node (ref "R95") (pin "1") (pinfunction "1_1") (pintype "passive"))
    )
    (net (code "212") (name "WR_MUX") (class "Default")
      (node (ref "IC1") (pin "24") (pinfunction "(OC1A/PCINT5)PB5_24") (pintype "bidirectional"))
      (node (ref "U3") (pin "1") (pinfunction "I_1") (pintype "input"))
    )
    (net (code "213") (name "WR_MUX_3V3") (class "Default")
      (node (ref "IC2") (pin "21") (pinfunction "~{WR}_21") (pintype "bidirectional"))
      (node (ref "U3") (pin "6") (pinfunction "O_6") (pintype "output"))
    )
    (net (code "214") (name "unconnected-(IC1-(ADC0)PF0-Pad97)") (class "Default")
      (node (ref "IC1") (pin "97") (pinfunction "(ADC0)PF0_97") (pintype "bidirectional"))
    )
    (net (code "215") (name "unconnected-(IC1-(ADC1)PF1-Pad96)") (class "Default")
      (node (ref "IC1") (pin "96") (pinfunction "(ADC1)PF1_96") (pintype "bidirectional"))
    )
    (net (code "216") (name "unconnected-(IC1-(ICP1)PD4-Pad47)") (class "Default")
      (node (ref "IC1") (pin "47") (pinfunction "(ICP1)PD4_47") (pintype "bidirectional"))
    )
    (net (code "217") (name "unconnected-(IC1-(OC0A{slash}OC1C{slash}PCINT7)PB7-Pad26)") (class "Default")
      (node (ref "IC1") (pin "26") (pinfunction "(OC0A/OC1C/PCINT7)PB7_26") (pintype "bidirectional"))
    )
    (net (code "218") (name "unconnected-(IC1-(OC0B)PG5-Pad1)") (class "Default")
      (node (ref "IC1") (pin "1") (pinfunction "(OC0B)PG5_1") (pintype "bidirectional"))
    )
    (net (code "219") (name "unconnected-(IC1-(T0)PD7-Pad50)") (class "Default")
      (node (ref "IC1") (pin "50") (pinfunction "(T0)PD7_50") (pintype "bidirectional"))
    )
    (net (code "220") (name "unconnected-(IC1-(T1)PD6-Pad49)") (class "Default")
      (node (ref "IC1") (pin "49") (pinfunction "(T1)PD6_49") (pintype "bidirectional"))
    )
    (net (code "221") (name "unconnected-(IC1-(TOSC1)PG4-Pad29)") (class "Default")
      (node (ref "IC1") (pin "29") (pinfunction "(TOSC1)PG4_29") (pintype "bidirectional"))
    )
    (net (code "222") (name "unconnected-(IC1-(TOSC2)PG3-Pad28)") (class "Default")
      (node (ref "IC1") (pin "28") (pinfunction "(TOSC2)PG3_28") (pintype "bidirectional"))
    )
    (net (code "223") (name "unconnected-(IC1-(TXD1{slash}INT3)PD3-Pad46)") (class "Default")
      (node (ref "IC1") (pin "46") (pinfunction "(TXD1/INT3)PD3_46") (pintype "bidirectional"))
    )
    (net (code "224") (name "unconnected-(IC1-(XCK0{slash}AIN0)PE2-Pad4)") (class "Default")
      (node (ref "IC1") (pin "4") (pinfunction "(XCK0/AIN0)PE2_4") (pintype "bidirectional"))
    )
    (net (code "225") (name "unconnected-(IC1-(XCK1)PD5-Pad48)") (class "Default")
      (node (ref "IC1") (pin "48") (pinfunction "(XCK1)PD5_48") (pintype "bidirectional"))
    )
    (net (code "226") (name "unconnected-(IC1-PH0(RXD2)-Pad12)") (class "Default")
      (node (ref "IC1") (pin "12") (pinfunction "PH0(RXD2)_12") (pintype "bidirectional"))
    )
    (net (code "227") (name "unconnected-(IC1-PH1(TXD2)-Pad13)") (class "Default")
      (node (ref "IC1") (pin "13") (pinfunction "PH1(TXD2)_13") (pintype "bidirectional"))
    )
    (net (code "228") (name "unconnected-(IC1-PH2(XCK2)-Pad14)") (class "Default")
      (node (ref "IC1") (pin "14") (pinfunction "PH2(XCK2)_14") (pintype "bidirectional"))
    )
    (net (code "229") (name "unconnected-(IC1-PH3(OC4A)-Pad15)") (class "Default")
      (node (ref "IC1") (pin "15") (pinfunction "PH3(OC4A)_15") (pintype "bidirectional"))
    )
    (net (code "230") (name "unconnected-(IC1-PH7(T4)-Pad27)") (class "Default")
      (node (ref "IC1") (pin "27") (pinfunction "PH7(T4)_27") (pintype "bidirectional"))
    )
    (net (code "231") (name "unconnected-(IC1-PJ0(RXD3{slash}PCINT9)-Pad63)") (class "Default")
      (node (ref "IC1") (pin "63") (pinfunction "PJ0(RXD3/PCINT9)_63") (pintype "bidirectional"))
    )
    (net (code "232") (name "unconnected-(IC1-PJ1(TXD3{slash}PCINT10)-Pad64)") (class "Default")
      (node (ref "IC1") (pin "64") (pinfunction "PJ1(TXD3/PCINT10)_64") (pintype "bidirectional"))
    )
    (net (code "233") (name "unconnected-(IC1-PJ2(XCK3{slash}PCINT11)-Pad65)") (class "Default")
      (node (ref "IC1") (pin "65") (pinfunction "PJ2(XCK3/PCINT11)_65") (pintype "bidirectional"))
    )
    (net (code "234") (name "unconnected-(IC1-PJ3(PCINT12)-Pad66)") (class "Default")
      (node (ref "IC1") (pin "66") (pinfunction "PJ3(PCINT12)_66") (pintype "bidirectional"))
    )
    (net (code "235") (name "unconnected-(IC1-PJ4(PCINT13)-Pad67)") (class "Default")
      (node (ref "IC1") (pin "67") (pinfunction "PJ4(PCINT13)_67") (pintype "bidirectional"))
    )
    (net (code "236") (name "unconnected-(IC1-PJ7-Pad79)") (class "Default")
      (node (ref "IC1") (pin "79") (pinfunction "PJ7_79") (pintype "bidirectional"))
    )
    (net (code "237") (name "unconnected-(IC1-PK7(ADC15{slash}PCINT23)-Pad82)") (class "Default")
      (node (ref "IC1") (pin "82") (pinfunction "PK7(ADC15/PCINT23)_82") (pintype "bidirectional"))
    )
    (net (code "238") (name "unconnected-(IC1-PL0(ICP4)-Pad35)") (class "Default")
      (node (ref "IC1") (pin "35") (pinfunction "PL0(ICP4)_35") (pintype "bidirectional"))
    )
    (net (code "239") (name "unconnected-(IC1-PL1(ICP5)-Pad36)") (class "Default")
      (node (ref "IC1") (pin "36") (pinfunction "PL1(ICP5)_36") (pintype "bidirectional"))
    )
    (net (code "240") (name "unconnected-(IC1-PL2(T5)-Pad37)") (class "Default")
      (node (ref "IC1") (pin "37") (pinfunction "PL2(T5)_37") (pintype "bidirectional"))
    )
    (net (code "241") (name "unconnected-(IC1-PL3(OC5A)-Pad38)") (class "Default")
      (node (ref "IC1") (pin "38") (pinfunction "PL3(OC5A)_38") (pintype "bidirectional"))
    )
    (net (code "242") (name "unconnected-(IC2-NIC-Pad41)") (class "Default")
      (node (ref "IC2") (pin "41") (pinfunction "NIC_41") (pintype "bidirectional"))
    )
    (net (code "243") (name "unconnected-(IC2-NIC-Pad42)") (class "Default")
      (node (ref "IC2") (pin "42") (pinfunction "NIC_42") (pintype "bidirectional"))
    )
    (net (code "244") (name "unconnected-(IC2-NIC-Pad44)") (class "Default")
      (node (ref "IC2") (pin "44") (pinfunction "NIC_44") (pintype "bidirectional"))
    )
    (net (code "245") (name "unconnected-(IC2-S21-Pad29)") (class "Default")
      (node (ref "IC2") (pin "29") (pinfunction "S21_29") (pintype "bidirectional"))
    )
    (net (code "246") (name "unconnected-(IC2-S22-Pad30)") (class "Default")
      (node (ref "IC2") (pin "30") (pinfunction "S22_30") (pintype "bidirectional"))
    )
    (net (code "247") (name "unconnected-(IC2-S23-Pad31)") (class "Default")
      (node (ref "IC2") (pin "31") (pinfunction "S23_31") (pintype "bidirectional"))
    )
    (net (code "248") (name "unconnected-(IC2-S24-Pad32)") (class "Default")
      (node (ref "IC2") (pin "32") (pinfunction "S24_32") (pintype "bidirectional"))
    )
    (net (code "249") (name "unconnected-(IC2-S25-Pad33)") (class "Default")
      (node (ref "IC2") (pin "33") (pinfunction "S25_33") (pintype "bidirectional"))
    )
    (net (code "250") (name "unconnected-(IC2-S26-Pad34)") (class "Default")
      (node (ref "IC2") (pin "34") (pinfunction "S26_34") (pintype "bidirectional"))
    )
    (net (code "251") (name "unconnected-(IC2-S27-Pad35)") (class "Default")
      (node (ref "IC2") (pin "35") (pinfunction "S27_35") (pintype "bidirectional"))
    )
    (net (code "252") (name "unconnected-(IC2-S28-Pad36)") (class "Default")
      (node (ref "IC2") (pin "36") (pinfunction "S28_36") (pintype "bidirectional"))
    )
    (net (code "253") (name "unconnected-(IC2-S29-Pad37)") (class "Default")
      (node (ref "IC2") (pin "37") (pinfunction "S29_37") (pintype "bidirectional"))
    )
    (net (code "254") (name "unconnected-(IC2-S30-Pad38)") (class "Default")
      (node (ref "IC2") (pin "38") (pinfunction "S30_38") (pintype "bidirectional"))
    )
    (net (code "255") (name "unconnected-(IC2-S31-Pad39)") (class "Default")
      (node (ref "IC2") (pin "39") (pinfunction "S31_39") (pintype "bidirectional"))
    )
    (net (code "256") (name "unconnected-(IC2-S32-Pad40)") (class "Default")
      (node (ref "IC2") (pin "40") (pinfunction "S32_40") (pintype "bidirectional"))
    )
    (net (code "257") (name "unconnected-(INA1-ALERT-Pad3)") (class "Default")
      (node (ref "INA1") (pin "3") (pinfunction "ALERT_3") (pintype "bidirectional"))
    )
    (net (code "258") (name "unconnected-(INA2-ALERT-Pad3)") (class "Default")
      (node (ref "INA2") (pin "3") (pinfunction "ALERT_3") (pintype "bidirectional"))
    )
    (net (code "259") (name "unconnected-(JTAG1-NC-Pad7)") (class "Default")
      (node (ref "JTAG1") (pin "7") (pinfunction "NC_7") (pintype "no_connect"))
    )
    (net (code "260") (name "unconnected-(JTAG1-NC{slash}TRST-Pad8)") (class "Default")
      (node (ref "JTAG1") (pin "8") (pinfunction "NC/TRST_8") (pintype "bidirectional"))
    )
    (net (code "261") (name "unconnected-(LCD1-DB0-Pad7)") (class "Default")
      (node (ref "LCD1") (pin "7") (pinfunction "DB0_7") (pintype "bidirectional"))
    )
    (net (code "262") (name "unconnected-(LCD1-DB1-Pad8)") (class "Default")
      (node (ref "LCD1") (pin "8") (pinfunction "DB1_8") (pintype "bidirectional"))
    )
    (net (code "263") (name "unconnected-(LCD1-DB2-Pad9)") (class "Default")
      (node (ref "LCD1") (pin "9") (pinfunction "DB2_9") (pintype "bidirectional"))
    )
    (net (code "264") (name "unconnected-(LCD1-DB3-Pad10)") (class "Default")
      (node (ref "LCD1") (pin "10") (pinfunction "DB3_10") (pintype "bidirectional"))
    )
    (net (code "265") (name "unconnected-(MAX1-DNC-Pad6)") (class "Default")
      (node (ref "MAX1") (pin "6") (pinfunction "DNC_6") (pintype "no_connect"))
    )
    (net (code "266") (name "unconnected-(MAX1-~{DRDY}-Pad7)") (class "Default")
      (node (ref "MAX1") (pin "7") (pinfunction "~{DRDY}_7") (pintype "passive"))
    )
    (net (code "267") (name "unconnected-(MAX1-~{FAULT}-Pad13)") (class "Default")
      (node (ref "MAX1") (pin "13") (pinfunction "~{FAULT}_13") (pintype "passive"))
    )
    (net (code "268") (name "unconnected-(MAX2-DNC-Pad6)") (class "Default")
      (node (ref "MAX2") (pin "6") (pinfunction "DNC_6") (pintype "no_connect"))
    )
    (net (code "269") (name "unconnected-(MAX2-~{DRDY}-Pad7)") (class "Default")
      (node (ref "MAX2") (pin "7") (pinfunction "~{DRDY}_7") (pintype "passive"))
    )
    (net (code "270") (name "unconnected-(MAX2-~{FAULT}-Pad13)") (class "Default")
      (node (ref "MAX2") (pin "13") (pinfunction "~{FAULT}_13") (pintype "passive"))
    )
    (net (code "271") (name "unconnected-(MAX3-DNC-Pad6)") (class "Default")
      (node (ref "MAX3") (pin "6") (pinfunction "DNC_6") (pintype "no_connect"))
    )
    (net (code "272") (name "unconnected-(MAX3-~{DRDY}-Pad7)") (class "Default")
      (node (ref "MAX3") (pin "7") (pinfunction "~{DRDY}_7") (pintype "passive"))
    )
    (net (code "273") (name "unconnected-(MAX3-~{FAULT}-Pad13)") (class "Default")
      (node (ref "MAX3") (pin "13") (pinfunction "~{FAULT}_13") (pintype "passive"))
    )
    (net (code "274") (name "unconnected-(MAX4-DNC-Pad6)") (class "Default")
      (node (ref "MAX4") (pin "6") (pinfunction "DNC_6") (pintype "no_connect"))
    )
    (net (code "275") (name "unconnected-(MAX4-~{DRDY}-Pad7)") (class "Default")
      (node (ref "MAX4") (pin "7") (pinfunction "~{DRDY}_7") (pintype "passive"))
    )
    (net (code "276") (name "unconnected-(MAX4-~{FAULT}-Pad13)") (class "Default")
      (node (ref "MAX4") (pin "13") (pinfunction "~{FAULT}_13") (pintype "passive"))
    )
    (net (code "277") (name "unconnected-(MAX5-DNC-Pad6)") (class "Default")
      (node (ref "MAX5") (pin "6") (pinfunction "DNC_6") (pintype "no_connect"))
    )
    (net (code "278") (name "unconnected-(MAX5-~{DRDY}-Pad7)") (class "Default")
      (node (ref "MAX5") (pin "7") (pinfunction "~{DRDY}_7") (pintype "passive"))
    )
    (net (code "279") (name "unconnected-(MAX5-~{FAULT}-Pad13)") (class "Default")
      (node (ref "MAX5") (pin "13") (pinfunction "~{FAULT}_13") (pintype "passive"))
    )
    (net (code "280") (name "unconnected-(MAX6-DNC-Pad6)") (class "Default")
      (node (ref "MAX6") (pin "6") (pinfunction "DNC_6") (pintype "no_connect"))
    )
    (net (code "281") (name "unconnected-(MAX6-~{DRDY}-Pad7)") (class "Default")
      (node (ref "MAX6") (pin "7") (pinfunction "~{DRDY}_7") (pintype "passive"))
    )
    (net (code "282") (name "unconnected-(MAX6-~{FAULT}-Pad13)") (class "Default")
      (node (ref "MAX6") (pin "13") (pinfunction "~{FAULT}_13") (pintype "passive"))
    )
    (net (code "283") (name "unconnected-(MAX7-DNC-Pad6)") (class "Default")
      (node (ref "MAX7") (pin "6") (pinfunction "DNC_6") (pintype "no_connect"))
    )
    (net (code "284") (name "unconnected-(MAX7-~{DRDY}-Pad7)") (class "Default")
      (node (ref "MAX7") (pin "7") (pinfunction "~{DRDY}_7") (pintype "passive"))
    )
    (net (code "285") (name "unconnected-(MAX7-~{FAULT}-Pad13)") (class "Default")
      (node (ref "MAX7") (pin "13") (pinfunction "~{FAULT}_13") (pintype "passive"))
    )
    (net (code "286") (name "unconnected-(MAX8-DNC-Pad6)") (class "Default")
      (node (ref "MAX8") (pin "6") (pinfunction "DNC_6") (pintype "no_connect"))
    )
    (net (code "287") (name "unconnected-(MAX8-~{DRDY}-Pad7)") (class "Default")
      (node (ref "MAX8") (pin "7") (pinfunction "~{DRDY}_7") (pintype "passive"))
    )
    (net (code "288") (name "unconnected-(MAX8-~{FAULT}-Pad13)") (class "Default")
      (node (ref "MAX8") (pin "13") (pinfunction "~{FAULT}_13") (pintype "passive"))
    )
    (net (code "289") (name "unconnected-(MAX9-DNC-Pad6)") (class "Default")
      (node (ref "MAX9") (pin "6") (pinfunction "DNC_6") (pintype "no_connect"))
    )
    (net (code "290") (name "unconnected-(MAX9-~{DRDY}-Pad7)") (class "Default")
      (node (ref "MAX9") (pin "7") (pinfunction "~{DRDY}_7") (pintype "passive"))
    )
    (net (code "291") (name "unconnected-(MAX9-~{FAULT}-Pad13)") (class "Default")
      (node (ref "MAX9") (pin "13") (pinfunction "~{FAULT}_13") (pintype "passive"))
    )
    (net (code "292") (name "unconnected-(MAX10-DNC-Pad6)") (class "Default")
      (node (ref "MAX10") (pin "6") (pinfunction "DNC_6") (pintype "no_connect"))
    )
    (net (code "293") (name "unconnected-(MAX10-~{DRDY}-Pad7)") (class "Default")
      (node (ref "MAX10") (pin "7") (pinfunction "~{DRDY}_7") (pintype "passive"))
    )
    (net (code "294") (name "unconnected-(MAX10-~{FAULT}-Pad13)") (class "Default")
      (node (ref "MAX10") (pin "13") (pinfunction "~{FAULT}_13") (pintype "passive"))
    )
    (net (code "295") (name "unconnected-(MAX11-DNC-Pad6)") (class "Default")
      (node (ref "MAX11") (pin "6") (pinfunction "DNC_6") (pintype "no_connect"))
    )
    (net (code "296") (name "unconnected-(MAX11-~{DRDY}-Pad7)") (class "Default")
      (node (ref "MAX11") (pin "7") (pinfunction "~{DRDY}_7") (pintype "passive"))
    )
    (net (code "297") (name "unconnected-(MAX11-~{FAULT}-Pad13)") (class "Default")
      (node (ref "MAX11") (pin "13") (pinfunction "~{FAULT}_13") (pintype "passive"))
    )
    (net (code "298") (name "unconnected-(MAX12-DNC-Pad6)") (class "Default")
      (node (ref "MAX12") (pin "6") (pinfunction "DNC_6") (pintype "no_connect"))
    )
    (net (code "299") (name "unconnected-(MAX12-~{DRDY}-Pad7)") (class "Default")
      (node (ref "MAX12") (pin "7") (pinfunction "~{DRDY}_7") (pintype "passive"))
    )
    (net (code "300") (name "unconnected-(MAX12-~{FAULT}-Pad13)") (class "Default")
      (node (ref "MAX12") (pin "13") (pinfunction "~{FAULT}_13") (pintype "passive"))
    )
    (net (code "301") (name "unconnected-(MAX13-DNC-Pad6)") (class "Default")
      (node (ref "MAX13") (pin "6") (pinfunction "DNC_6") (pintype "no_connect"))
    )
    (net (code "302") (name "unconnected-(MAX13-~{DRDY}-Pad7)") (class "Default")
      (node (ref "MAX13") (pin "7") (pinfunction "~{DRDY}_7") (pintype "passive"))
    )
    (net (code "303") (name "unconnected-(MAX13-~{FAULT}-Pad13)") (class "Default")
      (node (ref "MAX13") (pin "13") (pinfunction "~{FAULT}_13") (pintype "passive"))
    )
    (net (code "304") (name "unconnected-(MAX14-DNC-Pad6)") (class "Default")
      (node (ref "MAX14") (pin "6") (pinfunction "DNC_6") (pintype "no_connect"))
    )
    (net (code "305") (name "unconnected-(MAX14-~{DRDY}-Pad7)") (class "Default")
      (node (ref "MAX14") (pin "7") (pinfunction "~{DRDY}_7") (pintype "passive"))
    )
    (net (code "306") (name "unconnected-(MAX14-~{FAULT}-Pad13)") (class "Default")
      (node (ref "MAX14") (pin "13") (pinfunction "~{FAULT}_13") (pintype "passive"))
    )
    (net (code "307") (name "unconnected-(MAX15-DNC-Pad6)") (class "Default")
      (node (ref "MAX15") (pin "6") (pinfunction "DNC_6") (pintype "no_connect"))
    )
    (net (code "308") (name "unconnected-(MAX15-~{DRDY}-Pad7)") (class "Default")
      (node (ref "MAX15") (pin "7") (pinfunction "~{DRDY}_7") (pintype "passive"))
    )
    (net (code "309") (name "unconnected-(MAX15-~{FAULT}-Pad13)") (class "Default")
      (node (ref "MAX15") (pin "13") (pinfunction "~{FAULT}_13") (pintype "passive"))
    )
    (net (code "310") (name "unconnected-(MAX16-DNC-Pad6)") (class "Default")
      (node (ref "MAX16") (pin "6") (pinfunction "DNC_6") (pintype "no_connect"))
    )
    (net (code "311") (name "unconnected-(MAX16-~{DRDY}-Pad7)") (class "Default")
      (node (ref "MAX16") (pin "7") (pinfunction "~{DRDY}_7") (pintype "passive"))
    )
    (net (code "312") (name "unconnected-(MAX16-~{FAULT}-Pad13)") (class "Default")
      (node (ref "MAX16") (pin "13") (pinfunction "~{FAULT}_13") (pintype "passive"))
    )
    (net (code "313") (name "unconnected-(MAX17-DNC-Pad6)") (class "Default")
      (node (ref "MAX17") (pin "6") (pinfunction "DNC_6") (pintype "no_connect"))
    )
    (net (code "314") (name "unconnected-(MAX17-~{DRDY}-Pad7)") (class "Default")
      (node (ref "MAX17") (pin "7") (pinfunction "~{DRDY}_7") (pintype "passive"))
    )
    (net (code "315") (name "unconnected-(MAX17-~{FAULT}-Pad13)") (class "Default")
      (node (ref "MAX17") (pin "13") (pinfunction "~{FAULT}_13") (pintype "passive"))
    )
    (net (code "316") (name "unconnected-(MAX18-DNC-Pad6)") (class "Default")
      (node (ref "MAX18") (pin "6") (pinfunction "DNC_6") (pintype "no_connect"))
    )
    (net (code "317") (name "unconnected-(MAX18-~{DRDY}-Pad7)") (class "Default")
      (node (ref "MAX18") (pin "7") (pinfunction "~{DRDY}_7") (pintype "passive"))
    )
    (net (code "318") (name "unconnected-(MAX18-~{FAULT}-Pad13)") (class "Default")
      (node (ref "MAX18") (pin "13") (pinfunction "~{FAULT}_13") (pintype "passive"))
    )
    (net (code "319") (name "unconnected-(MAX19-DNC-Pad6)") (class "Default")
      (node (ref "MAX19") (pin "6") (pinfunction "DNC_6") (pintype "no_connect"))
    )
    (net (code "320") (name "unconnected-(MAX19-~{DRDY}-Pad7)") (class "Default")
      (node (ref "MAX19") (pin "7") (pinfunction "~{DRDY}_7") (pintype "passive"))
    )
    (net (code "321") (name "unconnected-(MAX19-~{FAULT}-Pad13)") (class "Default")
      (node (ref "MAX19") (pin "13") (pinfunction "~{FAULT}_13") (pintype "passive"))
    )
    (net (code "322") (name "unconnected-(MAX20-DNC-Pad6)") (class "Default")
      (node (ref "MAX20") (pin "6") (pinfunction "DNC_6") (pintype "no_connect"))
    )
    (net (code "323") (name "unconnected-(MAX20-~{DRDY}-Pad7)") (class "Default")
      (node (ref "MAX20") (pin "7") (pinfunction "~{DRDY}_7") (pintype "passive"))
    )
    (net (code "324") (name "unconnected-(MAX20-~{FAULT}-Pad13)") (class "Default")
      (node (ref "MAX20") (pin "13") (pinfunction "~{FAULT}_13") (pintype "passive"))
    )
    (net (code "325") (name "unconnected-(RTC1-32KHZ-Pad1)") (class "Default")
      (node (ref "RTC1") (pin "1") (pinfunction "32KHZ_1") (pintype "bidirectional"))
    )
    (net (code "326") (name "unconnected-(RTC1-~{INT}{slash}SQW-Pad3)") (class "Default")
      (node (ref "RTC1") (pin "3") (pinfunction "~{INT}/SQW_3") (pintype "bidirectional"))
    )
    (net (code "327") (name "unconnected-(U1-2Y0-Pad3)") (class "Default")
      (node (ref "U1") (pin "3") (pinfunction "2Y0_3") (pintype "bidirectional"))
    )
    (net (code "328") (name "unconnected-(U2-O1-Pad4)") (class "Default")
      (node (ref "U2") (pin "4") (pinfunction "O1_4") (pintype "output"))
    )
    (net (code "329") (name "unconnected-(VR4-DNC-Pad1)") (class "Default")
      (node (ref "VR4") (pin "1") (pinfunction "DNC_1") (pintype "no_connect"))
    )
    (net (code "330") (name "unconnected-(VR4-DNC-Pad5)") (class "Default")
      (node (ref "VR4") (pin "5") (pinfunction "DNC_5") (pintype "no_connect"))
    )
    (net (code "331") (name "unconnected-(VR4-DNC-Pad7)") (class "Default")
      (node (ref "VR4") (pin "7") (pinfunction "DNC_7") (pintype "no_connect"))
    )
    (net (code "332") (name "unconnected-(VR4-DNC-Pad8)") (class "Default")
      (node (ref "VR4") (pin "8") (pinfunction "DNC_8") (pintype "no_connect"))
    )
    (net (code "333") (name "~{E}") (class "Default")
      (node (ref "IC1") (pin "18") (pinfunction "PH6(OC2B)_18") (pintype "bidirectional"))
      (node (ref "LCD1") (pin "6") (pinfunction "~{E}_6") (pintype "bidirectional"))
    )
  )
)
